# HW_RPI_DAQ.net
KiCad netlist of a schematic drawn in EAGLE
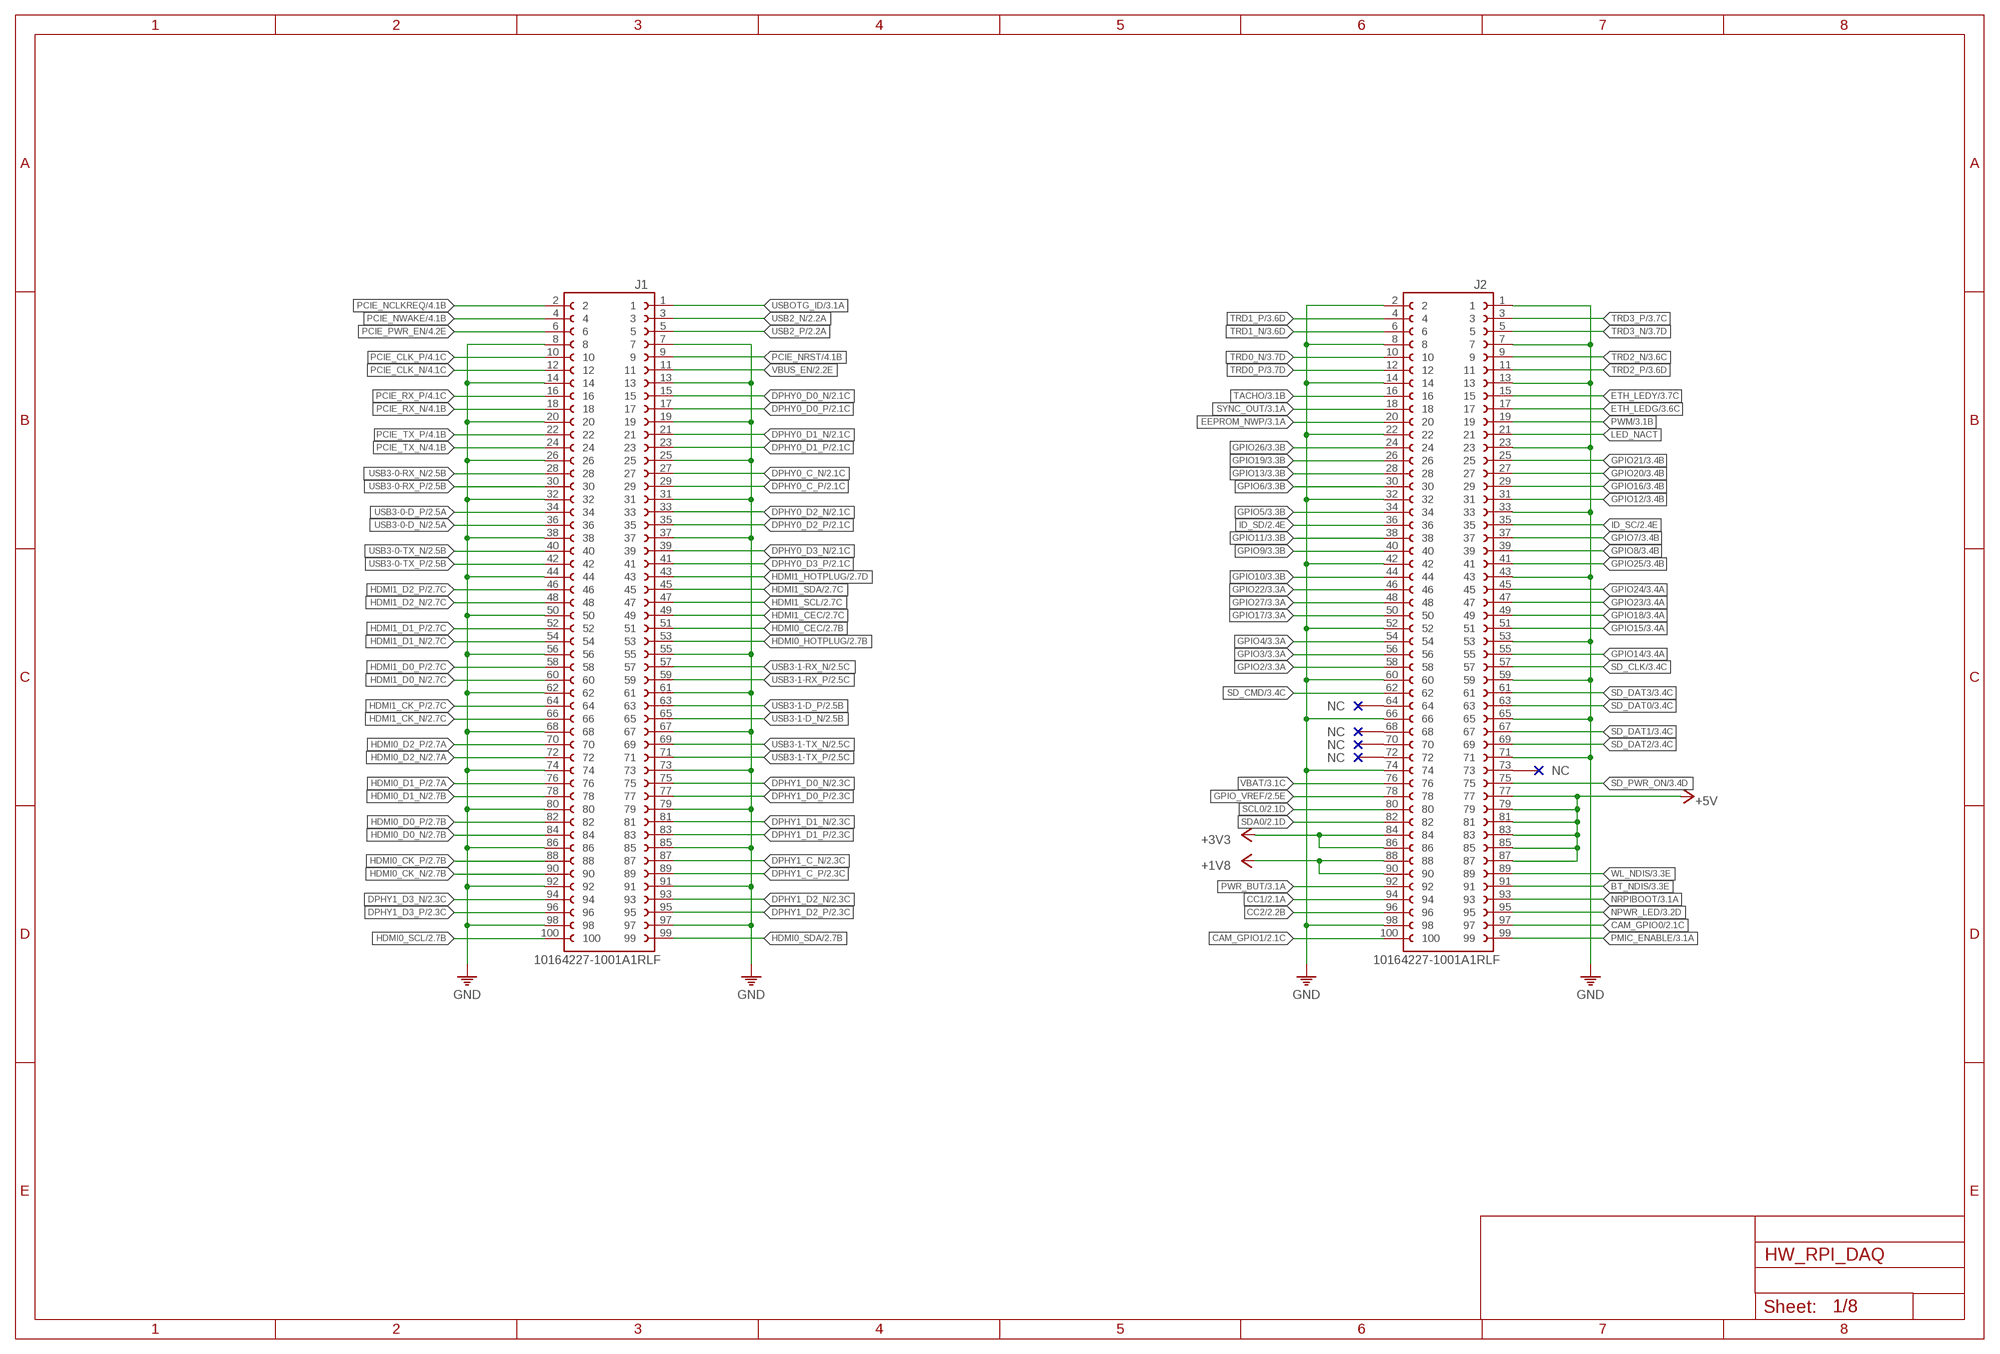
[diagram p0: schematic, sheet 1]
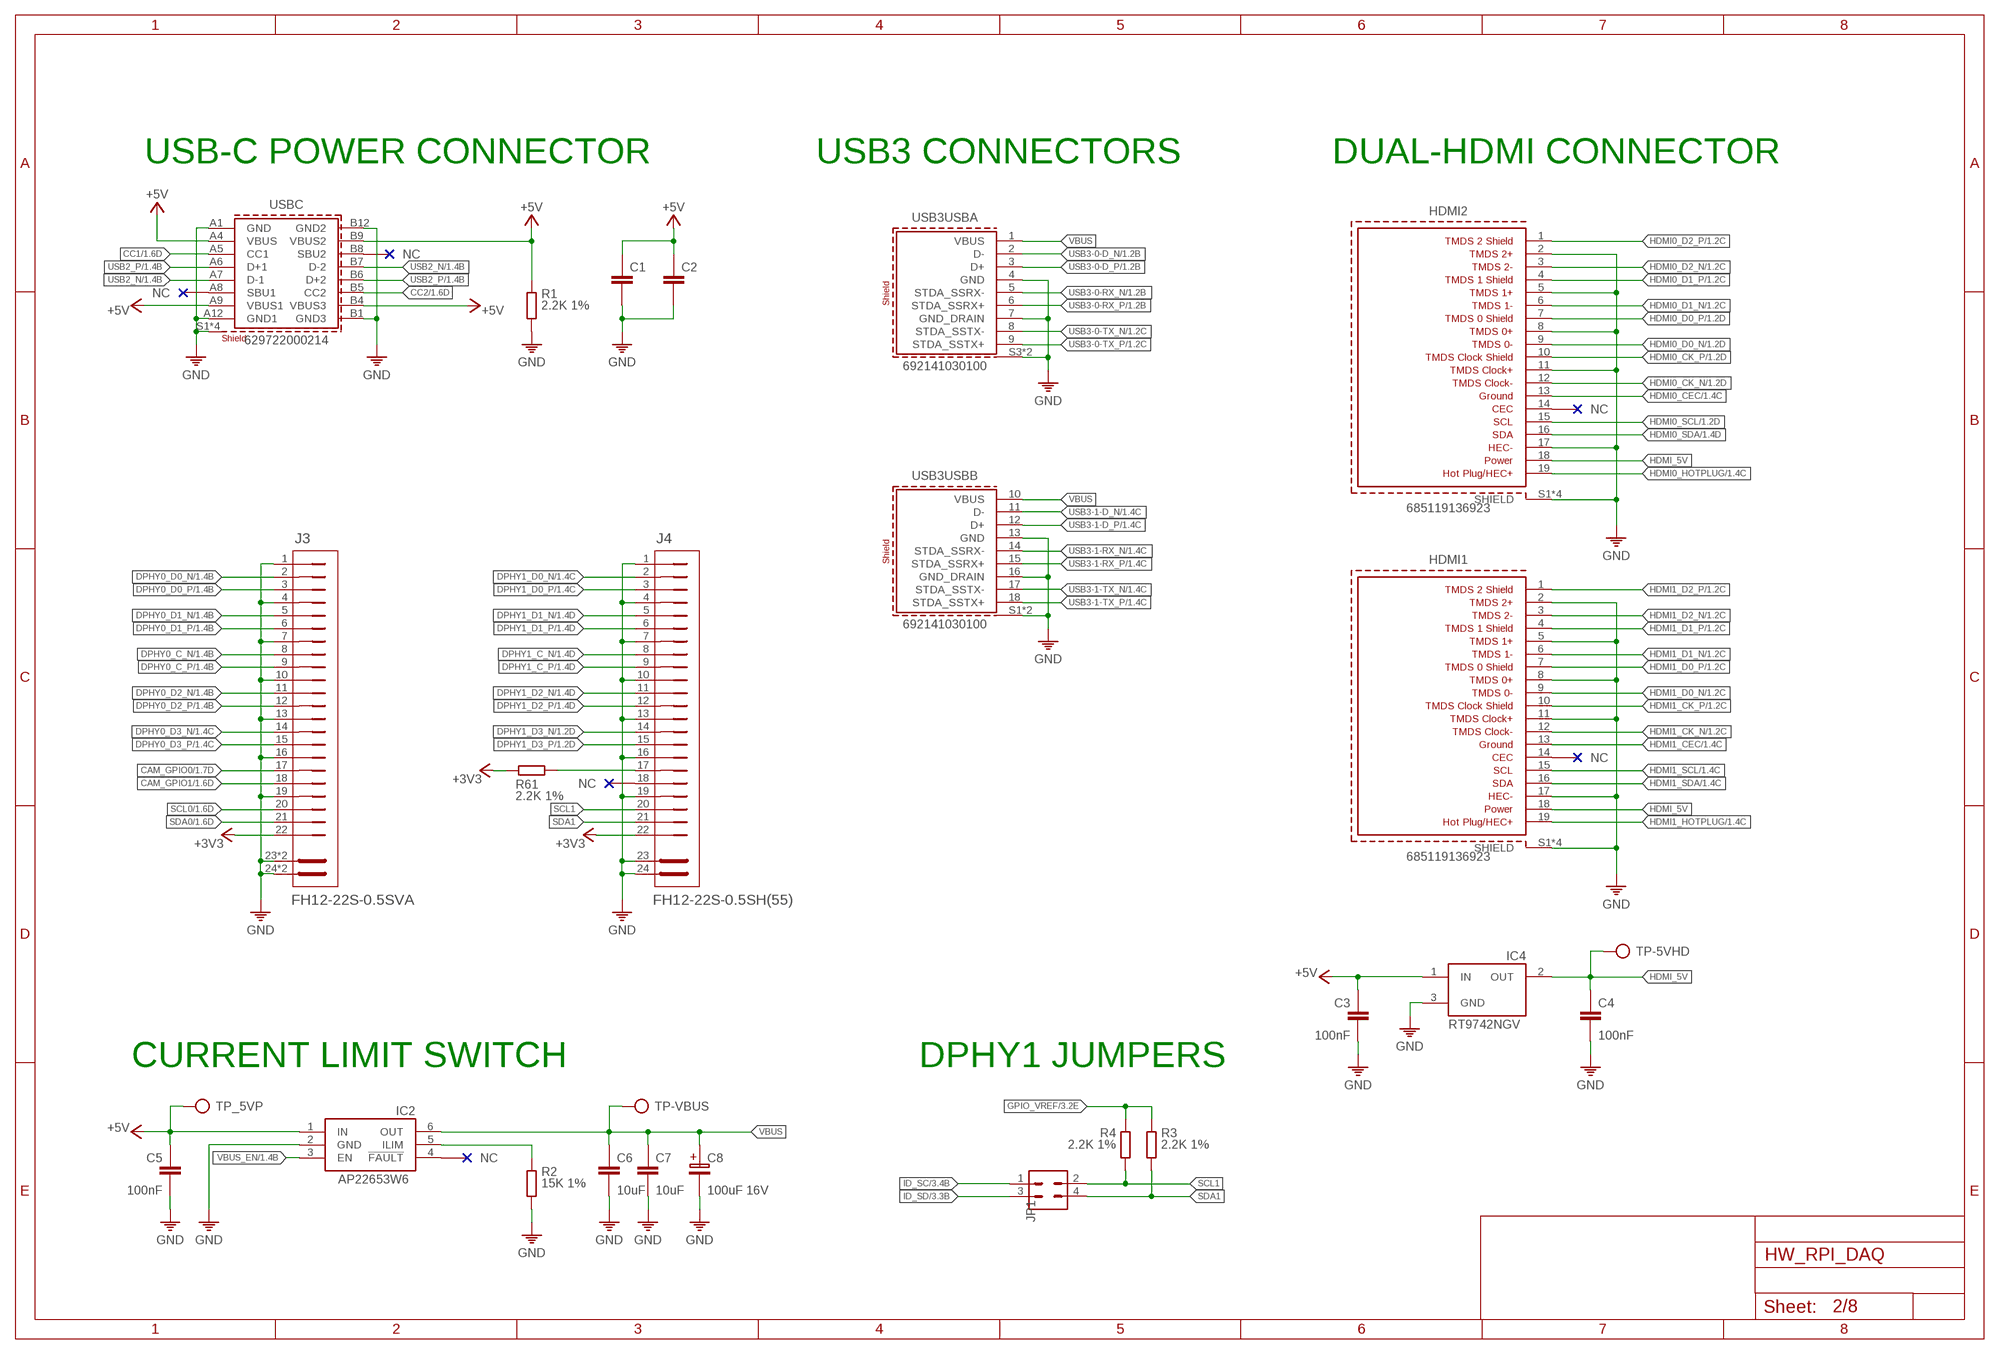
[diagram p1: schematic, sheet 2]
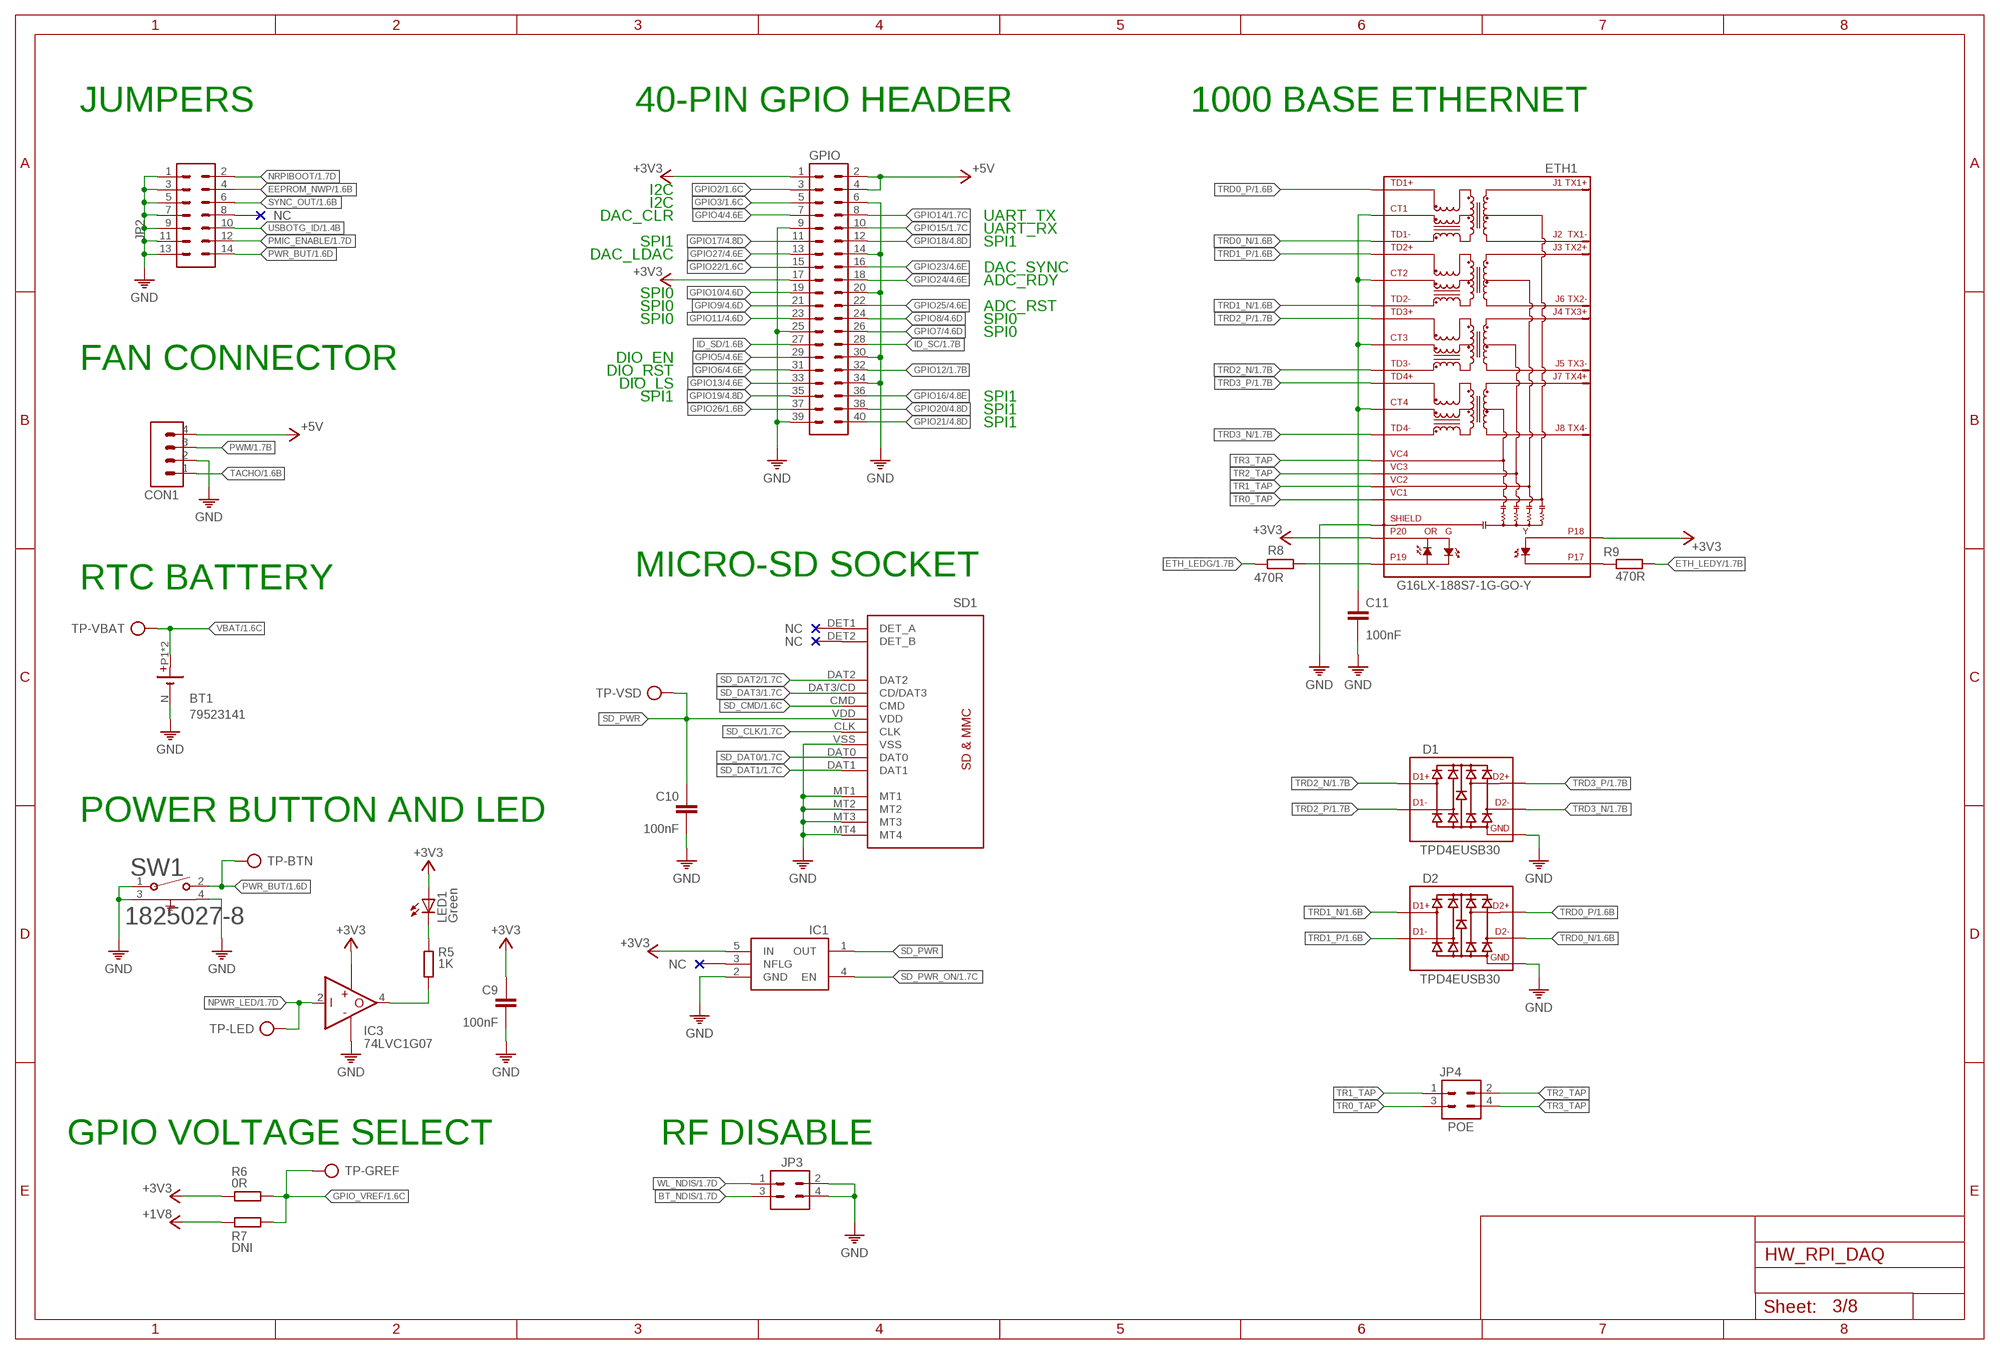
[diagram p2: schematic, sheet 3]
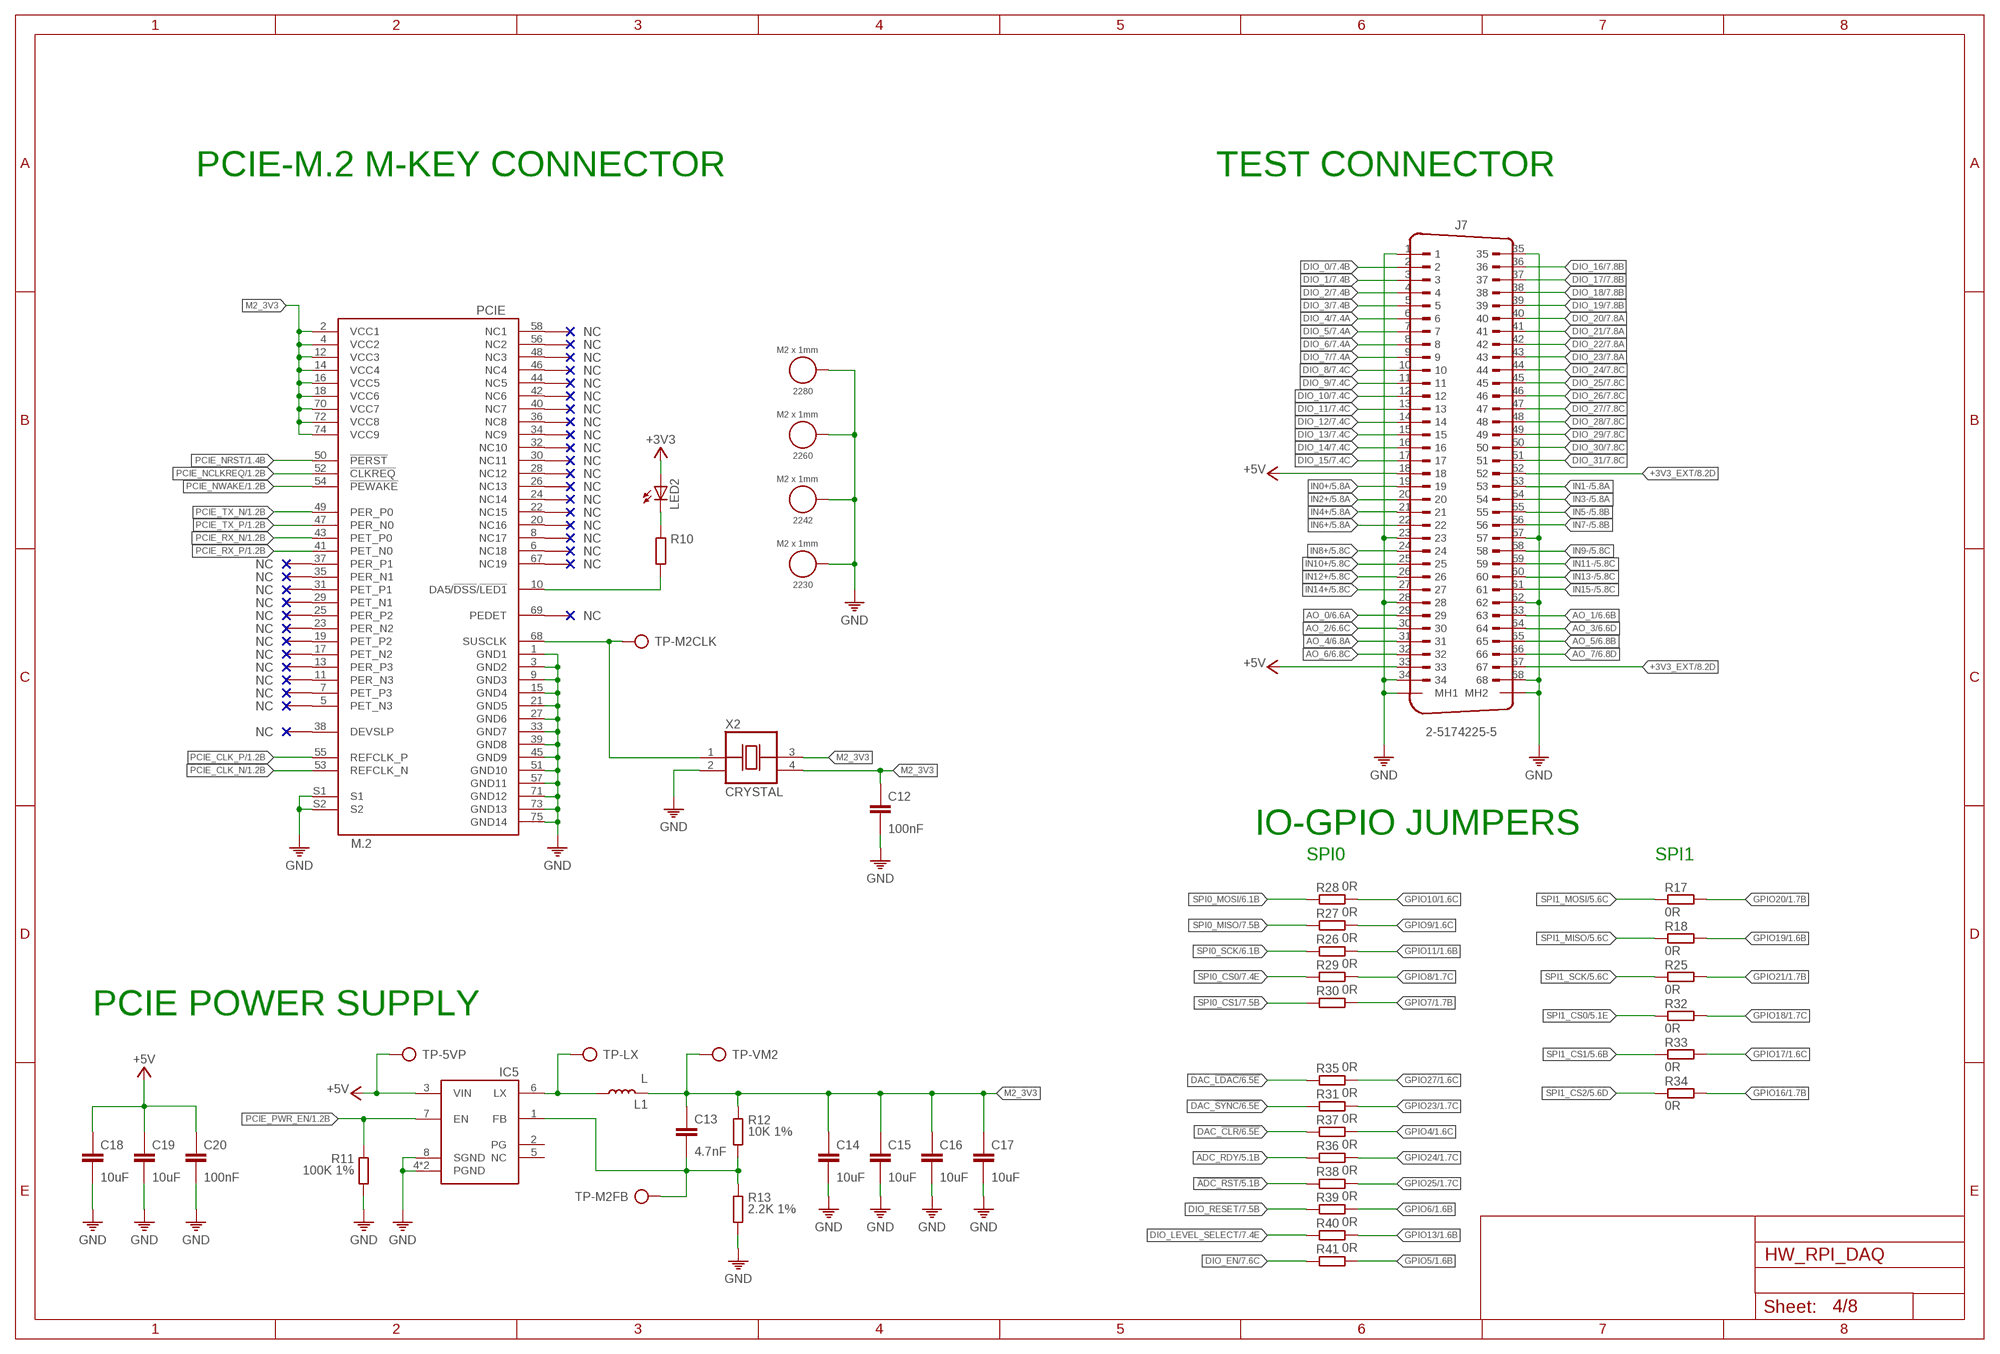
[diagram p3: schematic, sheet 4]
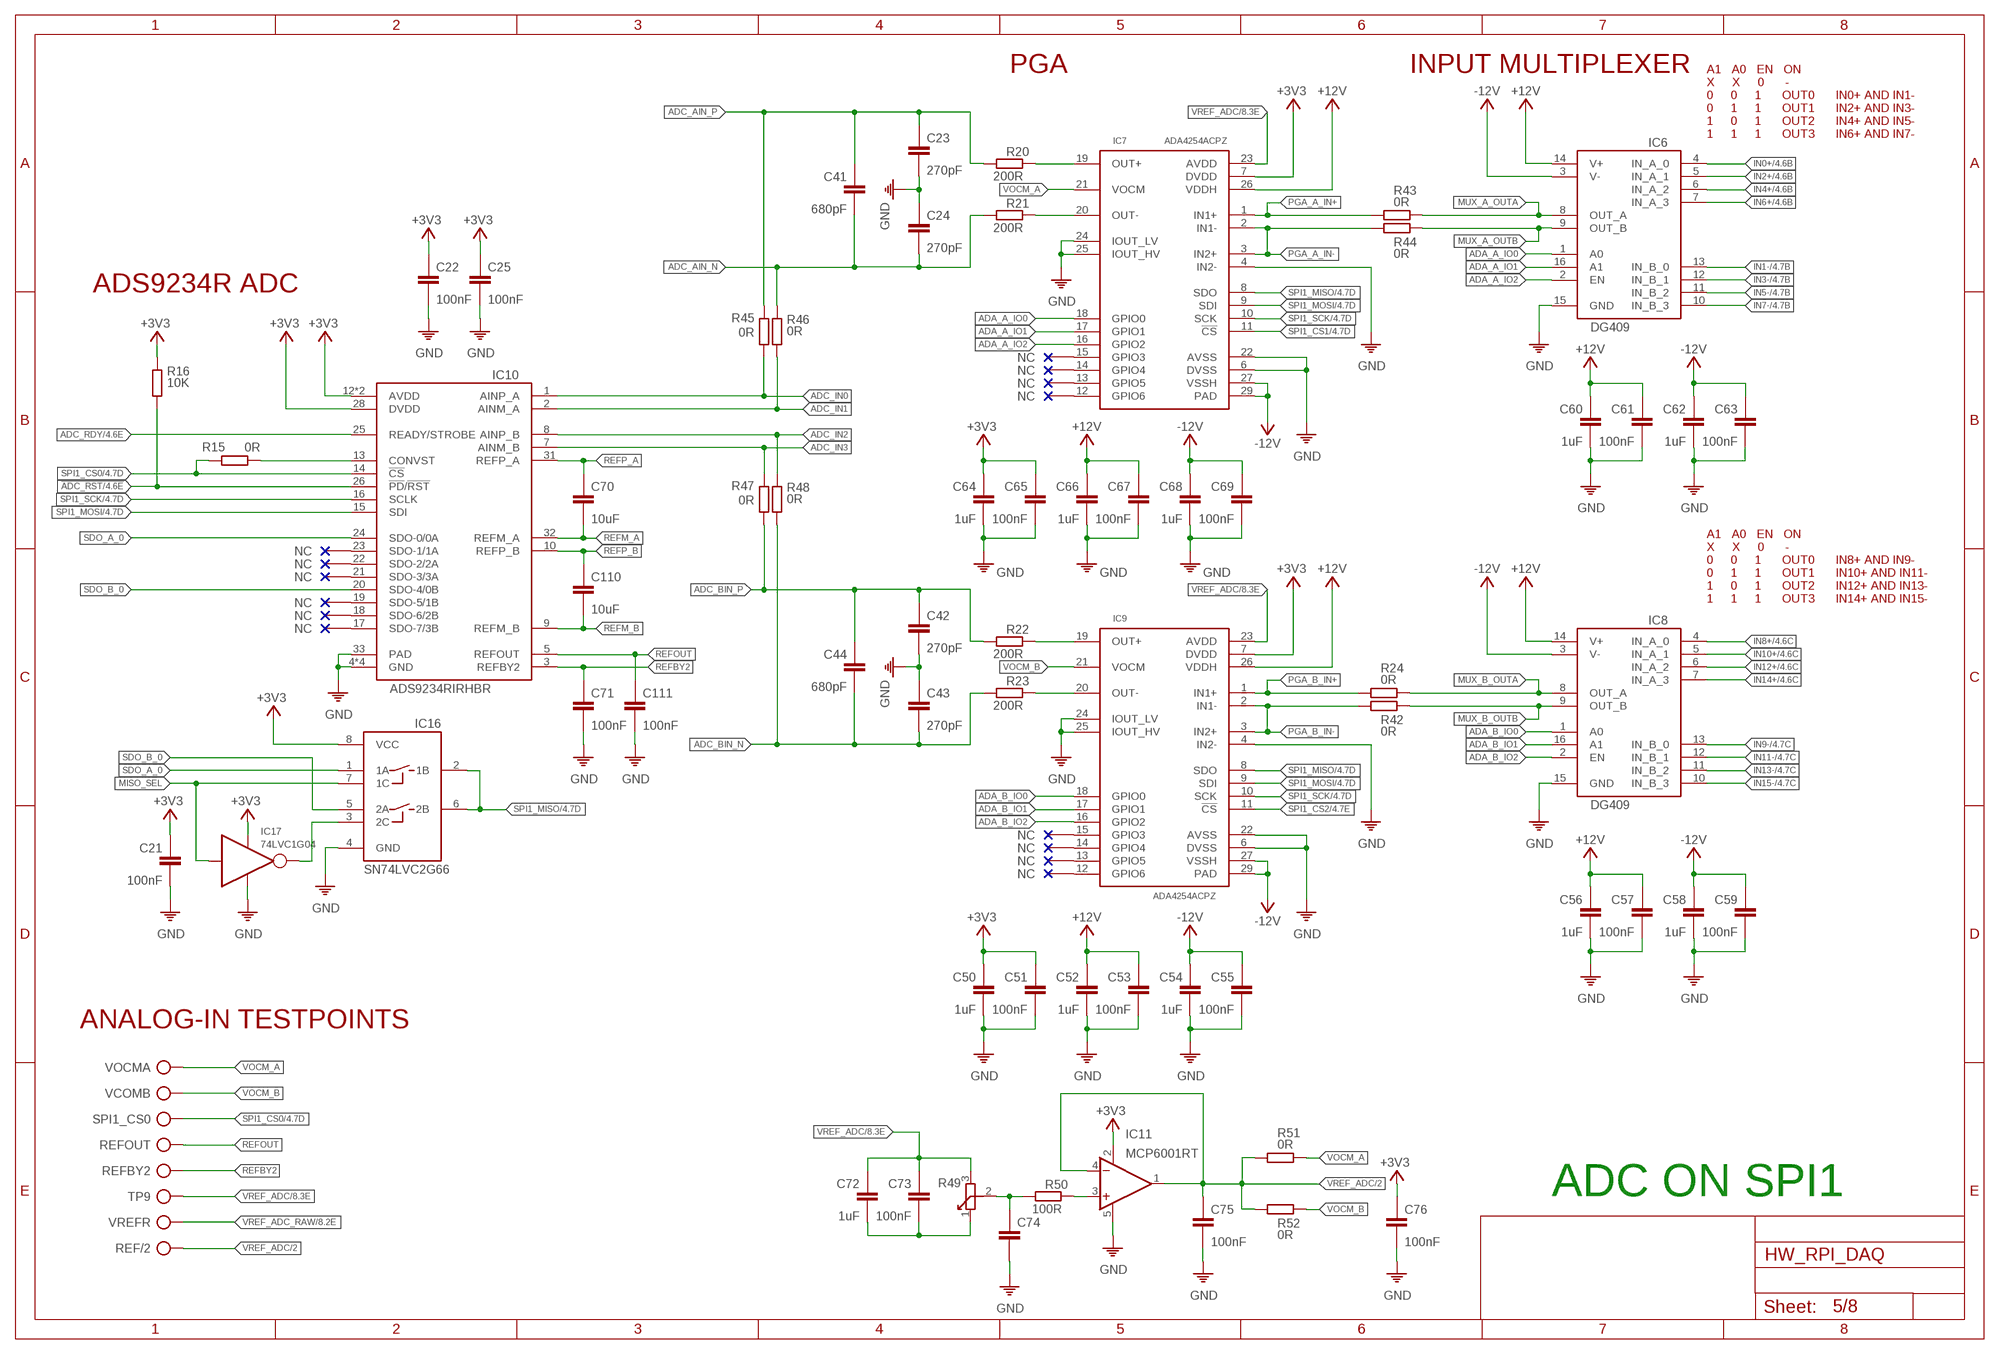
[diagram p4: schematic, sheet 5]
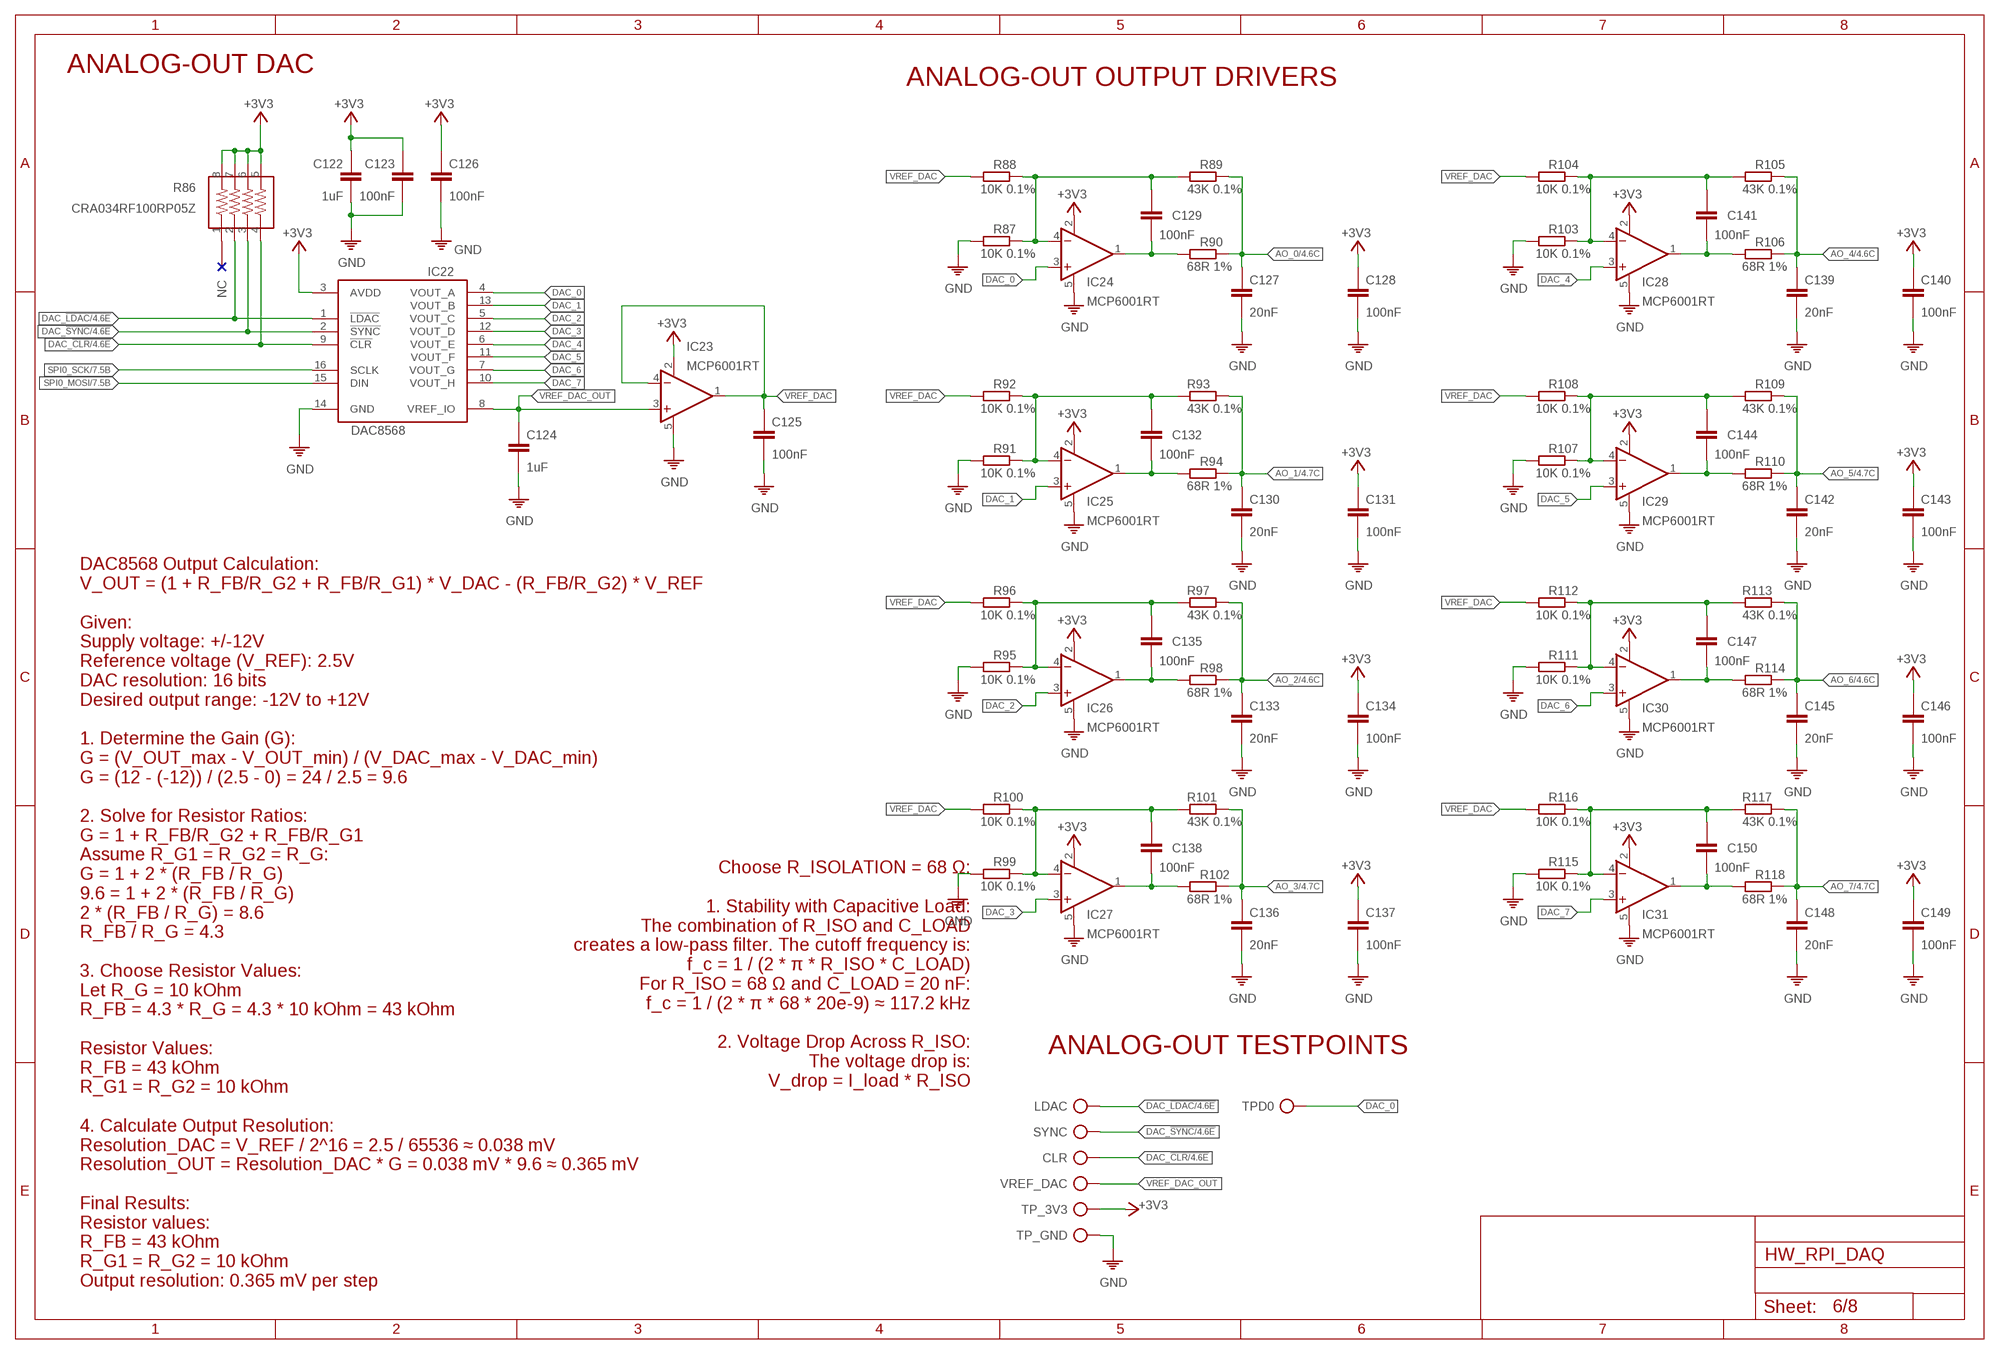
[diagram p5: schematic, sheet 6]
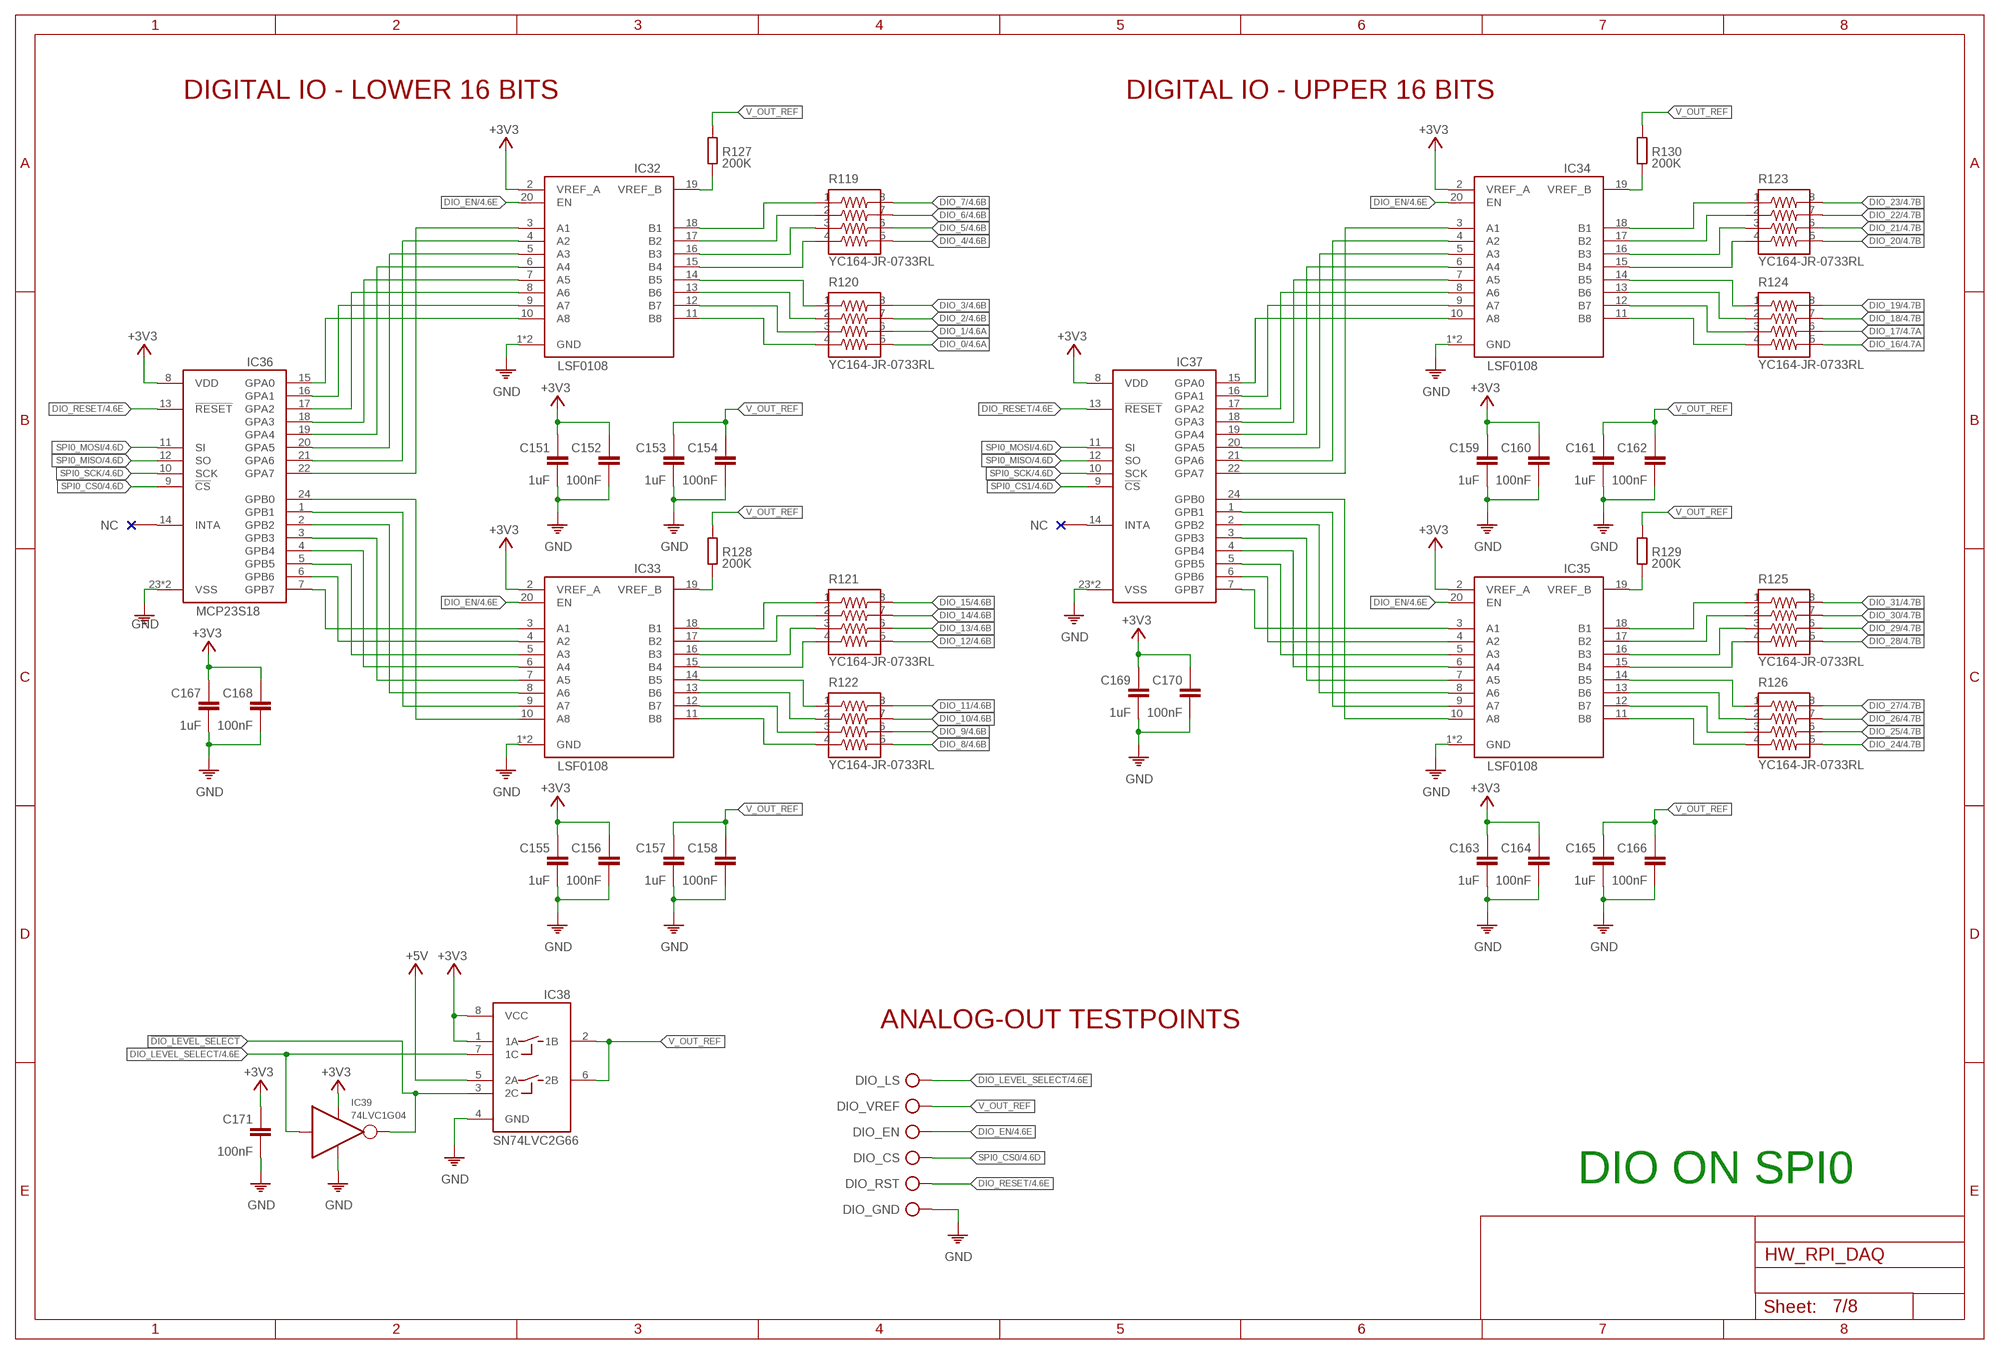
[diagram p6: schematic, sheet 7]
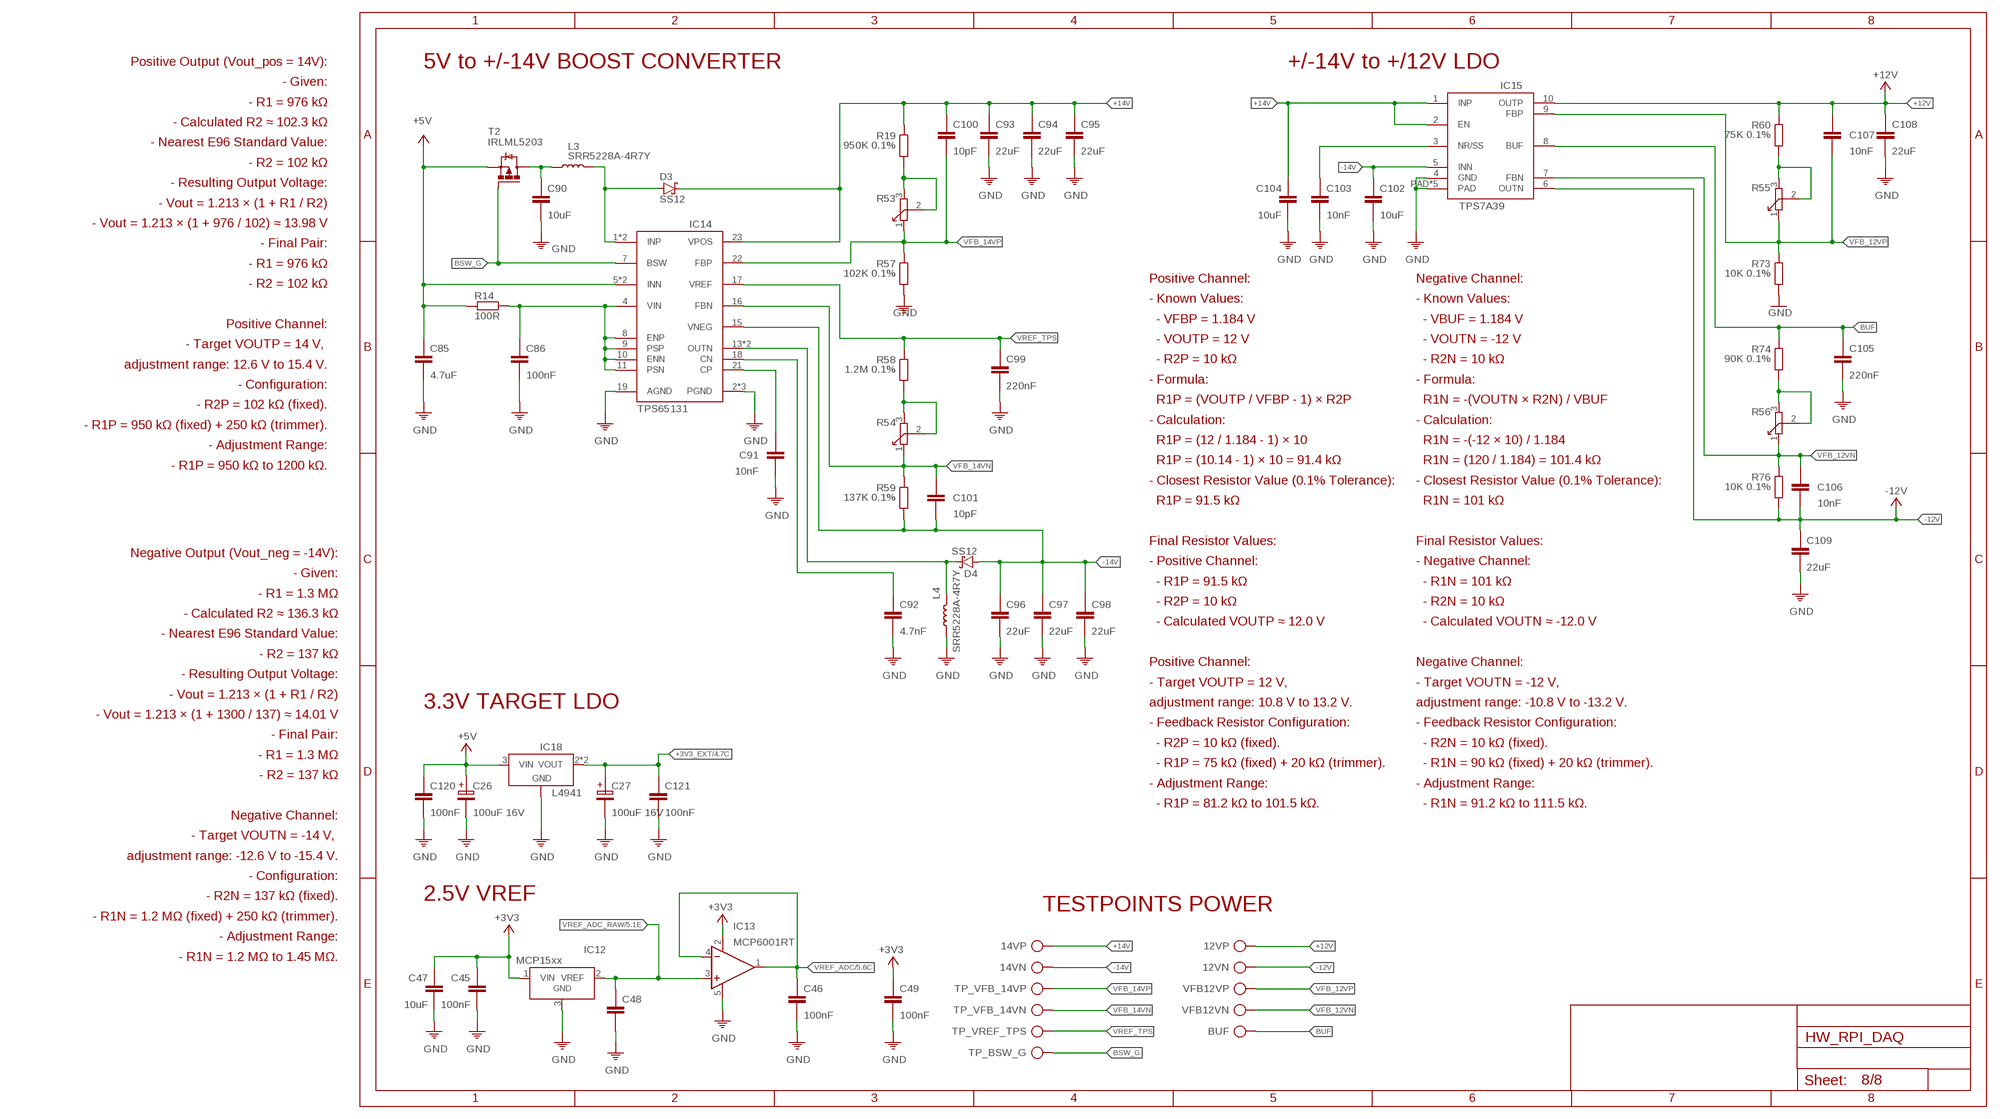
[diagram p7: schematic, sheet 8]

(export (version "E")
  (design (tool "Eeschema 10.0.6"))
  (components
    (comp (ref "C21")
      (value "100nF")
      (footprint "eagle-import:0603")
      (libsource (lib "eagle-import") (part "C0603"))
    )
    (comp (ref "C22")
      (value "100nF")
      (footprint "eagle-import:0402")
      (libsource (lib "eagle-import") (part "C0402"))
    )
    (comp (ref "C23")
      (value "270pF")
      (footprint "eagle-import:0402")
      (libsource (lib "eagle-import") (part "C0402"))
    )
    (comp (ref "C24")
      (value "270pF")
      (footprint "eagle-import:0402")
      (libsource (lib "eagle-import") (part "C0402"))
    )
    (comp (ref "C25")
      (value "100nF")
      (footprint "eagle-import:0402")
      (libsource (lib "eagle-import") (part "C0402"))
    )
    (comp (ref "C41")
      (value "680pF")
      (footprint "eagle-import:0402")
      (libsource (lib "eagle-import") (part "C0402"))
    )
    (comp (ref "C42")
      (value "270pF")
      (footprint "eagle-import:0402")
      (libsource (lib "eagle-import") (part "C0402"))
    )
    (comp (ref "C43")
      (value "270pF")
      (footprint "eagle-import:0402")
      (libsource (lib "eagle-import") (part "C0402"))
    )
    (comp (ref "C44")
      (value "680pF")
      (footprint "eagle-import:0402")
      (libsource (lib "eagle-import") (part "C0402"))
    )
    (comp (ref "C50")
      (value "1uF")
      (footprint "eagle-import:0603")
      (libsource (lib "eagle-import") (part "C0603"))
    )
    (comp (ref "C51")
      (value "100nF")
      (footprint "eagle-import:0402")
      (libsource (lib "eagle-import") (part "C0402"))
    )
    (comp (ref "C52")
      (value "1uF")
      (footprint "eagle-import:0603")
      (libsource (lib "eagle-import") (part "C0603"))
    )
    (comp (ref "C53")
      (value "100nF")
      (footprint "eagle-import:0402")
      (libsource (lib "eagle-import") (part "C0402"))
    )
    (comp (ref "C54")
      (value "1uF")
      (footprint "eagle-import:0603")
      (libsource (lib "eagle-import") (part "C0603"))
    )
    (comp (ref "C55")
      (value "100nF")
      (footprint "eagle-import:0402")
      (libsource (lib "eagle-import") (part "C0402"))
    )
    (comp (ref "C56")
      (value "1uF")
      (footprint "eagle-import:0603")
      (libsource (lib "eagle-import") (part "C0603"))
    )
    (comp (ref "C57")
      (value "100nF")
      (footprint "eagle-import:0402")
      (libsource (lib "eagle-import") (part "C0402"))
    )
    (comp (ref "C58")
      (value "1uF")
      (footprint "eagle-import:0603")
      (libsource (lib "eagle-import") (part "C0603"))
    )
    (comp (ref "C59")
      (value "100nF")
      (footprint "eagle-import:0402")
      (libsource (lib "eagle-import") (part "C0402"))
    )
    (comp (ref "C60")
      (value "1uF")
      (footprint "eagle-import:0603")
      (libsource (lib "eagle-import") (part "C0603"))
    )
    (comp (ref "C61")
      (value "100nF")
      (footprint "eagle-import:0402")
      (libsource (lib "eagle-import") (part "C0402"))
    )
    (comp (ref "C62")
      (value "1uF")
      (footprint "eagle-import:0603")
      (libsource (lib "eagle-import") (part "C0603"))
    )
    (comp (ref "C63")
      (value "100nF")
      (footprint "eagle-import:0402")
      (libsource (lib "eagle-import") (part "C0402"))
    )
    (comp (ref "C64")
      (value "1uF")
      (footprint "eagle-import:0603")
      (libsource (lib "eagle-import") (part "C0603"))
    )
    (comp (ref "C65")
      (value "100nF")
      (footprint "eagle-import:0402")
      (libsource (lib "eagle-import") (part "C0402"))
    )
    (comp (ref "C66")
      (value "1uF")
      (footprint "eagle-import:0603")
      (libsource (lib "eagle-import") (part "C0603"))
    )
    (comp (ref "C67")
      (value "100nF")
      (footprint "eagle-import:0402")
      (libsource (lib "eagle-import") (part "C0402"))
    )
    (comp (ref "C68")
      (value "1uF")
      (footprint "eagle-import:0603")
      (libsource (lib "eagle-import") (part "C0603"))
    )
    (comp (ref "C69")
      (value "100nF")
      (footprint "eagle-import:0402")
      (libsource (lib "eagle-import") (part "C0402"))
    )
    (comp (ref "C70")
      (value "10uF")
      (footprint "eagle-import:0603")
      (libsource (lib "eagle-import") (part "C0603"))
    )
    (comp (ref "C71")
      (value "100nF")
      (footprint "eagle-import:0402")
      (libsource (lib "eagle-import") (part "C0402"))
    )
    (comp (ref "C72")
      (value "1uF")
      (footprint "eagle-import:0603")
      (libsource (lib "eagle-import") (part "C0603"))
    )
    (comp (ref "C73")
      (value "100nF")
      (footprint "eagle-import:0603")
      (libsource (lib "eagle-import") (part "C0603"))
    )
    (comp (ref "C74")
      (value "C0805")
      (footprint "eagle-import:0805")
      (libsource (lib "eagle-import") (part "C0805"))
    )
    (comp (ref "C75")
      (value "100nF")
      (footprint "eagle-import:0402")
      (libsource (lib "eagle-import") (part "C0402"))
    )
    (comp (ref "C76")
      (value "100nF")
      (footprint "eagle-import:0402")
      (libsource (lib "eagle-import") (part "C0402"))
    )
    (comp (ref "C110")
      (value "10uF")
      (footprint "eagle-import:0603")
      (libsource (lib "eagle-import") (part "C0603"))
    )
    (comp (ref "C111")
      (value "100nF")
      (footprint "eagle-import:0402")
      (libsource (lib "eagle-import") (part "C0402"))
    )
    (comp (ref "IC6")
      (value "DG409")
      (footprint "eagle-import:TSSOP2")
      (libsource (lib "eagle-import") (part "DG409EUE+"))
    )
    (comp (ref "IC7")
      (value "ADA4254ACPZ")
      (footprint "eagle-import:QFN50P500X500X75-29T314N")
      (libsource (lib "eagle-import") (part "ADA4254ACPZ"))
    )
    (comp (ref "IC8")
      (value "DG409")
      (footprint "eagle-import:TSSOP2")
      (libsource (lib "eagle-import") (part "DG409EUE+"))
    )
    (comp (ref "IC9")
      (value "ADA4254ACPZ")
      (footprint "eagle-import:QFN50P500X500X75-29T314N")
      (libsource (lib "eagle-import") (part "ADA4254ACPZ"))
    )
    (comp (ref "IC10")
      (value "ADS9234RIRHBR")
      (footprint "eagle-import:VQFN32-5X5")
      (libsource (lib "eagle-import") (part "ADS9234RIRHBR"))
    )
    (comp (ref "IC11")
      (value "MCP6001RT")
      (footprint "eagle-import:SOT23-5")
      (libsource (lib "eagle-import") (part "MCP6001RT"))
    )
    (comp (ref "IC16")
      (value "SN74LVC2G66")
      (footprint "eagle-import:SOP50P310X90-8N")
      (libsource (lib "eagle-import") (part "SN74LVC2G66"))
    )
    (comp (ref "IC17")
      (value "74LVC1G04")
      (footprint "eagle-import:SOT95P280X145-5N")
      (libsource (lib "eagle-import") (part "74LVC1G04"))
    )
    (comp (ref "R15")
      (value "0R")
      (footprint "eagle-import:0402")
      (libsource (lib "eagle-import") (part "R0402"))
    )
    (comp (ref "R16")
      (value "10K")
      (footprint "eagle-import:0402")
      (libsource (lib "eagle-import") (part "R0402"))
    )
    (comp (ref "R20")
      (value "200R")
      (footprint "eagle-import:0402")
      (libsource (lib "eagle-import") (part "R0402"))
    )
    (comp (ref "R21")
      (value "200R")
      (footprint "eagle-import:0402")
      (libsource (lib "eagle-import") (part "R0402"))
    )
    (comp (ref "R22")
      (value "200R")
      (footprint "eagle-import:0402")
      (libsource (lib "eagle-import") (part "R0402"))
    )
    (comp (ref "R23")
      (value "200R")
      (footprint "eagle-import:0402")
      (libsource (lib "eagle-import") (part "R0402"))
    )
    (comp (ref "R24")
      (value "0R")
      (footprint "eagle-import:0402")
      (libsource (lib "eagle-import") (part "R0402"))
    )
    (comp (ref "R42")
      (value "0R")
      (footprint "eagle-import:0402")
      (libsource (lib "eagle-import") (part "R0402"))
    )
    (comp (ref "R43")
      (value "0R")
      (footprint "eagle-import:0402")
      (libsource (lib "eagle-import") (part "R0402"))
    )
    (comp (ref "R44")
      (value "0R")
      (footprint "eagle-import:0402")
      (libsource (lib "eagle-import") (part "R0402"))
    )
    (comp (ref "R45")
      (value "0R")
      (footprint "eagle-import:0402")
      (libsource (lib "eagle-import") (part "R0402"))
    )
    (comp (ref "R46")
      (value "0R")
      (footprint "eagle-import:0402")
      (libsource (lib "eagle-import") (part "R0402"))
    )
    (comp (ref "R47")
      (value "0R")
      (footprint "eagle-import:0402")
      (libsource (lib "eagle-import") (part "R0402"))
    )
    (comp (ref "R48")
      (value "0R")
      (footprint "eagle-import:0402")
      (libsource (lib "eagle-import") (part "R0402"))
    )
    (comp (ref "R49")
      (value "R-TRIM")
      (footprint "eagle-import:TC33X")
      (libsource (lib "eagle-import") (part "R-TRIM"))
    )
    (comp (ref "R50")
      (value "100R")
      (footprint "eagle-import:0402")
      (libsource (lib "eagle-import") (part "R0402"))
    )
    (comp (ref "R51")
      (value "0R")
      (footprint "eagle-import:0603")
      (libsource (lib "eagle-import") (part "R0603"))
    )
    (comp (ref "R52")
      (value "0R")
      (footprint "eagle-import:0603")
      (libsource (lib "eagle-import") (part "R0603"))
    )
    (comp (ref "REF/2")
      (value "TP")
      (footprint "eagle-import:TP")
      (libsource (lib "eagle-import") (part "TP"))
    )
    (comp (ref "REFBY2")
      (value "TP")
      (footprint "eagle-import:TP")
      (libsource (lib "eagle-import") (part "TP"))
    )
    (comp (ref "REFOUT")
      (value "TP")
      (footprint "eagle-import:TP")
      (libsource (lib "eagle-import") (part "TP"))
    )
    (comp (ref "SPI1_CS0")
      (value "TP")
      (footprint "eagle-import:TP")
      (libsource (lib "eagle-import") (part "TP"))
    )
    (comp (ref "TP9") (value "TP") (footprint "eagle-import:TP") (libsource (lib "eagle-import") (part "TP")))
    (comp (ref "VCOMB")
      (value "TP")
      (footprint "eagle-import:TP")
      (libsource (lib "eagle-import") (part "TP"))
    )
    (comp (ref "VOCMA")
      (value "TP")
      (footprint "eagle-import:TP")
      (libsource (lib "eagle-import") (part "TP"))
    )
    (comp (ref "VREFR")
      (value "TP")
      (footprint "eagle-import:TP")
      (libsource (lib "eagle-import") (part "TP"))
    )
    (comp (ref "2230")
      (value "M2 x 1mm")
      (footprint "eagle-import:WA-SMSI_9774010243")
      (libsource (lib "eagle-import") (part "WA-SMSI_9774XXX243_9774010243"))
    )
    (comp (ref "2242")
      (value "M2 x 1mm")
      (footprint "eagle-import:WA-SMSI_9774010243")
      (libsource (lib "eagle-import") (part "WA-SMSI_9774XXX243_9774010243"))
    )
    (comp (ref "2260")
      (value "M2 x 1mm")
      (footprint "eagle-import:WA-SMSI_9774010243")
      (libsource (lib "eagle-import") (part "WA-SMSI_9774XXX243_9774010243"))
    )
    (comp (ref "2280")
      (value "M2 x 1mm")
      (footprint "eagle-import:WA-SMSI_9774010243")
      (libsource (lib "eagle-import") (part "WA-SMSI_9774XXX243_9774010243"))
    )
    (comp (ref "C12")
      (value "100nF")
      (footprint "eagle-import:0402")
      (libsource (lib "eagle-import") (part "C0402"))
    )
    (comp (ref "C13")
      (value "4.7nF")
      (footprint "eagle-import:0402")
      (libsource (lib "eagle-import") (part "C0402"))
    )
    (comp (ref "C14")
      (value "10uF")
      (footprint "eagle-import:0805")
      (libsource (lib "eagle-import") (part "C0805"))
    )
    (comp (ref "C15")
      (value "10uF")
      (footprint "eagle-import:0805")
      (libsource (lib "eagle-import") (part "C0805"))
    )
    (comp (ref "C16")
      (value "10uF")
      (footprint "eagle-import:0805")
      (libsource (lib "eagle-import") (part "C0805"))
    )
    (comp (ref "C17")
      (value "10uF")
      (footprint "eagle-import:0805")
      (libsource (lib "eagle-import") (part "C0805"))
    )
    (comp (ref "C18")
      (value "10uF")
      (footprint "eagle-import:0805")
      (libsource (lib "eagle-import") (part "C0805"))
    )
    (comp (ref "C19")
      (value "10uF")
      (footprint "eagle-import:0805")
      (libsource (lib "eagle-import") (part "C0805"))
    )
    (comp (ref "C20")
      (value "100nF")
      (footprint "eagle-import:0402")
      (libsource (lib "eagle-import") (part "C0402"))
    )
    (comp (ref "IC5")
      (value "AP3441SHE-7B")
      (footprint "eagle-import:SON50P201X201X56-9T90X170N")
      (libsource (lib "eagle-import") (part "AP3441SHE-7B"))
    )
    (comp (ref "J7")
      (value "2-5174225-5")
      (footprint "eagle-import:2-5174225-5")
      (fields (field (name "MANUFACTURER") "TE Connectivity AMP Connectors"))
      (libsource (lib "eagle-import") (part "2-5174225-5"))
    )
    (comp (ref "L1")
      (value "L")
      (footprint "eagle-import:SRR5228A")
      (libsource (lib "eagle-import") (part "L"))
    )
    (comp (ref "LED2")
      (value "LEDCHIPLED_0805")
      (footprint "eagle-import:CHIPLED_0805")
      (libsource (lib "eagle-import") (part "LEDCHIPLED_0805"))
    )
    (comp (ref "PCIE")
      (value "M.2")
      (footprint "eagle-import:M.2")
      (libsource (lib "eagle-import") (part "M.2"))
    )
    (comp (ref "R10")
      (value "R0402")
      (footprint "eagle-import:0402")
      (libsource (lib "eagle-import") (part "R0402"))
    )
    (comp (ref "R11")
      (value "100K 1%")
      (footprint "eagle-import:0402")
      (libsource (lib "eagle-import") (part "R0402"))
    )
    (comp (ref "R12")
      (value "10K 1%")
      (footprint "eagle-import:0402")
      (libsource (lib "eagle-import") (part "R0402"))
    )
    (comp (ref "R13")
      (value "2.2K 1%")
      (footprint "eagle-import:0402")
      (libsource (lib "eagle-import") (part "R0402"))
    )
    (comp (ref "R17")
      (value "0R")
      (footprint "eagle-import:0603")
      (libsource (lib "eagle-import") (part "R0603"))
    )
    (comp (ref "R18")
      (value "0R")
      (footprint "eagle-import:0603")
      (libsource (lib "eagle-import") (part "R0603"))
    )
    (comp (ref "R25")
      (value "0R")
      (footprint "eagle-import:0603")
      (libsource (lib "eagle-import") (part "R0603"))
    )
    (comp (ref "R26")
      (value "0R")
      (footprint "eagle-import:0603")
      (libsource (lib "eagle-import") (part "R0603"))
    )
    (comp (ref "R27")
      (value "0R")
      (footprint "eagle-import:0603")
      (libsource (lib "eagle-import") (part "R0603"))
    )
    (comp (ref "R28")
      (value "0R")
      (footprint "eagle-import:0603")
      (libsource (lib "eagle-import") (part "R0603"))
    )
    (comp (ref "R29")
      (value "0R")
      (footprint "eagle-import:0603")
      (libsource (lib "eagle-import") (part "R0603"))
    )
    (comp (ref "R30")
      (value "0R")
      (footprint "eagle-import:0603")
      (libsource (lib "eagle-import") (part "R0603"))
    )
    (comp (ref "R31")
      (value "0R")
      (footprint "eagle-import:0603")
      (libsource (lib "eagle-import") (part "R0603"))
    )
    (comp (ref "R32")
      (value "0R")
      (footprint "eagle-import:0603")
      (libsource (lib "eagle-import") (part "R0603"))
    )
    (comp (ref "R33")
      (value "0R")
      (footprint "eagle-import:0603")
      (libsource (lib "eagle-import") (part "R0603"))
    )
    (comp (ref "R34")
      (value "0R")
      (footprint "eagle-import:0603")
      (libsource (lib "eagle-import") (part "R0603"))
    )
    (comp (ref "R35")
      (value "0R")
      (footprint "eagle-import:0603")
      (libsource (lib "eagle-import") (part "R0603"))
    )
    (comp (ref "R36")
      (value "0R")
      (footprint "eagle-import:0603")
      (libsource (lib "eagle-import") (part "R0603"))
    )
    (comp (ref "R37")
      (value "0R")
      (footprint "eagle-import:0603")
      (libsource (lib "eagle-import") (part "R0603"))
    )
    (comp (ref "R38")
      (value "0R")
      (footprint "eagle-import:0603")
      (libsource (lib "eagle-import") (part "R0603"))
    )
    (comp (ref "R39")
      (value "0R")
      (footprint "eagle-import:0603")
      (libsource (lib "eagle-import") (part "R0603"))
    )
    (comp (ref "R40")
      (value "0R")
      (footprint "eagle-import:0603")
      (libsource (lib "eagle-import") (part "R0603"))
    )
    (comp (ref "R41")
      (value "0R")
      (footprint "eagle-import:0603")
      (libsource (lib "eagle-import") (part "R0603"))
    )
    (comp (ref "TP-5VP")
      (value "TP")
      (footprint "eagle-import:TP")
      (libsource (lib "eagle-import") (part "TP"))
    )
    (comp (ref "TP-LX")
      (value "TP")
      (footprint "eagle-import:TP")
      (libsource (lib "eagle-import") (part "TP"))
    )
    (comp (ref "TP-M2CLK")
      (value "TP")
      (footprint "eagle-import:TP")
      (libsource (lib "eagle-import") (part "TP"))
    )
    (comp (ref "TP-M2FB")
      (value "TP")
      (footprint "eagle-import:TP")
      (libsource (lib "eagle-import") (part "TP"))
    )
    (comp (ref "TP-VM2")
      (value "TP")
      (footprint "eagle-import:TP")
      (libsource (lib "eagle-import") (part "TP"))
    )
    (comp (ref "X2")
      (value "CRYSTAL")
      (footprint "eagle-import:OSCCC500X320X130")
      (libsource (lib "eagle-import") (part "CRYSTAL"))
    )
    (comp (ref "C122")
      (value "1uF")
      (footprint "eagle-import:0603")
      (libsource (lib "eagle-import") (part "C0603"))
    )
    (comp (ref "C123")
      (value "100nF")
      (footprint "eagle-import:0603")
      (libsource (lib "eagle-import") (part "C0603"))
    )
    (comp (ref "C124")
      (value "1uF")
      (footprint "eagle-import:0603")
      (libsource (lib "eagle-import") (part "C0603"))
    )
    (comp (ref "C125")
      (value "100nF")
      (footprint "eagle-import:0402")
      (libsource (lib "eagle-import") (part "C0402"))
    )
    (comp (ref "C126")
      (value "100nF")
      (footprint "eagle-import:0402")
      (libsource (lib "eagle-import") (part "C0402"))
    )
    (comp (ref "C127")
      (value "20nF")
      (footprint "eagle-import:0402")
      (libsource (lib "eagle-import") (part "C0402"))
    )
    (comp (ref "C128")
      (value "100nF")
      (footprint "eagle-import:0402")
      (libsource (lib "eagle-import") (part "C0402"))
    )
    (comp (ref "C129")
      (value "100nF")
      (footprint "eagle-import:0402")
      (libsource (lib "eagle-import") (part "C0402"))
    )
    (comp (ref "C130")
      (value "20nF")
      (footprint "eagle-import:0402")
      (libsource (lib "eagle-import") (part "C0402"))
    )
    (comp (ref "C131")
      (value "100nF")
      (footprint "eagle-import:0402")
      (libsource (lib "eagle-import") (part "C0402"))
    )
    (comp (ref "C132")
      (value "100nF")
      (footprint "eagle-import:0402")
      (libsource (lib "eagle-import") (part "C0402"))
    )
    (comp (ref "C133")
      (value "20nF")
      (footprint "eagle-import:0402")
      (libsource (lib "eagle-import") (part "C0402"))
    )
    (comp (ref "C134")
      (value "100nF")
      (footprint "eagle-import:0402")
      (libsource (lib "eagle-import") (part "C0402"))
    )
    (comp (ref "C135")
      (value "100nF")
      (footprint "eagle-import:0402")
      (libsource (lib "eagle-import") (part "C0402"))
    )
    (comp (ref "C136")
      (value "20nF")
      (footprint "eagle-import:0402")
      (libsource (lib "eagle-import") (part "C0402"))
    )
    (comp (ref "C137")
      (value "100nF")
      (footprint "eagle-import:0402")
      (libsource (lib "eagle-import") (part "C0402"))
    )
    (comp (ref "C138")
      (value "100nF")
      (footprint "eagle-import:0402")
      (libsource (lib "eagle-import") (part "C0402"))
    )
    (comp (ref "C139")
      (value "20nF")
      (footprint "eagle-import:0402")
      (libsource (lib "eagle-import") (part "C0402"))
    )
    (comp (ref "C140")
      (value "100nF")
      (footprint "eagle-import:0402")
      (libsource (lib "eagle-import") (part "C0402"))
    )
    (comp (ref "C141")
      (value "100nF")
      (footprint "eagle-import:0402")
      (libsource (lib "eagle-import") (part "C0402"))
    )
    (comp (ref "C142")
      (value "20nF")
      (footprint "eagle-import:0402")
      (libsource (lib "eagle-import") (part "C0402"))
    )
    (comp (ref "C143")
      (value "100nF")
      (footprint "eagle-import:0402")
      (libsource (lib "eagle-import") (part "C0402"))
    )
    (comp (ref "C144")
      (value "100nF")
      (footprint "eagle-import:0402")
      (libsource (lib "eagle-import") (part "C0402"))
    )
    (comp (ref "C145")
      (value "20nF")
      (footprint "eagle-import:0402")
      (libsource (lib "eagle-import") (part "C0402"))
    )
    (comp (ref "C146")
      (value "100nF")
      (footprint "eagle-import:0402")
      (libsource (lib "eagle-import") (part "C0402"))
    )
    (comp (ref "C147")
      (value "100nF")
      (footprint "eagle-import:0402")
      (libsource (lib "eagle-import") (part "C0402"))
    )
    (comp (ref "C148")
      (value "20nF")
      (footprint "eagle-import:0402")
      (libsource (lib "eagle-import") (part "C0402"))
    )
    (comp (ref "C149")
      (value "100nF")
      (footprint "eagle-import:0402")
      (libsource (lib "eagle-import") (part "C0402"))
    )
    (comp (ref "C150")
      (value "100nF")
      (footprint "eagle-import:0402")
      (libsource (lib "eagle-import") (part "C0402"))
    )
    (comp (ref "CLR") (value "TP") (footprint "eagle-import:TP") (libsource (lib "eagle-import") (part "TP")))
    (comp (ref "IC22")
      (value "DAC8568")
      (footprint "eagle-import:TSSOP16")
      (libsource (lib "eagle-import") (part "DAC8568"))
    )
    (comp (ref "IC23")
      (value "MCP6001RT")
      (footprint "eagle-import:SOT23-5")
      (libsource (lib "eagle-import") (part "MCP6001RT"))
    )
    (comp (ref "IC24")
      (value "MCP6001RT")
      (footprint "eagle-import:SOT23-5")
      (libsource (lib "eagle-import") (part "MCP6001RT"))
    )
    (comp (ref "IC25")
      (value "MCP6001RT")
      (footprint "eagle-import:SOT23-5")
      (libsource (lib "eagle-import") (part "MCP6001RT"))
    )
    (comp (ref "IC26")
      (value "MCP6001RT")
      (footprint "eagle-import:SOT23-5")
      (libsource (lib "eagle-import") (part "MCP6001RT"))
    )
    (comp (ref "IC27")
      (value "MCP6001RT")
      (footprint "eagle-import:SOT23-5")
      (libsource (lib "eagle-import") (part "MCP6001RT"))
    )
    (comp (ref "IC28")
      (value "MCP6001RT")
      (footprint "eagle-import:SOT23-5")
      (libsource (lib "eagle-import") (part "MCP6001RT"))
    )
    (comp (ref "IC29")
      (value "MCP6001RT")
      (footprint "eagle-import:SOT23-5")
      (libsource (lib "eagle-import") (part "MCP6001RT"))
    )
    (comp (ref "IC30")
      (value "MCP6001RT")
      (footprint "eagle-import:SOT23-5")
      (libsource (lib "eagle-import") (part "MCP6001RT"))
    )
    (comp (ref "IC31")
      (value "MCP6001RT")
      (footprint "eagle-import:SOT23-5")
      (libsource (lib "eagle-import") (part "MCP6001RT"))
    )
    (comp (ref "LDAC")
      (value "TP")
      (footprint "eagle-import:TP")
      (libsource (lib "eagle-import") (part "TP"))
    )
    (comp (ref "R86")
      (value "CRA034RF100RP05Z")
      (footprint "eagle-import:YC164-JR-0733RL")
      (fields
        (field (name "MANUFACTURER") "Yageo")
        (field (name "MPN") "YC164-JR-0733RL")
        (field (name "CREATED_BY") "PCBLayout.com")
      )
      (libsource (lib "eagle-import") (part "YC164-JR-0733RL"))
    )
    (comp (ref "R87")
      (value "10K 0.1%")
      (footprint "eagle-import:0402")
      (libsource (lib "eagle-import") (part "R0402"))
    )
    (comp (ref "R88")
      (value "10K 0.1%")
      (footprint "eagle-import:0402")
      (libsource (lib "eagle-import") (part "R0402"))
    )
    (comp (ref "R89")
      (value "43K 0.1%")
      (footprint "eagle-import:0402")
      (libsource (lib "eagle-import") (part "R0402"))
    )
    (comp (ref "R90")
      (value "68R 1%")
      (footprint "eagle-import:0402")
      (libsource (lib "eagle-import") (part "R0402"))
    )
    (comp (ref "R91")
      (value "10K 0.1%")
      (footprint "eagle-import:0402")
      (libsource (lib "eagle-import") (part "R0402"))
    )
    (comp (ref "R92")
      (value "10K 0.1%")
      (footprint "eagle-import:0402")
      (libsource (lib "eagle-import") (part "R0402"))
    )
    (comp (ref "R93")
      (value "43K 0.1%")
      (footprint "eagle-import:0402")
      (libsource (lib "eagle-import") (part "R0402"))
    )
    (comp (ref "R94")
      (value "68R 1%")
      (footprint "eagle-import:0402")
      (libsource (lib "eagle-import") (part "R0402"))
    )
    (comp (ref "R95")
      (value "10K 0.1%")
      (footprint "eagle-import:0402")
      (libsource (lib "eagle-import") (part "R0402"))
    )
    (comp (ref "R96")
      (value "10K 0.1%")
      (footprint "eagle-import:0402")
      (libsource (lib "eagle-import") (part "R0402"))
    )
    (comp (ref "R97")
      (value "43K 0.1%")
      (footprint "eagle-import:0402")
      (libsource (lib "eagle-import") (part "R0402"))
    )
    (comp (ref "R98")
      (value "68R 1%")
      (footprint "eagle-import:0402")
      (libsource (lib "eagle-import") (part "R0402"))
    )
    (comp (ref "R99")
      (value "10K 0.1%")
      (footprint "eagle-import:0402")
      (libsource (lib "eagle-import") (part "R0402"))
    )
    (comp (ref "R100")
      (value "10K 0.1%")
      (footprint "eagle-import:0402")
      (libsource (lib "eagle-import") (part "R0402"))
    )
    (comp (ref "R101")
      (value "43K 0.1%")
      (footprint "eagle-import:0402")
      (libsource (lib "eagle-import") (part "R0402"))
    )
    (comp (ref "R102")
      (value "68R 1%")
      (footprint "eagle-import:0402")
      (libsource (lib "eagle-import") (part "R0402"))
    )
    (comp (ref "R103")
      (value "10K 0.1%")
      (footprint "eagle-import:0402")
      (libsource (lib "eagle-import") (part "R0402"))
    )
    (comp (ref "R104")
      (value "10K 0.1%")
      (footprint "eagle-import:0402")
      (libsource (lib "eagle-import") (part "R0402"))
    )
    (comp (ref "R105")
      (value "43K 0.1%")
      (footprint "eagle-import:0402")
      (libsource (lib "eagle-import") (part "R0402"))
    )
    (comp (ref "R106")
      (value "68R 1%")
      (footprint "eagle-import:0402")
      (libsource (lib "eagle-import") (part "R0402"))
    )
    (comp (ref "R107")
      (value "10K 0.1%")
      (footprint "eagle-import:0402")
      (libsource (lib "eagle-import") (part "R0402"))
    )
    (comp (ref "R108")
      (value "10K 0.1%")
      (footprint "eagle-import:0402")
      (libsource (lib "eagle-import") (part "R0402"))
    )
    (comp (ref "R109")
      (value "43K 0.1%")
      (footprint "eagle-import:0402")
      (libsource (lib "eagle-import") (part "R0402"))
    )
    (comp (ref "R110")
      (value "68R 1%")
      (footprint "eagle-import:0402")
      (libsource (lib "eagle-import") (part "R0402"))
    )
    (comp (ref "R111")
      (value "10K 0.1%")
      (footprint "eagle-import:0402")
      (libsource (lib "eagle-import") (part "R0402"))
    )
    (comp (ref "R112")
      (value "10K 0.1%")
      (footprint "eagle-import:0402")
      (libsource (lib "eagle-import") (part "R0402"))
    )
    (comp (ref "R113")
      (value "43K 0.1%")
      (footprint "eagle-import:0402")
      (libsource (lib "eagle-import") (part "R0402"))
    )
    (comp (ref "R114")
      (value "68R 1%")
      (footprint "eagle-import:0402")
      (libsource (lib "eagle-import") (part "R0402"))
    )
    (comp (ref "R115")
      (value "10K 0.1%")
      (footprint "eagle-import:0402")
      (libsource (lib "eagle-import") (part "R0402"))
    )
    (comp (ref "R116")
      (value "10K 0.1%")
      (footprint "eagle-import:0402")
      (libsource (lib "eagle-import") (part "R0402"))
    )
    (comp (ref "R117")
      (value "43K 0.1%")
      (footprint "eagle-import:0402")
      (libsource (lib "eagle-import") (part "R0402"))
    )
    (comp (ref "R118")
      (value "68R 1%")
      (footprint "eagle-import:0402")
      (libsource (lib "eagle-import") (part "R0402"))
    )
    (comp (ref "SYNC")
      (value "TP")
      (footprint "eagle-import:TP")
      (libsource (lib "eagle-import") (part "TP"))
    )
    (comp (ref "TPD0")
      (value "TP")
      (footprint "eagle-import:TP")
      (libsource (lib "eagle-import") (part "TP"))
    )
    (comp (ref "TP_3V3")
      (value "TP")
      (footprint "eagle-import:TP")
      (libsource (lib "eagle-import") (part "TP"))
    )
    (comp (ref "TP_GND")
      (value "TP")
      (footprint "eagle-import:TP")
      (libsource (lib "eagle-import") (part "TP"))
    )
    (comp (ref "VREF_DAC")
      (value "TP")
      (footprint "eagle-import:TP")
      (libsource (lib "eagle-import") (part "TP"))
    )
    (comp (ref "C151")
      (value "1uF")
      (footprint "eagle-import:0402")
      (libsource (lib "eagle-import") (part "C0402"))
    )
    (comp (ref "C152")
      (value "100nF")
      (footprint "eagle-import:0402")
      (libsource (lib "eagle-import") (part "C0402"))
    )
    (comp (ref "C153")
      (value "1uF")
      (footprint "eagle-import:0402")
      (libsource (lib "eagle-import") (part "C0402"))
    )
    (comp (ref "C154")
      (value "100nF")
      (footprint "eagle-import:0402")
      (libsource (lib "eagle-import") (part "C0402"))
    )
    (comp (ref "C155")
      (value "1uF")
      (footprint "eagle-import:0402")
      (libsource (lib "eagle-import") (part "C0402"))
    )
    (comp (ref "C156")
      (value "100nF")
      (footprint "eagle-import:0402")
      (libsource (lib "eagle-import") (part "C0402"))
    )
    (comp (ref "C157")
      (value "1uF")
      (footprint "eagle-import:0402")
      (libsource (lib "eagle-import") (part "C0402"))
    )
    (comp (ref "C158")
      (value "100nF")
      (footprint "eagle-import:0402")
      (libsource (lib "eagle-import") (part "C0402"))
    )
    (comp (ref "C159")
      (value "1uF")
      (footprint "eagle-import:0402")
      (libsource (lib "eagle-import") (part "C0402"))
    )
    (comp (ref "C160")
      (value "100nF")
      (footprint "eagle-import:0402")
      (libsource (lib "eagle-import") (part "C0402"))
    )
    (comp (ref "C161")
      (value "1uF")
      (footprint "eagle-import:0402")
      (libsource (lib "eagle-import") (part "C0402"))
    )
    (comp (ref "C162")
      (value "100nF")
      (footprint "eagle-import:0402")
      (libsource (lib "eagle-import") (part "C0402"))
    )
    (comp (ref "C163")
      (value "1uF")
      (footprint "eagle-import:0402")
      (libsource (lib "eagle-import") (part "C0402"))
    )
    (comp (ref "C164")
      (value "100nF")
      (footprint "eagle-import:0402")
      (libsource (lib "eagle-import") (part "C0402"))
    )
    (comp (ref "C165")
      (value "1uF")
      (footprint "eagle-import:0402")
      (libsource (lib "eagle-import") (part "C0402"))
    )
    (comp (ref "C166")
      (value "100nF")
      (footprint "eagle-import:0402")
      (libsource (lib "eagle-import") (part "C0402"))
    )
    (comp (ref "C167")
      (value "1uF")
      (footprint "eagle-import:0402")
      (libsource (lib "eagle-import") (part "C0402"))
    )
    (comp (ref "C168")
      (value "100nF")
      (footprint "eagle-import:0402")
      (libsource (lib "eagle-import") (part "C0402"))
    )
    (comp (ref "C169")
      (value "1uF")
      (footprint "eagle-import:0402")
      (libsource (lib "eagle-import") (part "C0402"))
    )
    (comp (ref "C170")
      (value "100nF")
      (footprint "eagle-import:0402")
      (libsource (lib "eagle-import") (part "C0402"))
    )
    (comp (ref "C171")
      (value "100nF")
      (footprint "eagle-import:0603")
      (libsource (lib "eagle-import") (part "C0603"))
    )
    (comp (ref "DIO_CS")
      (value "TP")
      (footprint "eagle-import:TP")
      (libsource (lib "eagle-import") (part "TP"))
    )
    (comp (ref "DIO_EN")
      (value "TP")
      (footprint "eagle-import:TP")
      (libsource (lib "eagle-import") (part "TP"))
    )
    (comp (ref "DIO_GND")
      (value "TP")
      (footprint "eagle-import:TP")
      (libsource (lib "eagle-import") (part "TP"))
    )
    (comp (ref "DIO_LS")
      (value "TP")
      (footprint "eagle-import:TP")
      (libsource (lib "eagle-import") (part "TP"))
    )
    (comp (ref "DIO_RST")
      (value "TP")
      (footprint "eagle-import:TP")
      (libsource (lib "eagle-import") (part "TP"))
    )
    (comp (ref "DIO_VREF")
      (value "TP")
      (footprint "eagle-import:TP")
      (libsource (lib "eagle-import") (part "TP"))
    )
    (comp (ref "IC32")
      (value "LSF0108")
      (footprint "eagle-import:VQFN20")
      (libsource (lib "eagle-import") (part "LSF0108-Q1"))
    )
    (comp (ref "IC33")
      (value "LSF0108")
      (footprint "eagle-import:VQFN20")
      (libsource (lib "eagle-import") (part "LSF0108-Q1"))
    )
    (comp (ref "IC34")
      (value "LSF0108")
      (footprint "eagle-import:VQFN20")
      (libsource (lib "eagle-import") (part "LSF0108-Q1"))
    )
    (comp (ref "IC35")
      (value "LSF0108")
      (footprint "eagle-import:VQFN20")
      (libsource (lib "eagle-import") (part "LSF0108-Q1"))
    )
    (comp (ref "IC36")
      (value "MCP23S18")
      (footprint "eagle-import:QFN50P400X400X100-25T265")
      (libsource (lib "eagle-import") (part "MCP23S18"))
    )
    (comp (ref "IC37")
      (value "MCP23S18")
      (footprint "eagle-import:QFN50P400X400X100-25T265")
      (libsource (lib "eagle-import") (part "MCP23S18"))
    )
    (comp (ref "IC38")
      (value "SN74LVC2G66")
      (footprint "eagle-import:SOP50P310X90-8N")
      (libsource (lib "eagle-import") (part "SN74LVC2G66"))
    )
    (comp (ref "IC39")
      (value "74LVC1G04")
      (footprint "eagle-import:SOT95P280X145-5N")
      (libsource (lib "eagle-import") (part "74LVC1G04"))
    )
    (comp (ref "R119")
      (value "YC164-JR-0733RL")
      (footprint "eagle-import:YC164-JR-0733RL")
      (fields (field (name "MANUFACTURER") "Yageo") (field (name "CREATED_BY") "PCBLayout.com"))
      (libsource (lib "eagle-import") (part "YC164-JR-0733RL"))
    )
    (comp (ref "R120")
      (value "YC164-JR-0733RL")
      (footprint "eagle-import:YC164-JR-0733RL")
      (fields (field (name "MANUFACTURER") "Yageo") (field (name "CREATED_BY") "PCBLayout.com"))
      (libsource (lib "eagle-import") (part "YC164-JR-0733RL"))
    )
    (comp (ref "R121")
      (value "YC164-JR-0733RL")
      (footprint "eagle-import:YC164-JR-0733RL")
      (fields (field (name "MANUFACTURER") "Yageo") (field (name "CREATED_BY") "PCBLayout.com"))
      (libsource (lib "eagle-import") (part "YC164-JR-0733RL"))
    )
    (comp (ref "R122")
      (value "YC164-JR-0733RL")
      (footprint "eagle-import:YC164-JR-0733RL")
      (fields (field (name "MANUFACTURER") "Yageo") (field (name "CREATED_BY") "PCBLayout.com"))
      (libsource (lib "eagle-import") (part "YC164-JR-0733RL"))
    )
    (comp (ref "R123")
      (value "YC164-JR-0733RL")
      (footprint "eagle-import:YC164-JR-0733RL")
      (fields (field (name "MANUFACTURER") "Yageo") (field (name "CREATED_BY") "PCBLayout.com"))
      (libsource (lib "eagle-import") (part "YC164-JR-0733RL"))
    )
    (comp (ref "R124")
      (value "YC164-JR-0733RL")
      (footprint "eagle-import:YC164-JR-0733RL")
      (fields (field (name "MANUFACTURER") "Yageo") (field (name "CREATED_BY") "PCBLayout.com"))
      (libsource (lib "eagle-import") (part "YC164-JR-0733RL"))
    )
    (comp (ref "R125")
      (value "YC164-JR-0733RL")
      (footprint "eagle-import:YC164-JR-0733RL")
      (fields (field (name "MANUFACTURER") "Yageo") (field (name "CREATED_BY") "PCBLayout.com"))
      (libsource (lib "eagle-import") (part "YC164-JR-0733RL"))
    )
    (comp (ref "R126")
      (value "YC164-JR-0733RL")
      (footprint "eagle-import:YC164-JR-0733RL")
      (fields (field (name "MANUFACTURER") "Yageo") (field (name "CREATED_BY") "PCBLayout.com"))
      (libsource (lib "eagle-import") (part "YC164-JR-0733RL"))
    )
    (comp (ref "R127")
      (value "200K")
      (footprint "eagle-import:0402")
      (libsource (lib "eagle-import") (part "R0402"))
    )
    (comp (ref "R128")
      (value "200K")
      (footprint "eagle-import:0402")
      (libsource (lib "eagle-import") (part "R0402"))
    )
    (comp (ref "R129")
      (value "200K")
      (footprint "eagle-import:0402")
      (libsource (lib "eagle-import") (part "R0402"))
    )
    (comp (ref "R130")
      (value "200K")
      (footprint "eagle-import:0402")
      (libsource (lib "eagle-import") (part "R0402"))
    )
    (comp (ref "J1")
      (value "10164227-1001A1RLF")
      (footprint "eagle-import:AMPHENOL_10164227-1001A1RLF")
      (fields (field (name "MANUFACTURER") "Amphenol"))
      (libsource (lib "eagle-import") (part "10164227-1001A1RLF"))
    )
    (comp (ref "J2")
      (value "10164227-1001A1RLF")
      (footprint "eagle-import:AMPHENOL_10164227-1001A1RLF")
      (fields (field (name "MANUFACTURER") "Amphenol"))
      (libsource (lib "eagle-import") (part "10164227-1001A1RLF"))
    )
    (comp (ref "BT1")
      (value "79523141")
      (footprint "eagle-import:79523141")
      (fields
        (field (name "DIGIKEY_PART_NO") "732-12323-2-ND")
        (field (name "MANUFACTURER") "Wurth Electronics Inc.")
        (field (name "CREATED_BY") "PCBLayout.com")
      )
      (libsource (lib "eagle-import") (part "79523141"))
    )
    (comp (ref "C9")
      (value "100nF")
      (footprint "eagle-import:0402")
      (libsource (lib "eagle-import") (part "C0402"))
    )
    (comp (ref "C10")
      (value "100nF")
      (footprint "eagle-import:0402")
      (libsource (lib "eagle-import") (part "C0402"))
    )
    (comp (ref "C11")
      (value "100nF")
      (footprint "eagle-import:0402")
      (libsource (lib "eagle-import") (part "C0402"))
    )
    (comp (ref "CON1")
      (value "CON-1X4")
      (footprint "eagle-import:1X4")
      (libsource (lib "eagle-import") (part "CON-1X4"))
    )
    (comp (ref "D1")
      (value "TPD4EUSB30")
      (footprint "eagle-import:USON")
      (libsource (lib "eagle-import") (part "TPD4EUSB30"))
    )
    (comp (ref "D2")
      (value "TPD4EUSB30")
      (footprint "eagle-import:USON")
      (libsource (lib "eagle-import") (part "TPD4EUSB30"))
    )
    (comp (ref "ETH1")
      (value "G16LX-188S7-1G-GO-Y")
      (footprint "eagle-import:MAGJACK_POE")
      (libsource (lib "eagle-import") (part "MAGJACK-POE"))
    )
    (comp (ref "GPIO")
      (value "CON-2X20")
      (footprint "eagle-import:2X20")
      (libsource (lib "eagle-import") (part "CON-2X20"))
    )
    (comp (ref "IC1")
      (value "RT9742GGJ5")
      (footprint "eagle-import:SOT23-5")
      (libsource (lib "eagle-import") (part "RT9742GGJ5"))
    )
    (comp (ref "IC3")
      (value "74LVC1G07")
      (footprint "eagle-import:SOT23-5")
      (libsource (lib "eagle-import") (part "74LVC1G07"))
    )
    (comp (ref "JP2")
      (value "CON-2X7")
      (footprint "eagle-import:2X7")
      (libsource (lib "eagle-import") (part "CON-2X7"))
    )
    (comp (ref "JP3")
      (value "CON-2X2")
      (footprint "eagle-import:2X2")
      (libsource (lib "eagle-import") (part "CON-2X2"))
    )
    (comp (ref "JP4")
      (value "POE")
      (footprint "eagle-import:2X2")
      (libsource (lib "eagle-import") (part "CON-2X2"))
    )
    (comp (ref "LED1")
      (value "Green")
      (footprint "eagle-import:CHIPLED_0805")
      (libsource (lib "eagle-import") (part "LEDCHIPLED_0805"))
    )
    (comp (ref "R5")
      (value "1K")
      (footprint "eagle-import:0402")
      (libsource (lib "eagle-import") (part "R0402"))
    )
    (comp (ref "R6")
      (value "0R")
      (footprint "eagle-import:0402")
      (libsource (lib "eagle-import") (part "R0402"))
    )
    (comp (ref "R7")
      (value "DNI")
      (footprint "eagle-import:0402")
      (libsource (lib "eagle-import") (part "R0402"))
    )
    (comp (ref "R8")
      (value "470R")
      (footprint "eagle-import:0402")
      (libsource (lib "eagle-import") (part "R0402"))
    )
    (comp (ref "R9")
      (value "470R")
      (footprint "eagle-import:0402")
      (libsource (lib "eagle-import") (part "R0402"))
    )
    (comp (ref "SD1")
      (value "MICRO-SD")
      (footprint "eagle-import:MICROSD")
      (libsource (lib "eagle-import") (part "MICRO-SD"))
    )
    (comp (ref "SW1")
      (value "1825027-8")
      (footprint "eagle-import:SW2_1825027-C_TEC")
      (fields (field (name "COPYRIGHT") "Copyright (C) 2025 Ultra Librarian. All rights reserved."))
      (libsource (lib "eagle-import") (part "1825027-8"))
    )
    (comp (ref "TP-BTN")
      (value "TP")
      (footprint "eagle-import:TP")
      (libsource (lib "eagle-import") (part "TP"))
    )
    (comp (ref "TP-GREF")
      (value "TP")
      (footprint "eagle-import:TP")
      (libsource (lib "eagle-import") (part "TP"))
    )
    (comp (ref "TP-LED")
      (value "TP")
      (footprint "eagle-import:TP")
      (libsource (lib "eagle-import") (part "TP"))
    )
    (comp (ref "TP-VBAT")
      (value "TP")
      (footprint "eagle-import:TP")
      (libsource (lib "eagle-import") (part "TP"))
    )
    (comp (ref "TP-VSD")
      (value "TP")
      (footprint "eagle-import:TP")
      (libsource (lib "eagle-import") (part "TP"))
    )
    (comp (ref "C1")
      (value "C0402")
      (footprint "eagle-import:0402")
      (libsource (lib "eagle-import") (part "C0402"))
    )
    (comp (ref "C2")
      (value "C0402")
      (footprint "eagle-import:0402")
      (libsource (lib "eagle-import") (part "C0402"))
    )
    (comp (ref "C3")
      (value "100nF")
      (footprint "eagle-import:0402")
      (libsource (lib "eagle-import") (part "C0402"))
    )
    (comp (ref "C4")
      (value "100nF")
      (footprint "eagle-import:0402")
      (libsource (lib "eagle-import") (part "C0402"))
    )
    (comp (ref "C5")
      (value "100nF")
      (footprint "eagle-import:0402")
      (libsource (lib "eagle-import") (part "C0402"))
    )
    (comp (ref "C6")
      (value "10uF")
      (footprint "eagle-import:0805")
      (libsource (lib "eagle-import") (part "C0805"))
    )
    (comp (ref "C7")
      (value "10uF")
      (footprint "eagle-import:0805")
      (libsource (lib "eagle-import") (part "C0805"))
    )
    (comp (ref "C8")
      (value "100uF 16V")
      (footprint "eagle-import:100UF-16V")
      (libsource (lib "eagle-import") (part "CPOL"))
    )
    (comp (ref "HDMI1")
      (value "685119136923")
      (footprint "eagle-import:685119136923")
      (libsource (lib "eagle-import") (part "685119136923"))
    )
    (comp (ref "HDMI2")
      (value "685119136923")
      (footprint "eagle-import:685119136923")
      (libsource (lib "eagle-import") (part "685119136923"))
    )
    (comp (ref "IC2")
      (value "AP22653W6")
      (footprint "eagle-import:SOT23-6")
      (libsource (lib "eagle-import") (part "AP22653W6"))
    )
    (comp (ref "IC4")
      (value "RT9742NGV")
      (footprint "eagle-import:SOT23")
      (libsource (lib "eagle-import") (part "RT9742NGV"))
    )
    (comp (ref "J3")
      (value "FH12-22S-0.5SVA")
      (footprint "eagle-import:FH12-22S-0.5SH")
      (libsource (lib "eagle-import") (part "FH12-22S-0.5SVA"))
    )
    (comp (ref "J4")
      (value "FH12-22S-0.5SH(55)")
      (footprint "eagle-import:CONN_FH12-22S-0.5SH(55)_HIR")
      (fields (field (name "COPYRIGHT") "Copyright (C) 2025 Ultra Librarian. All rights reserved."))
      (libsource (lib "eagle-import") (part "FH12-22S-0.5SH(55)"))
    )
    (comp (ref "JP1")
      (value "CON-2X2")
      (footprint "eagle-import:2X2")
      (libsource (lib "eagle-import") (part "CON-2X2"))
    )
    (comp (ref "R1")
      (value "2.2K 1%")
      (footprint "eagle-import:0402")
      (libsource (lib "eagle-import") (part "R0402"))
    )
    (comp (ref "R2")
      (value "15K 1%")
      (footprint "eagle-import:0402")
      (libsource (lib "eagle-import") (part "R0402"))
    )
    (comp (ref "R3")
      (value "2.2K 1%")
      (footprint "eagle-import:0402")
      (libsource (lib "eagle-import") (part "R0402"))
    )
    (comp (ref "R4")
      (value "2.2K 1%")
      (footprint "eagle-import:0402")
      (libsource (lib "eagle-import") (part "R0402"))
    )
    (comp (ref "R61")
      (value "2.2K 1%")
      (footprint "eagle-import:0402")
      (libsource (lib "eagle-import") (part "R0402"))
    )
    (comp (ref "TP-5VHD")
      (value "TP")
      (footprint "eagle-import:TP")
      (libsource (lib "eagle-import") (part "TP"))
    )
    (comp (ref "TP-VBUS")
      (value "TP")
      (footprint "eagle-import:TP")
      (libsource (lib "eagle-import") (part "TP"))
    )
    (comp (ref "TP_5VP")
      (value "TP")
      (footprint "eagle-import:TP")
      (libsource (lib "eagle-import") (part "TP"))
    )
    (comp (ref "USB3")
      (value "692141030100")
      (footprint "eagle-import:692141030100")
      (libsource (lib "eagle-import") (part "692141030100"))
    )
    (comp (ref "USBC")
      (value "629722000214")
      (footprint "eagle-import:629722000214")
      (libsource (lib "eagle-import") (part "629722000214"))
    )
    (comp (ref "12VN")
      (value "TP")
      (footprint "eagle-import:TP")
      (libsource (lib "eagle-import") (part "TP"))
    )
    (comp (ref "12VP")
      (value "TP")
      (footprint "eagle-import:TP")
      (libsource (lib "eagle-import") (part "TP"))
    )
    (comp (ref "14VN")
      (value "TP")
      (footprint "eagle-import:TP")
      (libsource (lib "eagle-import") (part "TP"))
    )
    (comp (ref "14VP")
      (value "TP")
      (footprint "eagle-import:TP")
      (libsource (lib "eagle-import") (part "TP"))
    )
    (comp (ref "BUF") (value "TP") (footprint "eagle-import:TP") (libsource (lib "eagle-import") (part "TP")))
    (comp (ref "C26")
      (value "100uF 16V")
      (footprint "eagle-import:100UF-16V")
      (libsource (lib "eagle-import") (part "CPOL"))
    )
    (comp (ref "C27")
      (value "100uF 16V")
      (footprint "eagle-import:100UF-16V")
      (libsource (lib "eagle-import") (part "CPOL"))
    )
    (comp (ref "C45")
      (value "100nF")
      (footprint "eagle-import:0402")
      (libsource (lib "eagle-import") (part "C0402"))
    )
    (comp (ref "C46")
      (value "100nF")
      (footprint "eagle-import:0402")
      (libsource (lib "eagle-import") (part "C0402"))
    )
    (comp (ref "C47")
      (value "10uF")
      (footprint "eagle-import:0805")
      (libsource (lib "eagle-import") (part "C0805"))
    )
    (comp (ref "C48")
      (value "C0805")
      (footprint "eagle-import:0805")
      (libsource (lib "eagle-import") (part "C0805"))
    )
    (comp (ref "C49")
      (value "100nF")
      (footprint "eagle-import:0402")
      (libsource (lib "eagle-import") (part "C0402"))
    )
    (comp (ref "C85")
      (value "4.7uF")
      (footprint "eagle-import:0805")
      (libsource (lib "eagle-import") (part "C0805"))
    )
    (comp (ref "C86")
      (value "100nF")
      (footprint "eagle-import:0805")
      (libsource (lib "eagle-import") (part "C0805"))
    )
    (comp (ref "C90")
      (value "10uF")
      (footprint "eagle-import:0805")
      (libsource (lib "eagle-import") (part "C0805"))
    )
    (comp (ref "C91")
      (value "10nF")
      (footprint "eagle-import:0805")
      (libsource (lib "eagle-import") (part "C0805"))
    )
    (comp (ref "C92")
      (value "4.7nF")
      (footprint "eagle-import:0805")
      (libsource (lib "eagle-import") (part "C0805"))
    )
    (comp (ref "C93")
      (value "22uF")
      (footprint "eagle-import:1206")
      (libsource (lib "eagle-import") (part "C1206"))
    )
    (comp (ref "C94")
      (value "22uF")
      (footprint "eagle-import:1206")
      (libsource (lib "eagle-import") (part "C1206"))
    )
    (comp (ref "C95")
      (value "22uF")
      (footprint "eagle-import:1206")
      (libsource (lib "eagle-import") (part "C1206"))
    )
    (comp (ref "C96")
      (value "22uF")
      (footprint "eagle-import:1206")
      (libsource (lib "eagle-import") (part "C1206"))
    )
    (comp (ref "C97")
      (value "22uF")
      (footprint "eagle-import:1206")
      (libsource (lib "eagle-import") (part "C1206"))
    )
    (comp (ref "C98")
      (value "22uF")
      (footprint "eagle-import:1206")
      (libsource (lib "eagle-import") (part "C1206"))
    )
    (comp (ref "C99")
      (value "220nF")
      (footprint "eagle-import:0402")
      (libsource (lib "eagle-import") (part "C0402"))
    )
    (comp (ref "C100")
      (value "10pF")
      (footprint "eagle-import:0402")
      (libsource (lib "eagle-import") (part "C0402"))
    )
    (comp (ref "C101")
      (value "10pF")
      (footprint "eagle-import:0402")
      (libsource (lib "eagle-import") (part "C0402"))
    )
    (comp (ref "C102")
      (value "10uF")
      (footprint "eagle-import:1206")
      (libsource (lib "eagle-import") (part "C1206"))
    )
    (comp (ref "C103")
      (value "10nF")
      (footprint "eagle-import:0402")
      (libsource (lib "eagle-import") (part "C0402"))
    )
    (comp (ref "C104")
      (value "10uF")
      (footprint "eagle-import:1206")
      (libsource (lib "eagle-import") (part "C1206"))
    )
    (comp (ref "C105")
      (value "220nF")
      (footprint "eagle-import:0402")
      (libsource (lib "eagle-import") (part "C0402"))
    )
    (comp (ref "C106")
      (value "10nF")
      (footprint "eagle-import:0402")
      (libsource (lib "eagle-import") (part "C0402"))
    )
    (comp (ref "C107")
      (value "10nF")
      (footprint "eagle-import:0402")
      (libsource (lib "eagle-import") (part "C0402"))
    )
    (comp (ref "C108")
      (value "22uF")
      (footprint "eagle-import:1206")
      (libsource (lib "eagle-import") (part "C1206"))
    )
    (comp (ref "C109")
      (value "22uF")
      (footprint "eagle-import:1206")
      (libsource (lib "eagle-import") (part "C1206"))
    )
    (comp (ref "C120")
      (value "100nF")
      (footprint "eagle-import:0402")
      (libsource (lib "eagle-import") (part "C0402"))
    )
    (comp (ref "C121")
      (value "100nF")
      (footprint "eagle-import:0402")
      (libsource (lib "eagle-import") (part "C0402"))
    )
    (comp (ref "D3")
      (value "SS12")
      (footprint "eagle-import:SMA")
      (fields
        (field (name "DIGIKEY_PART_NUMBER") "SS12FSCT-ND")
        (field (name "MANUFACTURER") "ON Semiconductor")
        (field (name "CREATED_BY") "PCBLayout.com")
      )
      (libsource (lib "eagle-import") (part "SS12"))
    )
    (comp (ref "D4")
      (value "SS12")
      (footprint "eagle-import:SMA")
      (fields
        (field (name "DIGIKEY_PART_NUMBER") "SS12FSCT-ND")
        (field (name "MANUFACTURER") "ON Semiconductor")
        (field (name "CREATED_BY") "PCBLayout.com")
      )
      (libsource (lib "eagle-import") (part "SS12"))
    )
    (comp (ref "IC12")
      (value "MCP1525T-I/TT")
      (footprint "eagle-import:SOT23")
      (libsource (lib "eagle-import") (part "MCP1525T-I/TT"))
    )
    (comp (ref "IC13")
      (value "MCP6001RT")
      (footprint "eagle-import:SOT23-5")
      (libsource (lib "eagle-import") (part "MCP6001RT"))
    )
    (comp (ref "IC14")
      (value "TPS65131")
      (footprint "eagle-import:VQFN24-4X4-THERMAL2.5X2.5")
      (libsource (lib "eagle-import") (part "TPS65131TRGERQ1"))
    )
    (comp (ref "IC15")
      (value "TPS7A39")
      (footprint "eagle-import:WSON10-3X3")
      (libsource (lib "eagle-import") (part "TPS7A3901DSCR"))
    )
    (comp (ref "IC18")
      (value "LDL1117S33R")
      (footprint "eagle-import:SOT230")
      (libsource (lib "eagle-import") (part "LDL1117S33R"))
    )
    (comp (ref "L3")
      (value "SRR5228A-4R7Y")
      (footprint "eagle-import:SRR5228A")
      (libsource (lib "eagle-import") (part "L"))
    )
    (comp (ref "L4")
      (value "SRR5228A-4R7Y")
      (footprint "eagle-import:SRR5228A")
      (libsource (lib "eagle-import") (part "L"))
    )
    (comp (ref "R14")
      (value "100R")
      (footprint "eagle-import:1206")
      (libsource (lib "eagle-import") (part "R1206"))
    )
    (comp (ref "R19")
      (value "950K 0.1%")
      (footprint "eagle-import:0402")
      (libsource (lib "eagle-import") (part "R0402"))
    )
    (comp (ref "R53")
      (value "R-TRIM")
      (footprint "eagle-import:TC33X")
      (libsource (lib "eagle-import") (part "R-TRIM"))
    )
    (comp (ref "R54")
      (value "R-TRIM")
      (footprint "eagle-import:TC33X")
      (libsource (lib "eagle-import") (part "R-TRIM"))
    )
    (comp (ref "R55")
      (value "R-TRIM")
      (footprint "eagle-import:TC33X")
      (libsource (lib "eagle-import") (part "R-TRIM"))
    )
    (comp (ref "R56")
      (value "R-TRIM")
      (footprint "eagle-import:TC33X")
      (libsource (lib "eagle-import") (part "R-TRIM"))
    )
    (comp (ref "R57")
      (value "102K 0.1%")
      (footprint "eagle-import:0402")
      (libsource (lib "eagle-import") (part "R0402"))
    )
    (comp (ref "R58")
      (value "1.2M 0.1%")
      (footprint "eagle-import:0402")
      (libsource (lib "eagle-import") (part "R0402"))
    )
    (comp (ref "R59")
      (value "137K 0.1%")
      (footprint "eagle-import:0402")
      (libsource (lib "eagle-import") (part "R0402"))
    )
    (comp (ref "R60")
      (value "75K 0.1%")
      (footprint "eagle-import:0402")
      (libsource (lib "eagle-import") (part "R0402"))
    )
    (comp (ref "R73")
      (value "10K 0.1%")
      (footprint "eagle-import:0402")
      (libsource (lib "eagle-import") (part "R0402"))
    )
    (comp (ref "R74")
      (value "90K 0.1%")
      (footprint "eagle-import:0402")
      (libsource (lib "eagle-import") (part "R0402"))
    )
    (comp (ref "R76")
      (value "10K 0.1%")
      (footprint "eagle-import:0402")
      (libsource (lib "eagle-import") (part "R0402"))
    )
    (comp (ref "T2")
      (value "IRLML5203")
      (footprint "eagle-import:MICRO3")
      (libsource (lib "eagle-import") (part "IRLML5203"))
    )
    (comp (ref "TP_BSW_G")
      (value "TP")
      (footprint "eagle-import:TP")
      (libsource (lib "eagle-import") (part "TP"))
    )
    (comp (ref "TP_VFB_14VN")
      (value "TP")
      (footprint "eagle-import:TP")
      (libsource (lib "eagle-import") (part "TP"))
    )
    (comp (ref "TP_VFB_14VP")
      (value "TP")
      (footprint "eagle-import:TP")
      (libsource (lib "eagle-import") (part "TP"))
    )
    (comp (ref "TP_VREF_TPS")
      (value "TP")
      (footprint "eagle-import:TP")
      (libsource (lib "eagle-import") (part "TP"))
    )
    (comp (ref "VFB12VN")
      (value "TP")
      (footprint "eagle-import:TP")
      (libsource (lib "eagle-import") (part "TP"))
    )
    (comp (ref "VFB12VP")
      (value "TP")
      (footprint "eagle-import:TP")
      (libsource (lib "eagle-import") (part "TP"))
    )
  )
  (nets
    (net (code "1") (name "+1V8") (class "Default")
      (node (ref "J2") (pin "88") (pinfunction "88_88") (pintype "passive"))
      (node (ref "J2") (pin "90") (pinfunction "90_90") (pintype "passive"))
      (node (ref "R7") (pin "1") (pinfunction "1_1") (pintype "passive"))
    )
    (net (code "2") (name "+3V3") (class "Default")
      (node (ref "C122") (pin "1") (pinfunction "1_1") (pintype "passive"))
      (node (ref "C123") (pin "1") (pinfunction "1_1") (pintype "passive"))
      (node (ref "C126") (pin "1") (pinfunction "1_1") (pintype "passive"))
      (node (ref "C128") (pin "1") (pinfunction "1_1") (pintype "passive"))
      (node (ref "C131") (pin "1") (pinfunction "1_1") (pintype "passive"))
      (node (ref "C134") (pin "1") (pinfunction "1_1") (pintype "passive"))
      (node (ref "C137") (pin "1") (pinfunction "1_1") (pintype "passive"))
      (node (ref "C140") (pin "1") (pinfunction "1_1") (pintype "passive"))
      (node (ref "C143") (pin "1") (pinfunction "1_1") (pintype "passive"))
      (node (ref "C146") (pin "1") (pinfunction "1_1") (pintype "passive"))
      (node (ref "C149") (pin "1") (pinfunction "1_1") (pintype "passive"))
      (node (ref "C151") (pin "1") (pinfunction "1_1") (pintype "passive"))
      (node (ref "C152") (pin "1") (pinfunction "1_1") (pintype "passive"))
      (node (ref "C155") (pin "1") (pinfunction "1_1") (pintype "passive"))
      (node (ref "C156") (pin "1") (pinfunction "1_1") (pintype "passive"))
      (node (ref "C159") (pin "1") (pinfunction "1_1") (pintype "passive"))
      (node (ref "C160") (pin "1") (pinfunction "1_1") (pintype "passive"))
      (node (ref "C163") (pin "1") (pinfunction "1_1") (pintype "passive"))
      (node (ref "C164") (pin "1") (pinfunction "1_1") (pintype "passive"))
      (node (ref "C167") (pin "1") (pinfunction "1_1") (pintype "passive"))
      (node (ref "C168") (pin "1") (pinfunction "1_1") (pintype "passive"))
      (node (ref "C169") (pin "1") (pinfunction "1_1") (pintype "passive"))
      (node (ref "C170") (pin "1") (pinfunction "1_1") (pintype "passive"))
      (node (ref "C171") (pin "1") (pinfunction "1_1") (pintype "passive"))
      (node (ref "C21") (pin "1") (pinfunction "1_1") (pintype "passive"))
      (node (ref "C22") (pin "1") (pinfunction "1_1") (pintype "passive"))
      (node (ref "C25") (pin "1") (pinfunction "1_1") (pintype "passive"))
      (node (ref "C45") (pin "1") (pinfunction "1_1") (pintype "passive"))
      (node (ref "C47") (pin "1") (pinfunction "1_1") (pintype "passive"))
      (node (ref "C49") (pin "1") (pinfunction "1_1") (pintype "passive"))
      (node (ref "C50") (pin "1") (pinfunction "1_1") (pintype "passive"))
      (node (ref "C51") (pin "1") (pinfunction "1_1") (pintype "passive"))
      (node (ref "C64") (pin "1") (pinfunction "1_1") (pintype "passive"))
      (node (ref "C65") (pin "1") (pinfunction "1_1") (pintype "passive"))
      (node (ref "C76") (pin "1") (pinfunction "1_1") (pintype "passive"))
      (node (ref "C9") (pin "1") (pinfunction "1_1") (pintype "passive"))
      (node (ref "ETH1") (pin "18") (pinfunction "P18_18") (pintype "bidirectional"))
      (node (ref "ETH1") (pin "20") (pinfunction "P20_20") (pintype "bidirectional"))
      (node (ref "GPIO") (pin "1") (pinfunction "1_1") (pintype "bidirectional"))
      (node (ref "GPIO") (pin "17") (pinfunction "17_17") (pintype "bidirectional"))
      (node (ref "IC1") (pin "5") (pinfunction "IN_5") (pintype "power_in"))
      (node (ref "IC10") (pin "12") (pinfunction "AVDD_12") (pintype "power_in"))
      (node (ref "IC10") (pin "28") (pinfunction "DVDD_28") (pintype "power_in"))
      (node (ref "IC10") (pin "29") (pinfunction "AVDD_29") (pintype "power_in"))
      (node (ref "IC11") (pin "2") (pinfunction "V+_2") (pintype "power_in"))
      (node (ref "IC12") (pin "1") (pinfunction "VIN_1") (pintype "bidirectional"))
      (node (ref "IC13") (pin "2") (pinfunction "V+_2") (pintype "power_in"))
      (node (ref "IC16") (pin "8") (pinfunction "VCC_8") (pintype "power_in"))
      (node (ref "IC17") (pin "5") (pinfunction "V+_5") (pintype "bidirectional"))
      (node (ref "IC22") (pin "3") (pinfunction "AVDD_3") (pintype "power_in"))
      (node (ref "IC23") (pin "2") (pinfunction "V+_2") (pintype "power_in"))
      (node (ref "IC24") (pin "2") (pinfunction "V+_2") (pintype "power_in"))
      (node (ref "IC25") (pin "2") (pinfunction "V+_2") (pintype "power_in"))
      (node (ref "IC26") (pin "2") (pinfunction "V+_2") (pintype "power_in"))
      (node (ref "IC27") (pin "2") (pinfunction "V+_2") (pintype "power_in"))
      (node (ref "IC28") (pin "2") (pinfunction "V+_2") (pintype "power_in"))
      (node (ref "IC29") (pin "2") (pinfunction "V+_2") (pintype "power_in"))
      (node (ref "IC3") (pin "5") (pinfunction "VCC_5") (pintype "bidirectional"))
      (node (ref "IC30") (pin "2") (pinfunction "V+_2") (pintype "power_in"))
      (node (ref "IC31") (pin "2") (pinfunction "V+_2") (pintype "power_in"))
      (node (ref "IC32") (pin "2") (pinfunction "VREF_A_2") (pintype "power_in"))
      (node (ref "IC33") (pin "2") (pinfunction "VREF_A_2") (pintype "power_in"))
      (node (ref "IC34") (pin "2") (pinfunction "VREF_A_2") (pintype "power_in"))
      (node (ref "IC35") (pin "2") (pinfunction "VREF_A_2") (pintype "power_in"))
      (node (ref "IC36") (pin "8") (pinfunction "VDD_8") (pintype "power_in"))
      (node (ref "IC37") (pin "8") (pinfunction "VDD_8") (pintype "power_in"))
      (node (ref "IC38") (pin "1") (pinfunction "1A_1") (pintype "bidirectional"))
      (node (ref "IC38") (pin "8") (pinfunction "VCC_8") (pintype "power_in"))
      (node (ref "IC39") (pin "5") (pinfunction "V+_5") (pintype "bidirectional"))
      (node (ref "IC7") (pin "7") (pinfunction "DVDD_7") (pintype "power_in"))
      (node (ref "IC9") (pin "7") (pinfunction "DVDD_7") (pintype "power_in"))
      (node (ref "J2") (pin "84") (pinfunction "84_84") (pintype "passive"))
      (node (ref "J2") (pin "86") (pinfunction "86_86") (pintype "passive"))
      (node (ref "J3") (pin "22") (pinfunction "22_22") (pintype "passive"))
      (node (ref "J4") (pin "22") (pinfunction "22_22") (pintype "passive"))
      (node (ref "LED1") (pin "A") (pinfunction "A_A") (pintype "passive"))
      (node (ref "LED2") (pin "A") (pinfunction "A_A") (pintype "passive"))
      (node (ref "R16") (pin "1") (pinfunction "1_1") (pintype "passive"))
      (node (ref "R6") (pin "1") (pinfunction "1_1") (pintype "passive"))
      (node (ref "R61") (pin "2") (pinfunction "2_2") (pintype "passive"))
      (node (ref "R86") (pin "5") (pinfunction "5_5") (pintype "passive"))
      (node (ref "R86") (pin "6") (pinfunction "6_6") (pintype "passive"))
      (node (ref "R86") (pin "7") (pinfunction "7_7") (pintype "passive"))
      (node (ref "R86") (pin "8") (pinfunction "8_8") (pintype "passive"))
      (node (ref "TP_3V3") (pin "TP") (pinfunction "P$1_TP") (pintype "bidirectional"))
    )
    (net (code "3") (name "+3V3_EXT") (class "Default")
      (node (ref "C121") (pin "1") (pinfunction "1_1") (pintype "passive"))
      (node (ref "C27") (pin "1") (pinfunction "1_1") (pintype "passive"))
      (node (ref "IC18") (pin "2") (pinfunction "VOUT_2") (pintype "power_in"))
      (node (ref "IC18") (pin "4") (pinfunction "VOUT_4") (pintype "power_in"))
      (node (ref "J7") (pin "52") (pinfunction "52_52") (pintype "passive"))
      (node (ref "J7") (pin "67") (pinfunction "67_67") (pintype "passive"))
    )
    (net (code "4") (name "+5V") (class "Default")
      (node (ref "C1") (pin "1") (pinfunction "1_1") (pintype "passive"))
      (node (ref "C120") (pin "1") (pinfunction "1_1") (pintype "passive"))
      (node (ref "C18") (pin "1") (pinfunction "1_1") (pintype "passive"))
      (node (ref "C19") (pin "1") (pinfunction "1_1") (pintype "passive"))
      (node (ref "C2") (pin "1") (pinfunction "1_1") (pintype "passive"))
      (node (ref "C20") (pin "1") (pinfunction "1_1") (pintype "passive"))
      (node (ref "C26") (pin "1") (pinfunction "1_1") (pintype "passive"))
      (node (ref "C3") (pin "1") (pinfunction "1_1") (pintype "passive"))
      (node (ref "C5") (pin "1") (pinfunction "1_1") (pintype "passive"))
      (node (ref "C85") (pin "1") (pinfunction "1_1") (pintype "passive"))
      (node (ref "CON1") (pin "4") (pinfunction "P$4_4") (pintype "bidirectional"))
      (node (ref "GPIO") (pin "2") (pinfunction "2_2") (pintype "bidirectional"))
      (node (ref "GPIO") (pin "4") (pinfunction "4_4") (pintype "bidirectional"))
      (node (ref "IC14") (pin "5") (pinfunction "INN_5") (pintype "power_in"))
      (node (ref "IC14") (pin "6") (pinfunction "INN_6") (pintype "power_in"))
      (node (ref "IC18") (pin "3") (pinfunction "VIN_3") (pintype "power_in"))
      (node (ref "IC2") (pin "1") (pinfunction "IN_1") (pintype "bidirectional"))
      (node (ref "IC38") (pin "5") (pinfunction "2A_5") (pintype "bidirectional"))
      (node (ref "IC4") (pin "1") (pinfunction "IN_1") (pintype "power_in"))
      (node (ref "IC5") (pin "3") (pinfunction "VIN_3") (pintype "power_in"))
      (node (ref "J2") (pin "77") (pinfunction "77_77") (pintype "passive"))
      (node (ref "J2") (pin "79") (pinfunction "79_79") (pintype "passive"))
      (node (ref "J2") (pin "81") (pinfunction "81_81") (pintype "passive"))
      (node (ref "J2") (pin "83") (pinfunction "83_83") (pintype "passive"))
      (node (ref "J2") (pin "85") (pinfunction "85_85") (pintype "passive"))
      (node (ref "J2") (pin "87") (pinfunction "87_87") (pintype "passive"))
      (node (ref "J7") (pin "18") (pinfunction "18_18") (pintype "passive"))
      (node (ref "J7") (pin "33") (pinfunction "33_33") (pintype "passive"))
      (node (ref "R1") (pin "1") (pinfunction "1_1") (pintype "passive"))
      (node (ref "R14") (pin "2") (pinfunction "2_2") (pintype "passive"))
      (node (ref "T2") (pin "2") (pinfunction "S_2") (pintype "passive"))
      (node (ref "TP-5VP") (pin "TP") (pinfunction "P$1_TP") (pintype "bidirectional"))
      (node (ref "TP_5VP") (pin "TP") (pinfunction "P$1_TP") (pintype "bidirectional"))
      (node (ref "USBC") (pin "A4") (pinfunction "VBUS_A4") (pintype "passive"))
      (node (ref "USBC") (pin "A9") (pinfunction "VBUS1_A9") (pintype "passive"))
      (node (ref "USBC") (pin "B4") (pinfunction "VBUS3_B4") (pintype "passive"))
      (node (ref "USBC") (pin "B9") (pinfunction "VBUS2_B9") (pintype "passive"))
    )
    (net (code "5") (name "+12V") (class "Default")
      (node (ref "12VP") (pin "TP") (pinfunction "P$1_TP") (pintype "bidirectional"))
      (node (ref "C107") (pin "2") (pinfunction "2_2") (pintype "passive"))
      (node (ref "C108") (pin "1") (pinfunction "1_1") (pintype "passive"))
      (node (ref "C52") (pin "1") (pinfunction "1_1") (pintype "passive"))
      (node (ref "C53") (pin "1") (pinfunction "1_1") (pintype "passive"))
      (node (ref "C56") (pin "1") (pinfunction "1_1") (pintype "passive"))
      (node (ref "C57") (pin "1") (pinfunction "1_1") (pintype "passive"))
      (node (ref "C60") (pin "1") (pinfunction "1_1") (pintype "passive"))
      (node (ref "C61") (pin "1") (pinfunction "1_1") (pintype "passive"))
      (node (ref "C66") (pin "1") (pinfunction "1_1") (pintype "passive"))
      (node (ref "C67") (pin "1") (pinfunction "1_1") (pintype "passive"))
      (node (ref "IC15") (pin "10") (pinfunction "OUTP_10") (pintype "power_in"))
      (node (ref "IC6") (pin "14") (pinfunction "V+_14") (pintype "power_in"))
      (node (ref "IC7") (pin "26") (pinfunction "VDDH_26") (pintype "power_in"))
      (node (ref "IC8") (pin "14") (pinfunction "V+_14") (pintype "power_in"))
      (node (ref "IC9") (pin "26") (pinfunction "VDDH_26") (pintype "power_in"))
      (node (ref "R60") (pin "1") (pinfunction "1_1") (pintype "passive"))
    )
    (net (code "6") (name "+14V") (class "Default")
      (node (ref "14VP") (pin "TP") (pinfunction "P$1_TP") (pintype "bidirectional"))
      (node (ref "C100") (pin "1") (pinfunction "1_1") (pintype "passive"))
      (node (ref "C104") (pin "1") (pinfunction "1_1") (pintype "passive"))
      (node (ref "C93") (pin "1") (pinfunction "1_1") (pintype "passive"))
      (node (ref "C94") (pin "1") (pinfunction "1_1") (pintype "passive"))
      (node (ref "C95") (pin "1") (pinfunction "1_1") (pintype "passive"))
      (node (ref "D3") (pin "C") (pinfunction "C_C") (pintype "passive"))
      (node (ref "IC14") (pin "23") (pinfunction "VPOS_23") (pintype "power_in"))
      (node (ref "IC15") (pin "1") (pinfunction "INP_1") (pintype "power_in"))
      (node (ref "IC15") (pin "2") (pinfunction "EN_2") (pintype "input"))
      (node (ref "R19") (pin "1") (pinfunction "1_1") (pintype "passive"))
    )
    (net (code "7") (name "-12V") (class "Default")
      (node (ref "12VN") (pin "TP") (pinfunction "P$1_TP") (pintype "bidirectional"))
      (node (ref "C106") (pin "1") (pinfunction "1_1") (pintype "passive"))
      (node (ref "C109") (pin "1") (pinfunction "1_1") (pintype "passive"))
      (node (ref "C54") (pin "1") (pinfunction "1_1") (pintype "passive"))
      (node (ref "C55") (pin "1") (pinfunction "1_1") (pintype "passive"))
      (node (ref "C58") (pin "1") (pinfunction "1_1") (pintype "passive"))
      (node (ref "C59") (pin "1") (pinfunction "1_1") (pintype "passive"))
      (node (ref "C62") (pin "1") (pinfunction "1_1") (pintype "passive"))
      (node (ref "C63") (pin "1") (pinfunction "1_1") (pintype "passive"))
      (node (ref "C68") (pin "1") (pinfunction "1_1") (pintype "passive"))
      (node (ref "C69") (pin "1") (pinfunction "1_1") (pintype "passive"))
      (node (ref "IC15") (pin "6") (pinfunction "OUTN_6") (pintype "power_in"))
      (node (ref "IC6") (pin "3") (pinfunction "V-_3") (pintype "power_in"))
      (node (ref "IC7") (pin "27") (pinfunction "VSSH_27") (pintype "power_in"))
      (node (ref "IC7") (pin "29") (pinfunction "PAD_29") (pintype "power_in"))
      (node (ref "IC8") (pin "3") (pinfunction "V-_3") (pintype "power_in"))
      (node (ref "IC9") (pin "27") (pinfunction "VSSH_27") (pintype "power_in"))
      (node (ref "IC9") (pin "29") (pinfunction "PAD_29") (pintype "power_in"))
      (node (ref "R76") (pin "2") (pinfunction "2_2") (pintype "passive"))
    )
    (net (code "8") (name "-14V") (class "Default")
      (node (ref "14VN") (pin "TP") (pinfunction "P$1_TP") (pintype "bidirectional"))
      (node (ref "C101") (pin "1") (pinfunction "1_1") (pintype "passive"))
      (node (ref "C102") (pin "1") (pinfunction "1_1") (pintype "passive"))
      (node (ref "C96") (pin "1") (pinfunction "1_1") (pintype "passive"))
      (node (ref "C97") (pin "1") (pinfunction "1_1") (pintype "passive"))
      (node (ref "C98") (pin "1") (pinfunction "1_1") (pintype "passive"))
      (node (ref "D4") (pin "A") (pinfunction "A_A") (pintype "passive"))
      (node (ref "IC14") (pin "15") (pinfunction "VNEG_15") (pintype "power_in"))
      (node (ref "IC15") (pin "5") (pinfunction "INN_5") (pintype "power_in"))
      (node (ref "R59") (pin "2") (pinfunction "2_2") (pintype "passive"))
    )
    (net (code "9") (name "ADA_A_IO0") (class "Default")
      (node (ref "IC6") (pin "1") (pinfunction "A0_1") (pintype "input"))
      (node (ref "IC7") (pin "18") (pinfunction "GPIO0_18") (pintype "bidirectional"))
    )
    (net (code "10") (name "ADA_A_IO1") (class "Default")
      (node (ref "IC6") (pin "16") (pinfunction "A1_16") (pintype "input"))
      (node (ref "IC7") (pin "17") (pinfunction "GPIO1_17") (pintype "bidirectional"))
    )
    (net (code "11") (name "ADA_A_IO2") (class "Default")
      (node (ref "IC6") (pin "2") (pinfunction "EN_2") (pintype "input"))
      (node (ref "IC7") (pin "16") (pinfunction "GPIO2_16") (pintype "bidirectional"))
    )
    (net (code "12") (name "ADA_B_IO0") (class "Default")
      (node (ref "IC8") (pin "1") (pinfunction "A0_1") (pintype "input"))
      (node (ref "IC9") (pin "18") (pinfunction "GPIO0_18") (pintype "bidirectional"))
    )
    (net (code "13") (name "ADA_B_IO1") (class "Default")
      (node (ref "IC8") (pin "16") (pinfunction "A1_16") (pintype "input"))
      (node (ref "IC9") (pin "17") (pinfunction "GPIO1_17") (pintype "bidirectional"))
    )
    (net (code "14") (name "ADA_B_IO2") (class "Default")
      (node (ref "IC8") (pin "2") (pinfunction "EN_2") (pintype "input"))
      (node (ref "IC9") (pin "16") (pinfunction "GPIO2_16") (pintype "bidirectional"))
    )
    (net (code "15") (name "ADC_AIN_N") (class "Default")
      (node (ref "C24") (pin "2") (pinfunction "2_2") (pintype "passive"))
      (node (ref "C41") (pin "2") (pinfunction "2_2") (pintype "passive"))
      (node (ref "R21") (pin "1") (pinfunction "1_1") (pintype "passive"))
      (node (ref "R46") (pin "1") (pinfunction "1_1") (pintype "passive"))
    )
    (net (code "16") (name "ADC_AIN_P") (class "Default")
      (node (ref "C23") (pin "1") (pinfunction "1_1") (pintype "passive"))
      (node (ref "C41") (pin "1") (pinfunction "1_1") (pintype "passive"))
      (node (ref "R20") (pin "1") (pinfunction "1_1") (pintype "passive"))
      (node (ref "R45") (pin "2") (pinfunction "2_2") (pintype "passive"))
    )
    (net (code "17") (name "ADC_BIN_N") (class "Default")
      (node (ref "C43") (pin "2") (pinfunction "2_2") (pintype "passive"))
      (node (ref "C44") (pin "2") (pinfunction "2_2") (pintype "passive"))
      (node (ref "R23") (pin "1") (pinfunction "1_1") (pintype "passive"))
      (node (ref "R48") (pin "2") (pinfunction "2_2") (pintype "passive"))
    )
    (net (code "18") (name "ADC_BIN_P") (class "Default")
      (node (ref "C42") (pin "1") (pinfunction "1_1") (pintype "passive"))
      (node (ref "C44") (pin "1") (pinfunction "1_1") (pintype "passive"))
      (node (ref "R22") (pin "1") (pinfunction "1_1") (pintype "passive"))
      (node (ref "R47") (pin "1") (pinfunction "1_1") (pintype "passive"))
    )
    (net (code "19") (name "ADC_IN0") (class "Default")
      (node (ref "IC10") (pin "1") (pinfunction "AINP_A_1") (pintype "input"))
      (node (ref "R45") (pin "1") (pinfunction "1_1") (pintype "passive"))
    )
    (net (code "20") (name "ADC_IN1") (class "Default")
      (node (ref "IC10") (pin "2") (pinfunction "AINM_A_2") (pintype "input"))
      (node (ref "R46") (pin "2") (pinfunction "2_2") (pintype "passive"))
    )
    (net (code "21") (name "ADC_IN2") (class "Default")
      (node (ref "IC10") (pin "8") (pinfunction "AINP_B_8") (pintype "input"))
      (node (ref "R48") (pin "1") (pinfunction "1_1") (pintype "passive"))
    )
    (net (code "22") (name "ADC_IN3") (class "Default")
      (node (ref "IC10") (pin "7") (pinfunction "AINM_B_7") (pintype "input"))
      (node (ref "R47") (pin "2") (pinfunction "2_2") (pintype "passive"))
    )
    (net (code "23") (name "ADC_RDY") (class "Default")
      (node (ref "IC10") (pin "25") (pinfunction "READY/STROBE_25") (pintype "output"))
      (node (ref "R36") (pin "1") (pinfunction "1_1") (pintype "passive"))
    )
    (net (code "24") (name "AO_0") (class "Default")
      (node (ref "C127") (pin "1") (pinfunction "1_1") (pintype "passive"))
      (node (ref "J7") (pin "29") (pinfunction "29_29") (pintype "passive"))
      (node (ref "R89") (pin "2") (pinfunction "2_2") (pintype "passive"))
      (node (ref "R90") (pin "2") (pinfunction "2_2") (pintype "passive"))
    )
    (net (code "25") (name "AO_1") (class "Default")
      (node (ref "C130") (pin "1") (pinfunction "1_1") (pintype "passive"))
      (node (ref "J7") (pin "63") (pinfunction "63_63") (pintype "passive"))
      (node (ref "R93") (pin "2") (pinfunction "2_2") (pintype "passive"))
      (node (ref "R94") (pin "2") (pinfunction "2_2") (pintype "passive"))
    )
    (net (code "26") (name "AO_2") (class "Default")
      (node (ref "C133") (pin "1") (pinfunction "1_1") (pintype "passive"))
      (node (ref "J7") (pin "30") (pinfunction "30_30") (pintype "passive"))
      (node (ref "R97") (pin "2") (pinfunction "2_2") (pintype "passive"))
      (node (ref "R98") (pin "2") (pinfunction "2_2") (pintype "passive"))
    )
    (net (code "27") (name "AO_3") (class "Default")
      (node (ref "C136") (pin "1") (pinfunction "1_1") (pintype "passive"))
      (node (ref "J7") (pin "64") (pinfunction "64_64") (pintype "passive"))
      (node (ref "R101") (pin "2") (pinfunction "2_2") (pintype "passive"))
      (node (ref "R102") (pin "2") (pinfunction "2_2") (pintype "passive"))
    )
    (net (code "28") (name "AO_4") (class "Default")
      (node (ref "C139") (pin "1") (pinfunction "1_1") (pintype "passive"))
      (node (ref "J7") (pin "31") (pinfunction "31_31") (pintype "passive"))
      (node (ref "R105") (pin "2") (pinfunction "2_2") (pintype "passive"))
      (node (ref "R106") (pin "2") (pinfunction "2_2") (pintype "passive"))
    )
    (net (code "29") (name "AO_5") (class "Default")
      (node (ref "C142") (pin "1") (pinfunction "1_1") (pintype "passive"))
      (node (ref "J7") (pin "65") (pinfunction "65_65") (pintype "passive"))
      (node (ref "R109") (pin "2") (pinfunction "2_2") (pintype "passive"))
      (node (ref "R110") (pin "2") (pinfunction "2_2") (pintype "passive"))
    )
    (net (code "30") (name "AO_6") (class "Default")
      (node (ref "C145") (pin "1") (pinfunction "1_1") (pintype "passive"))
      (node (ref "J7") (pin "32") (pinfunction "32_32") (pintype "passive"))
      (node (ref "R113") (pin "2") (pinfunction "2_2") (pintype "passive"))
      (node (ref "R114") (pin "2") (pinfunction "2_2") (pintype "passive"))
    )
    (net (code "31") (name "AO_7") (class "Default")
      (node (ref "C148") (pin "1") (pinfunction "1_1") (pintype "passive"))
      (node (ref "J7") (pin "66") (pinfunction "66_66") (pintype "passive"))
      (node (ref "R117") (pin "2") (pinfunction "2_2") (pintype "passive"))
      (node (ref "R118") (pin "2") (pinfunction "2_2") (pintype "passive"))
    )
    (net (code "32") (name "BSW_G") (class "Default")
      (node (ref "IC14") (pin "7") (pinfunction "BSW_7") (pintype "output"))
      (node (ref "T2") (pin "1") (pinfunction "G_1") (pintype "passive"))
      (node (ref "TP_BSW_G") (pin "TP") (pinfunction "P$1_TP") (pintype "bidirectional"))
    )
    (net (code "33") (name "BT_NDIS") (class "Default")
      (node (ref "J2") (pin "91") (pinfunction "91_91") (pintype "passive"))
      (node (ref "JP3") (pin "3") (pinfunction "3_3") (pintype "bidirectional"))
    )
    (net (code "34") (name "BUF") (class "Default")
      (node (ref "BUF") (pin "TP") (pinfunction "P$1_TP") (pintype "bidirectional"))
      (node (ref "C105") (pin "2") (pinfunction "2_2") (pintype "passive"))
      (node (ref "IC15") (pin "8") (pinfunction "BUF_8") (pintype "input"))
      (node (ref "R74") (pin "1") (pinfunction "1_1") (pintype "passive"))
    )
    (net (code "35") (name "CAM_GPIO0") (class "Default")
      (node (ref "J2") (pin "97") (pinfunction "97_97") (pintype "passive"))
      (node (ref "J3") (pin "17") (pinfunction "17_17") (pintype "passive"))
    )
    (net (code "36") (name "CAM_GPIO1") (class "Default")
      (node (ref "J2") (pin "100") (pinfunction "100_100") (pintype "passive"))
      (node (ref "J3") (pin "18") (pinfunction "18_18") (pintype "passive"))
    )
    (net (code "37") (name "CC1") (class "Default")
      (node (ref "J2") (pin "94") (pinfunction "94_94") (pintype "passive"))
      (node (ref "USBC") (pin "A5") (pinfunction "CC1_A5") (pintype "passive"))
    )
    (net (code "38") (name "CC2") (class "Default")
      (node (ref "J2") (pin "96") (pinfunction "96_96") (pintype "passive"))
      (node (ref "USBC") (pin "B5") (pinfunction "CC2_B5") (pintype "passive"))
    )
    (net (code "39") (name "DAC_0") (class "Default")
      (node (ref "IC22") (pin "4") (pinfunction "VOUT_A_4") (pintype "output"))
      (node (ref "IC24") (pin "3") (pinfunction "+IN_3") (pintype "input"))
      (node (ref "TPD0") (pin "TP") (pinfunction "P$1_TP") (pintype "bidirectional"))
    )
    (net (code "40") (name "DAC_1") (class "Default")
      (node (ref "IC22") (pin "13") (pinfunction "VOUT_B_13") (pintype "output"))
      (node (ref "IC25") (pin "3") (pinfunction "+IN_3") (pintype "input"))
    )
    (net (code "41") (name "DAC_2") (class "Default")
      (node (ref "IC22") (pin "5") (pinfunction "VOUT_C_5") (pintype "output"))
      (node (ref "IC26") (pin "3") (pinfunction "+IN_3") (pintype "input"))
    )
    (net (code "42") (name "DAC_3") (class "Default")
      (node (ref "IC22") (pin "12") (pinfunction "VOUT_D_12") (pintype "output"))
      (node (ref "IC27") (pin "3") (pinfunction "+IN_3") (pintype "input"))
    )
    (net (code "43") (name "DAC_4") (class "Default")
      (node (ref "IC22") (pin "6") (pinfunction "VOUT_E_6") (pintype "output"))
      (node (ref "IC28") (pin "3") (pinfunction "+IN_3") (pintype "input"))
    )
    (net (code "44") (name "DAC_5") (class "Default")
      (node (ref "IC22") (pin "11") (pinfunction "VOUT_F_11") (pintype "output"))
      (node (ref "IC29") (pin "3") (pinfunction "+IN_3") (pintype "input"))
    )
    (net (code "45") (name "DAC_6") (class "Default")
      (node (ref "IC22") (pin "7") (pinfunction "VOUT_G_7") (pintype "output"))
      (node (ref "IC30") (pin "3") (pinfunction "+IN_3") (pintype "input"))
    )
    (net (code "46") (name "DAC_7") (class "Default")
      (node (ref "IC22") (pin "10") (pinfunction "VOUT_H_10") (pintype "output"))
      (node (ref "IC31") (pin "3") (pinfunction "+IN_3") (pintype "input"))
    )
    (net (code "47") (name "DAC_~{CLR}") (class "Default")
      (node (ref "CLR") (pin "TP") (pinfunction "P$1_TP") (pintype "bidirectional"))
      (node (ref "IC22") (pin "9") (pinfunction "~{CLR}_9") (pintype "bidirectional"))
      (node (ref "R37") (pin "1") (pinfunction "1_1") (pintype "passive"))
      (node (ref "R86") (pin "4") (pinfunction "4_4") (pintype "passive"))
    )
    (net (code "48") (name "DAC_~{LDAC}") (class "Default")
      (node (ref "IC22") (pin "1") (pinfunction "~{LDAC}_1") (pintype "bidirectional"))
      (node (ref "LDAC") (pin "TP") (pinfunction "P$1_TP") (pintype "bidirectional"))
      (node (ref "R35") (pin "1") (pinfunction "1_1") (pintype "passive"))
      (node (ref "R86") (pin "2") (pinfunction "2_2") (pintype "passive"))
    )
    (net (code "49") (name "DAC_~{SYNC}") (class "Default")
      (node (ref "IC22") (pin "2") (pinfunction "~{SYNC}_2") (pintype "bidirectional"))
      (node (ref "R31") (pin "1") (pinfunction "1_1") (pintype "passive"))
      (node (ref "R86") (pin "3") (pinfunction "3_3") (pintype "passive"))
      (node (ref "SYNC") (pin "TP") (pinfunction "P$1_TP") (pintype "bidirectional"))
    )
    (net (code "50") (name "DIO_0") (class "Default")
      (node (ref "J7") (pin "2") (pinfunction "2_2") (pintype "passive"))
      (node (ref "R120") (pin "5") (pinfunction "5_5") (pintype "passive"))
    )
    (net (code "51") (name "DIO_1") (class "Default")
      (node (ref "J7") (pin "3") (pinfunction "3_3") (pintype "passive"))
      (node (ref "R120") (pin "6") (pinfunction "6_6") (pintype "passive"))
    )
    (net (code "52") (name "DIO_2") (class "Default")
      (node (ref "J7") (pin "4") (pinfunction "4_4") (pintype "passive"))
      (node (ref "R120") (pin "7") (pinfunction "7_7") (pintype "passive"))
    )
    (net (code "53") (name "DIO_3") (class "Default")
      (node (ref "J7") (pin "5") (pinfunction "5_5") (pintype "passive"))
      (node (ref "R120") (pin "8") (pinfunction "8_8") (pintype "passive"))
    )
    (net (code "54") (name "DIO_4") (class "Default")
      (node (ref "J7") (pin "6") (pinfunction "6_6") (pintype "passive"))
      (node (ref "R119") (pin "5") (pinfunction "5_5") (pintype "passive"))
    )
    (net (code "55") (name "DIO_5") (class "Default")
      (node (ref "J7") (pin "7") (pinfunction "7_7") (pintype "passive"))
      (node (ref "R119") (pin "6") (pinfunction "6_6") (pintype "passive"))
    )
    (net (code "56") (name "DIO_6") (class "Default")
      (node (ref "J7") (pin "8") (pinfunction "8_8") (pintype "passive"))
      (node (ref "R119") (pin "7") (pinfunction "7_7") (pintype "passive"))
    )
    (net (code "57") (name "DIO_7") (class "Default")
      (node (ref "J7") (pin "9") (pinfunction "9_9") (pintype "passive"))
      (node (ref "R119") (pin "8") (pinfunction "8_8") (pintype "passive"))
    )
    (net (code "58") (name "DIO_8") (class "Default")
      (node (ref "J7") (pin "10") (pinfunction "10_10") (pintype "passive"))
      (node (ref "R122") (pin "5") (pinfunction "5_5") (pintype "passive"))
    )
    (net (code "59") (name "DIO_9") (class "Default")
      (node (ref "J7") (pin "11") (pinfunction "11_11") (pintype "passive"))
      (node (ref "R122") (pin "6") (pinfunction "6_6") (pintype "passive"))
    )
    (net (code "60") (name "DIO_10") (class "Default")
      (node (ref "J7") (pin "12") (pinfunction "12_12") (pintype "passive"))
      (node (ref "R122") (pin "7") (pinfunction "7_7") (pintype "passive"))
    )
    (net (code "61") (name "DIO_11") (class "Default")
      (node (ref "J7") (pin "13") (pinfunction "13_13") (pintype "passive"))
      (node (ref "R122") (pin "8") (pinfunction "8_8") (pintype "passive"))
    )
    (net (code "62") (name "DIO_12") (class "Default")
      (node (ref "J7") (pin "14") (pinfunction "14_14") (pintype "passive"))
      (node (ref "R121") (pin "5") (pinfunction "5_5") (pintype "passive"))
    )
    (net (code "63") (name "DIO_13") (class "Default")
      (node (ref "J7") (pin "15") (pinfunction "15_15") (pintype "passive"))
      (node (ref "R121") (pin "6") (pinfunction "6_6") (pintype "passive"))
    )
    (net (code "64") (name "DIO_14") (class "Default")
      (node (ref "J7") (pin "16") (pinfunction "16_16") (pintype "passive"))
      (node (ref "R121") (pin "7") (pinfunction "7_7") (pintype "passive"))
    )
    (net (code "65") (name "DIO_15") (class "Default")
      (node (ref "J7") (pin "17") (pinfunction "17_17") (pintype "passive"))
      (node (ref "R121") (pin "8") (pinfunction "8_8") (pintype "passive"))
    )
    (net (code "66") (name "DIO_16") (class "Default")
      (node (ref "J7") (pin "36") (pinfunction "36_36") (pintype "passive"))
      (node (ref "R124") (pin "5") (pinfunction "5_5") (pintype "passive"))
    )
    (net (code "67") (name "DIO_17") (class "Default")
      (node (ref "J7") (pin "37") (pinfunction "37_37") (pintype "passive"))
      (node (ref "R124") (pin "6") (pinfunction "6_6") (pintype "passive"))
    )
    (net (code "68") (name "DIO_18") (class "Default")
      (node (ref "J7") (pin "38") (pinfunction "38_38") (pintype "passive"))
      (node (ref "R124") (pin "7") (pinfunction "7_7") (pintype "passive"))
    )
    (net (code "69") (name "DIO_19") (class "Default")
      (node (ref "J7") (pin "39") (pinfunction "39_39") (pintype "passive"))
      (node (ref "R124") (pin "8") (pinfunction "8_8") (pintype "passive"))
    )
    (net (code "70") (name "DIO_20") (class "Default")
      (node (ref "J7") (pin "40") (pinfunction "40_40") (pintype "passive"))
      (node (ref "R123") (pin "5") (pinfunction "5_5") (pintype "passive"))
    )
    (net (code "71") (name "DIO_21") (class "Default")
      (node (ref "J7") (pin "41") (pinfunction "41_41") (pintype "passive"))
      (node (ref "R123") (pin "6") (pinfunction "6_6") (pintype "passive"))
    )
    (net (code "72") (name "DIO_22") (class "Default")
      (node (ref "J7") (pin "42") (pinfunction "42_42") (pintype "passive"))
      (node (ref "R123") (pin "7") (pinfunction "7_7") (pintype "passive"))
    )
    (net (code "73") (name "DIO_23") (class "Default")
      (node (ref "J7") (pin "43") (pinfunction "43_43") (pintype "passive"))
      (node (ref "R123") (pin "8") (pinfunction "8_8") (pintype "passive"))
    )
    (net (code "74") (name "DIO_24") (class "Default")
      (node (ref "J7") (pin "44") (pinfunction "44_44") (pintype "passive"))
      (node (ref "R126") (pin "5") (pinfunction "5_5") (pintype "passive"))
    )
    (net (code "75") (name "DIO_25") (class "Default")
      (node (ref "J7") (pin "45") (pinfunction "45_45") (pintype "passive"))
      (node (ref "R126") (pin "6") (pinfunction "6_6") (pintype "passive"))
    )
    (net (code "76") (name "DIO_26") (class "Default")
      (node (ref "J7") (pin "46") (pinfunction "46_46") (pintype "passive"))
      (node (ref "R126") (pin "7") (pinfunction "7_7") (pintype "passive"))
    )
    (net (code "77") (name "DIO_27") (class "Default")
      (node (ref "J7") (pin "47") (pinfunction "47_47") (pintype "passive"))
      (node (ref "R126") (pin "8") (pinfunction "8_8") (pintype "passive"))
    )
    (net (code "78") (name "DIO_28") (class "Default")
      (node (ref "J7") (pin "48") (pinfunction "48_48") (pintype "passive"))
      (node (ref "R125") (pin "5") (pinfunction "5_5") (pintype "passive"))
    )
    (net (code "79") (name "DIO_29") (class "Default")
      (node (ref "J7") (pin "49") (pinfunction "49_49") (pintype "passive"))
      (node (ref "R125") (pin "6") (pinfunction "6_6") (pintype "passive"))
    )
    (net (code "80") (name "DIO_30") (class "Default")
      (node (ref "J7") (pin "50") (pinfunction "50_50") (pintype "passive"))
      (node (ref "R125") (pin "7") (pinfunction "7_7") (pintype "passive"))
    )
    (net (code "81") (name "DIO_31") (class "Default")
      (node (ref "J7") (pin "51") (pinfunction "51_51") (pintype "passive"))
      (node (ref "R125") (pin "8") (pinfunction "8_8") (pintype "passive"))
    )
    (net (code "82") (name "DIO_EN") (class "Default")
      (node (ref "DIO_EN") (pin "TP") (pinfunction "P$1_TP") (pintype "bidirectional"))
      (node (ref "IC32") (pin "20") (pinfunction "EN_20") (pintype "bidirectional"))
      (node (ref "IC33") (pin "20") (pinfunction "EN_20") (pintype "bidirectional"))
      (node (ref "IC34") (pin "20") (pinfunction "EN_20") (pintype "bidirectional"))
      (node (ref "IC35") (pin "20") (pinfunction "EN_20") (pintype "bidirectional"))
      (node (ref "R41") (pin "1") (pinfunction "1_1") (pintype "passive"))
    )
    (net (code "83") (name "DIO_LEVEL_SELECT") (class "Default")
      (node (ref "DIO_LS") (pin "TP") (pinfunction "P$1_TP") (pintype "bidirectional"))
      (node (ref "IC38") (pin "7") (pinfunction "1C_7") (pintype "input"))
      (node (ref "IC39") (pin "2") (pinfunction "IN_2") (pintype "bidirectional"))
      (node (ref "R40") (pin "1") (pinfunction "1_1") (pintype "passive"))
    )
    (net (code "84") (name "DIO_RESET") (class "Default")
      (node (ref "DIO_RST") (pin "TP") (pinfunction "P$1_TP") (pintype "bidirectional"))
      (node (ref "IC36") (pin "13") (pinfunction "~{RESET}_13") (pintype "input"))
      (node (ref "IC37") (pin "13") (pinfunction "~{RESET}_13") (pintype "input"))
      (node (ref "R39") (pin "1") (pinfunction "1_1") (pintype "passive"))
    )
    (net (code "85") (name "DPHY0_C_N") (class "Default")
      (node (ref "J1") (pin "27") (pinfunction "27_27") (pintype "passive"))
      (node (ref "J3") (pin "8") (pinfunction "8_8") (pintype "passive"))
    )
    (net (code "86") (name "DPHY0_C_P") (class "Default")
      (node (ref "J1") (pin "29") (pinfunction "29_29") (pintype "passive"))
      (node (ref "J3") (pin "9") (pinfunction "9_9") (pintype "passive"))
    )
    (net (code "87") (name "DPHY0_D0_N") (class "Default")
      (node (ref "J1") (pin "15") (pinfunction "15_15") (pintype "passive"))
      (node (ref "J3") (pin "2") (pinfunction "2_2") (pintype "passive"))
    )
    (net (code "88") (name "DPHY0_D0_P") (class "Default")
      (node (ref "J1") (pin "17") (pinfunction "17_17") (pintype "passive"))
      (node (ref "J3") (pin "3") (pinfunction "3_3") (pintype "passive"))
    )
    (net (code "89") (name "DPHY0_D1_N") (class "Default")
      (node (ref "J1") (pin "21") (pinfunction "21_21") (pintype "passive"))
      (node (ref "J3") (pin "5") (pinfunction "5_5") (pintype "passive"))
    )
    (net (code "90") (name "DPHY0_D1_P") (class "Default")
      (node (ref "J1") (pin "23") (pinfunction "23_23") (pintype "passive"))
      (node (ref "J3") (pin "6") (pinfunction "6_6") (pintype "passive"))
    )
    (net (code "91") (name "DPHY0_D2_N") (class "Default")
      (node (ref "J1") (pin "33") (pinfunction "33_33") (pintype "passive"))
      (node (ref "J3") (pin "11") (pinfunction "11_11") (pintype "passive"))
    )
    (net (code "92") (name "DPHY0_D2_P") (class "Default")
      (node (ref "J1") (pin "35") (pinfunction "35_35") (pintype "passive"))
      (node (ref "J3") (pin "12") (pinfunction "12_12") (pintype "passive"))
    )
    (net (code "93") (name "DPHY0_D3_N") (class "Default")
      (node (ref "J1") (pin "39") (pinfunction "39_39") (pintype "passive"))
      (node (ref "J3") (pin "14") (pinfunction "14_14") (pintype "passive"))
    )
    (net (code "94") (name "DPHY0_D3_P") (class "Default")
      (node (ref "J1") (pin "41") (pinfunction "41_41") (pintype "passive"))
      (node (ref "J3") (pin "15") (pinfunction "15_15") (pintype "passive"))
    )
    (net (code "95") (name "DPHY1_C_N") (class "Default")
      (node (ref "J1") (pin "87") (pinfunction "87_87") (pintype "passive"))
      (node (ref "J4") (pin "8") (pinfunction "8_8") (pintype "passive"))
    )
    (net (code "96") (name "DPHY1_C_P") (class "Default")
      (node (ref "J1") (pin "89") (pinfunction "89_89") (pintype "passive"))
      (node (ref "J4") (pin "9") (pinfunction "9_9") (pintype "passive"))
    )
    (net (code "97") (name "DPHY1_D0_N") (class "Default")
      (node (ref "J1") (pin "75") (pinfunction "75_75") (pintype "passive"))
      (node (ref "J4") (pin "2") (pinfunction "2_2") (pintype "passive"))
    )
    (net (code "98") (name "DPHY1_D0_P") (class "Default")
      (node (ref "J1") (pin "77") (pinfunction "77_77") (pintype "passive"))
      (node (ref "J4") (pin "3") (pinfunction "3_3") (pintype "passive"))
    )
    (net (code "99") (name "DPHY1_D1_N") (class "Default")
      (node (ref "J1") (pin "81") (pinfunction "81_81") (pintype "passive"))
      (node (ref "J4") (pin "5") (pinfunction "5_5") (pintype "passive"))
    )
    (net (code "100") (name "DPHY1_D1_P") (class "Default")
      (node (ref "J1") (pin "83") (pinfunction "83_83") (pintype "passive"))
      (node (ref "J4") (pin "6") (pinfunction "6_6") (pintype "passive"))
    )
    (net (code "101") (name "DPHY1_D2_N") (class "Default")
      (node (ref "J1") (pin "93") (pinfunction "93_93") (pintype "passive"))
      (node (ref "J4") (pin "11") (pinfunction "11_11") (pintype "passive"))
    )
    (net (code "102") (name "DPHY1_D2_P") (class "Default")
      (node (ref "J1") (pin "95") (pinfunction "95_95") (pintype "passive"))
      (node (ref "J4") (pin "12") (pinfunction "12_12") (pintype "passive"))
    )
    (net (code "103") (name "DPHY1_D3_N") (class "Default")
      (node (ref "J1") (pin "94") (pinfunction "94_94") (pintype "passive"))
      (node (ref "J4") (pin "14") (pinfunction "14_14") (pintype "passive"))
    )
    (net (code "104") (name "DPHY1_D3_P") (class "Default")
      (node (ref "J1") (pin "96") (pinfunction "96_96") (pintype "passive"))
      (node (ref "J4") (pin "15") (pinfunction "15_15") (pintype "passive"))
    )
    (net (code "105") (name "EEPROM_NWP") (class "Default")
      (node (ref "J2") (pin "20") (pinfunction "20_20") (pintype "passive"))
      (node (ref "JP2") (pin "4") (pinfunction "4_4") (pintype "bidirectional"))
    )
    (net (code "106") (name "ETH_LEDG") (class "Default")
      (node (ref "J2") (pin "17") (pinfunction "17_17") (pintype "passive"))
      (node (ref "R8") (pin "1") (pinfunction "1_1") (pintype "passive"))
    )
    (net (code "107") (name "ETH_LEDY") (class "Default")
      (node (ref "J2") (pin "15") (pinfunction "15_15") (pintype "passive"))
      (node (ref "R9") (pin "2") (pinfunction "2_2") (pintype "passive"))
    )
    (net (code "108") (name "GND") (class "Default")
      (node (ref "2230") (pin "1") (pinfunction "1_1") (pintype "passive"))
      (node (ref "2242") (pin "1") (pinfunction "1_1") (pintype "passive"))
      (node (ref "2260") (pin "1") (pinfunction "1_1") (pintype "passive"))
      (node (ref "2280") (pin "1") (pinfunction "1_1") (pintype "passive"))
      (node (ref "BT1") (pin "N") (pinfunction "-_N") (pintype "passive"))
      (node (ref "C1") (pin "2") (pinfunction "2_2") (pintype "passive"))
      (node (ref "C10") (pin "2") (pinfunction "2_2") (pintype "passive"))
      (node (ref "C102") (pin "2") (pinfunction "2_2") (pintype "passive"))
      (node (ref "C103") (pin "2") (pinfunction "2_2") (pintype "passive"))
      (node (ref "C104") (pin "2") (pinfunction "2_2") (pintype "passive"))
      (node (ref "C105") (pin "1") (pinfunction "1_1") (pintype "passive"))
      (node (ref "C108") (pin "2") (pinfunction "2_2") (pintype "passive"))
      (node (ref "C109") (pin "2") (pinfunction "2_2") (pintype "passive"))
      (node (ref "C11") (pin "2") (pinfunction "2_2") (pintype "passive"))
      (node (ref "C111") (pin "2") (pinfunction "2_2") (pintype "passive"))
      (node (ref "C12") (pin "2") (pinfunction "2_2") (pintype "passive"))
      (node (ref "C120") (pin "2") (pinfunction "2_2") (pintype "passive"))
      (node (ref "C121") (pin "2") (pinfunction "2_2") (pintype "passive"))
      (node (ref "C122") (pin "2") (pinfunction "2_2") (pintype "passive"))
      (node (ref "C123") (pin "2") (pinfunction "2_2") (pintype "passive"))
      (node (ref "C124") (pin "2") (pinfunction "2_2") (pintype "passive"))
      (node (ref "C125") (pin "2") (pinfunction "2_2") (pintype "passive"))
      (node (ref "C126") (pin "2") (pinfunction "2_2") (pintype "passive"))
      (node (ref "C127") (pin "2") (pinfunction "2_2") (pintype "passive"))
      (node (ref "C128") (pin "2") (pinfunction "2_2") (pintype "passive"))
      (node (ref "C130") (pin "2") (pinfunction "2_2") (pintype "passive"))
      (node (ref "C131") (pin "2") (pinfunction "2_2") (pintype "passive"))
      (node (ref "C133") (pin "2") (pinfunction "2_2") (pintype "passive"))
      (node (ref "C134") (pin "2") (pinfunction "2_2") (pintype "passive"))
      (node (ref "C136") (pin "2") (pinfunction "2_2") (pintype "passive"))
      (node (ref "C137") (pin "2") (pinfunction "2_2") (pintype "passive"))
      (node (ref "C139") (pin "2") (pinfunction "2_2") (pintype "passive"))
      (node (ref "C14") (pin "2") (pinfunction "2_2") (pintype "passive"))
      (node (ref "C140") (pin "2") (pinfunction "2_2") (pintype "passive"))
      (node (ref "C142") (pin "2") (pinfunction "2_2") (pintype "passive"))
      (node (ref "C143") (pin "2") (pinfunction "2_2") (pintype "passive"))
      (node (ref "C145") (pin "2") (pinfunction "2_2") (pintype "passive"))
      (node (ref "C146") (pin "2") (pinfunction "2_2") (pintype "passive"))
      (node (ref "C148") (pin "2") (pinfunction "2_2") (pintype "passive"))
      (node (ref "C149") (pin "2") (pinfunction "2_2") (pintype "passive"))
      (node (ref "C15") (pin "2") (pinfunction "2_2") (pintype "passive"))
      (node (ref "C151") (pin "2") (pinfunction "2_2") (pintype "passive"))
      (node (ref "C152") (pin "2") (pinfunction "2_2") (pintype "passive"))
      (node (ref "C153") (pin "2") (pinfunction "2_2") (pintype "passive"))
      (node (ref "C154") (pin "2") (pinfunction "2_2") (pintype "passive"))
      (node (ref "C155") (pin "2") (pinfunction "2_2") (pintype "passive"))
      (node (ref "C156") (pin "2") (pinfunction "2_2") (pintype "passive"))
      (node (ref "C157") (pin "2") (pinfunction "2_2") (pintype "passive"))
      (node (ref "C158") (pin "2") (pinfunction "2_2") (pintype "passive"))
      (node (ref "C159") (pin "2") (pinfunction "2_2") (pintype "passive"))
      (node (ref "C16") (pin "2") (pinfunction "2_2") (pintype "passive"))
      (node (ref "C160") (pin "2") (pinfunction "2_2") (pintype "passive"))
      (node (ref "C161") (pin "2") (pinfunction "2_2") (pintype "passive"))
      (node (ref "C162") (pin "2") (pinfunction "2_2") (pintype "passive"))
      (node (ref "C163") (pin "2") (pinfunction "2_2") (pintype "passive"))
      (node (ref "C164") (pin "2") (pinfunction "2_2") (pintype "passive"))
      (node (ref "C165") (pin "2") (pinfunction "2_2") (pintype "passive"))
      (node (ref "C166") (pin "2") (pinfunction "2_2") (pintype "passive"))
      (node (ref "C167") (pin "2") (pinfunction "2_2") (pintype "passive"))
      (node (ref "C168") (pin "2") (pinfunction "2_2") (pintype "passive"))
      (node (ref "C169") (pin "2") (pinfunction "2_2") (pintype "passive"))
      (node (ref "C17") (pin "2") (pinfunction "2_2") (pintype "passive"))
      (node (ref "C170") (pin "2") (pinfunction "2_2") (pintype "passive"))
      (node (ref "C171") (pin "2") (pinfunction "2_2") (pintype "passive"))
      (node (ref "C18") (pin "2") (pinfunction "2_2") (pintype "passive"))
      (node (ref "C19") (pin "2") (pinfunction "2_2") (pintype "passive"))
      (node (ref "C2") (pin "2") (pinfunction "2_2") (pintype "passive"))
      (node (ref "C20") (pin "2") (pinfunction "2_2") (pintype "passive"))
      (node (ref "C21") (pin "2") (pinfunction "2_2") (pintype "passive"))
      (node (ref "C22") (pin "2") (pinfunction "2_2") (pintype "passive"))
      (node (ref "C23") (pin "2") (pinfunction "2_2") (pintype "passive"))
      (node (ref "C24") (pin "1") (pinfunction "1_1") (pintype "passive"))
      (node (ref "C25") (pin "2") (pinfunction "2_2") (pintype "passive"))
      (node (ref "C26") (pin "2") (pinfunction "2_2") (pintype "passive"))
      (node (ref "C27") (pin "2") (pinfunction "2_2") (pintype "passive"))
      (node (ref "C3") (pin "2") (pinfunction "2_2") (pintype "passive"))
      (node (ref "C4") (pin "2") (pinfunction "2_2") (pintype "passive"))
      (node (ref "C42") (pin "2") (pinfunction "2_2") (pintype "passive"))
      (node (ref "C43") (pin "1") (pinfunction "1_1") (pintype "passive"))
      (node (ref "C45") (pin "2") (pinfunction "2_2") (pintype "passive"))
      (node (ref "C46") (pin "2") (pinfunction "2_2") (pintype "passive"))
      (node (ref "C47") (pin "2") (pinfunction "2_2") (pintype "passive"))
      (node (ref "C48") (pin "2") (pinfunction "2_2") (pintype "passive"))
      (node (ref "C49") (pin "2") (pinfunction "2_2") (pintype "passive"))
      (node (ref "C5") (pin "2") (pinfunction "2_2") (pintype "passive"))
      (node (ref "C50") (pin "2") (pinfunction "2_2") (pintype "passive"))
      (node (ref "C51") (pin "2") (pinfunction "2_2") (pintype "passive"))
      (node (ref "C52") (pin "2") (pinfunction "2_2") (pintype "passive"))
      (node (ref "C53") (pin "2") (pinfunction "2_2") (pintype "passive"))
      (node (ref "C54") (pin "2") (pinfunction "2_2") (pintype "passive"))
      (node (ref "C55") (pin "2") (pinfunction "2_2") (pintype "passive"))
      (node (ref "C56") (pin "2") (pinfunction "2_2") (pintype "passive"))
      (node (ref "C57") (pin "2") (pinfunction "2_2") (pintype "passive"))
      (node (ref "C58") (pin "2") (pinfunction "2_2") (pintype "passive"))
      (node (ref "C59") (pin "2") (pinfunction "2_2") (pintype "passive"))
      (node (ref "C6") (pin "2") (pinfunction "2_2") (pintype "passive"))
      (node (ref "C60") (pin "2") (pinfunction "2_2") (pintype "passive"))
      (node (ref "C61") (pin "2") (pinfunction "2_2") (pintype "passive"))
      (node (ref "C62") (pin "2") (pinfunction "2_2") (pintype "passive"))
      (node (ref "C63") (pin "2") (pinfunction "2_2") (pintype "passive"))
      (node (ref "C64") (pin "2") (pinfunction "2_2") (pintype "passive"))
      (node (ref "C65") (pin "2") (pinfunction "2_2") (pintype "passive"))
      (node (ref "C66") (pin "2") (pinfunction "2_2") (pintype "passive"))
      (node (ref "C67") (pin "2") (pinfunction "2_2") (pintype "passive"))
      (node (ref "C68") (pin "2") (pinfunction "2_2") (pintype "passive"))
      (node (ref "C69") (pin "2") (pinfunction "2_2") (pintype "passive"))
      (node (ref "C7") (pin "2") (pinfunction "2_2") (pintype "passive"))
      (node (ref "C71") (pin "2") (pinfunction "2_2") (pintype "passive"))
      (node (ref "C74") (pin "2") (pinfunction "2_2") (pintype "passive"))
      (node (ref "C75") (pin "2") (pinfunction "2_2") (pintype "passive"))
      (node (ref "C76") (pin "2") (pinfunction "2_2") (pintype "passive"))
      (node (ref "C8") (pin "2") (pinfunction "2_2") (pintype "passive"))
      (node (ref "C85") (pin "2") (pinfunction "2_2") (pintype "passive"))
      (node (ref "C86") (pin "2") (pinfunction "2_2") (pintype "passive"))
      (node (ref "C9") (pin "2") (pinfunction "2_2") (pintype "passive"))
      (node (ref "C90") (pin "2") (pinfunction "2_2") (pintype "passive"))
      (node (ref "C91") (pin "2") (pinfunction "2_2") (pintype "passive"))
      (node (ref "C92") (pin "2") (pinfunction "2_2") (pintype "passive"))
      (node (ref "C93") (pin "2") (pinfunction "2_2") (pintype "passive"))
      (node (ref "C94") (pin "2") (pinfunction "2_2") (pintype "passive"))
      (node (ref "C95") (pin "2") (pinfunction "2_2") (pintype "passive"))
      (node (ref "C96") (pin "2") (pinfunction "2_2") (pintype "passive"))
      (node (ref "C97") (pin "2") (pinfunction "2_2") (pintype "passive"))
      (node (ref "C98") (pin "2") (pinfunction "2_2") (pintype "passive"))
      (node (ref "C99") (pin "1") (pinfunction "1_1") (pintype "passive"))
      (node (ref "CON1") (pin "2") (pinfunction "P$2_2") (pintype "bidirectional"))
      (node (ref "D1") (pin "3") (pinfunction "GND_3") (pintype "bidirectional"))
      (node (ref "D1") (pin "8") (pinfunction "GND_8") (pintype "bidirectional"))
      (node (ref "D2") (pin "3") (pinfunction "GND_3") (pintype "bidirectional"))
      (node (ref "D2") (pin "8") (pinfunction "GND_8") (pintype "bidirectional"))
      (node (ref "DIO_GND") (pin "TP") (pinfunction "P$1_TP") (pintype "bidirectional"))
      (node (ref "ETH1") (pin "MH3") (pinfunction "SHIELD_MH3") (pintype "bidirectional"))
      (node (ref "ETH1") (pin "MH4") (pinfunction "SHIELD_MH4") (pintype "bidirectional"))
      (node (ref "GPIO") (pin "14") (pinfunction "14_14") (pintype "bidirectional"))
      (node (ref "GPIO") (pin "20") (pinfunction "20_20") (pintype "bidirectional"))
      (node (ref "GPIO") (pin "25") (pinfunction "25_25") (pintype "bidirectional"))
      (node (ref "GPIO") (pin "30") (pinfunction "30_30") (pintype "bidirectional"))
      (node (ref "GPIO") (pin "34") (pinfunction "34_34") (pintype "bidirectional"))
      (node (ref "GPIO") (pin "39") (pinfunction "39_39") (pintype "bidirectional"))
      (node (ref "GPIO") (pin "6") (pinfunction "6_6") (pintype "bidirectional"))
      (node (ref "GPIO") (pin "9") (pinfunction "9_9") (pintype "bidirectional"))
      (node (ref "HDMI1") (pin "11") (pinfunction "TMDSCLOCK+_11") (pintype "passive"))
      (node (ref "HDMI1") (pin "17") (pinfunction "UTILITY/HEAC+_17") (pintype "passive"))
      (node (ref "HDMI1") (pin "2") (pinfunction "TMDS2+_2") (pintype "passive"))
      (node (ref "HDMI1") (pin "5") (pinfunction "TMDSDATA1+_5") (pintype "passive"))
      (node (ref "HDMI1") (pin "8") (pinfunction "TMDS0+_8") (pintype "passive"))
      (node (ref "HDMI1") (pin "S1") (pinfunction "SHIELD_S1") (pintype "passive"))
      (node (ref "HDMI1") (pin "S2") (pinfunction "SHIELD_S2") (pintype "passive"))
      (node (ref "HDMI1") (pin "S3") (pinfunction "SHIELD_S3") (pintype "passive"))
      (node (ref "HDMI1") (pin "S4") (pinfunction "SHIELD_S4") (pintype "passive"))
      (node (ref "HDMI2") (pin "11") (pinfunction "TMDSCLOCK+_11") (pintype "passive"))
      (node (ref "HDMI2") (pin "17") (pinfunction "UTILITY/HEAC+_17") (pintype "passive"))
      (node (ref "HDMI2") (pin "2") (pinfunction "TMDS2+_2") (pintype "passive"))
      (node (ref "HDMI2") (pin "5") (pinfunction "TMDSDATA1+_5") (pintype "passive"))
      (node (ref "HDMI2") (pin "8") (pinfunction "TMDS0+_8") (pintype "passive"))
      (node (ref "HDMI2") (pin "S1") (pinfunction "SHIELD_S1") (pintype "passive"))
      (node (ref "HDMI2") (pin "S2") (pinfunction "SHIELD_S2") (pintype "passive"))
      (node (ref "HDMI2") (pin "S3") (pinfunction "SHIELD_S3") (pintype "passive"))
      (node (ref "HDMI2") (pin "S4") (pinfunction "SHIELD_S4") (pintype "passive"))
      (node (ref "IC1") (pin "2") (pinfunction "GND_2") (pintype "power_in"))
      (node (ref "IC10") (pin "11") (pinfunction "GND_11") (pintype "power_in"))
      (node (ref "IC10") (pin "27") (pinfunction "GND_27") (pintype "power_in"))
      (node (ref "IC10") (pin "30") (pinfunction "GND_30") (pintype "power_in"))
      (node (ref "IC10") (pin "33") (pinfunction "PAD_33") (pintype "power_in"))
      (node (ref "IC10") (pin "4") (pinfunction "GND_4") (pintype "power_in"))
      (node (ref "IC11") (pin "5") (pinfunction "V-_5") (pintype "power_in"))
      (node (ref "IC12") (pin "3") (pinfunction "GND_3") (pintype "bidirectional"))
      (node (ref "IC13") (pin "5") (pinfunction "V-_5") (pintype "power_in"))
      (node (ref "IC14") (pin "19") (pinfunction "AGND_19") (pintype "power_in"))
      (node (ref "IC14") (pin "2") (pinfunction "PGND_2") (pintype "power_in"))
      (node (ref "IC14") (pin "25") (pinfunction "PGND_25") (pintype "power_in"))
      (node (ref "IC14") (pin "3") (pinfunction "PGND_3") (pintype "power_in"))
      (node (ref "IC15") (pin "4") (pinfunction "GND_4") (pintype "power_in"))
      (node (ref "IC15") (pin "PAD") (pinfunction "PAD_PAD") (pintype "power_in"))
      (node (ref "IC15") (pin "PAD1") (pinfunction "PAD_PAD1") (pintype "power_in"))
      (node (ref "IC15") (pin "PAD2") (pinfunction "PAD_PAD2") (pintype "power_in"))
      (node (ref "IC15") (pin "PAD3") (pinfunction "PAD_PAD3") (pintype "power_in"))
      (node (ref "IC15") (pin "PAD4") (pinfunction "PAD_PAD4") (pintype "power_in"))
      (node (ref "IC16") (pin "4") (pinfunction "GND_4") (pintype "power_in"))
      (node (ref "IC17") (pin "3") (pinfunction "V-_3") (pintype "bidirectional"))
      (node (ref "IC18") (pin "1") (pinfunction "GND_1") (pintype "power_in"))
      (node (ref "IC2") (pin "2") (pinfunction "GND_2") (pintype "bidirectional"))
      (node (ref "IC22") (pin "14") (pinfunction "GND_14") (pintype "power_in"))
      (node (ref "IC23") (pin "5") (pinfunction "V-_5") (pintype "power_in"))
      (node (ref "IC24") (pin "5") (pinfunction "V-_5") (pintype "power_in"))
      (node (ref "IC25") (pin "5") (pinfunction "V-_5") (pintype "power_in"))
      (node (ref "IC26") (pin "5") (pinfunction "V-_5") (pintype "power_in"))
      (node (ref "IC27") (pin "5") (pinfunction "V-_5") (pintype "power_in"))
      (node (ref "IC28") (pin "5") (pinfunction "V-_5") (pintype "power_in"))
      (node (ref "IC29") (pin "5") (pinfunction "V-_5") (pintype "power_in"))
      (node (ref "IC3") (pin "3") (pinfunction "GND_3") (pintype "bidirectional"))
      (node (ref "IC30") (pin "5") (pinfunction "V-_5") (pintype "power_in"))
      (node (ref "IC31") (pin "5") (pinfunction "V-_5") (pintype "power_in"))
      (node (ref "IC32") (pin "1") (pinfunction "GND_1") (pintype "power_in"))
      (node (ref "IC32") (pin "PAD") (pinfunction "GND_PAD") (pintype "power_in"))
      (node (ref "IC33") (pin "1") (pinfunction "GND_1") (pintype "power_in"))
      (node (ref "IC33") (pin "PAD") (pinfunction "GND_PAD") (pintype "power_in"))
      (node (ref "IC34") (pin "1") (pinfunction "GND_1") (pintype "power_in"))
      (node (ref "IC34") (pin "PAD") (pinfunction "GND_PAD") (pintype "power_in"))
      (node (ref "IC35") (pin "1") (pinfunction "GND_1") (pintype "power_in"))
      (node (ref "IC35") (pin "PAD") (pinfunction "GND_PAD") (pintype "power_in"))
      (node (ref "IC36") (pin "23") (pinfunction "VSS_23") (pintype "power_in"))
      (node (ref "IC36") (pin "25") (pinfunction "VSS_25") (pintype "power_in"))
      (node (ref "IC37") (pin "23") (pinfunction "VSS_23") (pintype "power_in"))
      (node (ref "IC37") (pin "25") (pinfunction "VSS_25") (pintype "power_in"))
      (node (ref "IC38") (pin "4") (pinfunction "GND_4") (pintype "power_in"))
      (node (ref "IC39") (pin "3") (pinfunction "V-_3") (pintype "bidirectional"))
      (node (ref "IC4") (pin "3") (pinfunction "GND_3") (pintype "power_in"))
      (node (ref "IC5") (pin "4") (pinfunction "PGND_4") (pintype "power_in"))
      (node (ref "IC5") (pin "8") (pinfunction "SGND_8") (pintype "power_in"))
      (node (ref "IC5") (pin "9") (pinfunction "PGND_9") (pintype "power_in"))
      (node (ref "IC6") (pin "15") (pinfunction "GND_15") (pintype "power_in"))
      (node (ref "IC7") (pin "22") (pinfunction "AVSS_22") (pintype "power_in"))
      (node (ref "IC7") (pin "24") (pinfunction "IOUT_LV_24") (pintype "output"))
      (node (ref "IC7") (pin "25") (pinfunction "IOUT_HV_25") (pintype "output"))
      (node (ref "IC7") (pin "4") (pinfunction "IN2-_4") (pintype "input"))
      (node (ref "IC7") (pin "6") (pinfunction "DVSS_6") (pintype "power_in"))
      (node (ref "IC8") (pin "15") (pinfunction "GND_15") (pintype "power_in"))
      (node (ref "IC9") (pin "22") (pinfunction "AVSS_22") (pintype "power_in"))
      (node (ref "IC9") (pin "24") (pinfunction "IOUT_LV_24") (pintype "output"))
      (node (ref "IC9") (pin "25") (pinfunction "IOUT_HV_25") (pintype "output"))
      (node (ref "IC9") (pin "4") (pinfunction "IN2-_4") (pintype "input"))
      (node (ref "IC9") (pin "6") (pinfunction "DVSS_6") (pintype "power_in"))
      (node (ref "J1") (pin "13") (pinfunction "13_13") (pintype "passive"))
      (node (ref "J1") (pin "14") (pinfunction "14_14") (pintype "passive"))
      (node (ref "J1") (pin "19") (pinfunction "19_19") (pintype "passive"))
      (node (ref "J1") (pin "20") (pinfunction "20_20") (pintype "passive"))
      (node (ref "J1") (pin "25") (pinfunction "25_25") (pintype "passive"))
      (node (ref "J1") (pin "26") (pinfunction "26_26") (pintype "passive"))
      (node (ref "J1") (pin "31") (pinfunction "31_31") (pintype "passive"))
      (node (ref "J1") (pin "32") (pinfunction "32_32") (pintype "passive"))
      (node (ref "J1") (pin "37") (pinfunction "37_37") (pintype "passive"))
      (node (ref "J1") (pin "38") (pinfunction "38_38") (pintype "passive"))
      (node (ref "J1") (pin "44") (pinfunction "44_44") (pintype "passive"))
      (node (ref "J1") (pin "50") (pinfunction "50_50") (pintype "passive"))
      (node (ref "J1") (pin "55") (pinfunction "55_55") (pintype "passive"))
      (node (ref "J1") (pin "56") (pinfunction "56_56") (pintype "passive"))
      (node (ref "J1") (pin "61") (pinfunction "61_61") (pintype "passive"))
      (node (ref "J1") (pin "62") (pinfunction "62_62") (pintype "passive"))
      (node (ref "J1") (pin "67") (pinfunction "67_67") (pintype "passive"))
      (node (ref "J1") (pin "68") (pinfunction "68_68") (pintype "passive"))
      (node (ref "J1") (pin "7") (pinfunction "7_7") (pintype "passive"))
      (node (ref "J1") (pin "73") (pinfunction "73_73") (pintype "passive"))
      (node (ref "J1") (pin "74") (pinfunction "74_74") (pintype "passive"))
      (node (ref "J1") (pin "79") (pinfunction "79_79") (pintype "passive"))
      (node (ref "J1") (pin "8") (pinfunction "8_8") (pintype "passive"))
      (node (ref "J1") (pin "80") (pinfunction "80_80") (pintype "passive"))
      (node (ref "J1") (pin "85") (pinfunction "85_85") (pintype "passive"))
      (node (ref "J1") (pin "86") (pinfunction "86_86") (pintype "passive"))
      (node (ref "J1") (pin "91") (pinfunction "91_91") (pintype "passive"))
      (node (ref "J1") (pin "92") (pinfunction "92_92") (pintype "passive"))
      (node (ref "J1") (pin "97") (pinfunction "97_97") (pintype "passive"))
      (node (ref "J1") (pin "98") (pinfunction "98_98") (pintype "passive"))
      (node (ref "J2") (pin "1") (pinfunction "1_1") (pintype "passive"))
      (node (ref "J2") (pin "13") (pinfunction "13_13") (pintype "passive"))
      (node (ref "J2") (pin "14") (pinfunction "14_14") (pintype "passive"))
      (node (ref "J2") (pin "2") (pinfunction "2_2") (pintype "passive"))
      (node (ref "J2") (pin "22") (pinfunction "22_22") (pintype "passive"))
      (node (ref "J2") (pin "23") (pinfunction "23_23") (pintype "passive"))
      (node (ref "J2") (pin "32") (pinfunction "32_32") (pintype "passive"))
      (node (ref "J2") (pin "33") (pinfunction "33_33") (pintype "passive"))
      (node (ref "J2") (pin "42") (pinfunction "42_42") (pintype "passive"))
      (node (ref "J2") (pin "43") (pinfunction "43_43") (pintype "passive"))
      (node (ref "J2") (pin "52") (pinfunction "52_52") (pintype "passive"))
      (node (ref "J2") (pin "53") (pinfunction "53_53") (pintype "passive"))
      (node (ref "J2") (pin "59") (pinfunction "59_59") (pintype "passive"))
      (node (ref "J2") (pin "60") (pinfunction "60_60") (pintype "passive"))
      (node (ref "J2") (pin "65") (pinfunction "65_65") (pintype "passive"))
      (node (ref "J2") (pin "66") (pinfunction "66_66") (pintype "passive"))
      (node (ref "J2") (pin "7") (pinfunction "7_7") (pintype "passive"))
      (node (ref "J2") (pin "71") (pinfunction "71_71") (pintype "passive"))
      (node (ref "J2") (pin "74") (pinfunction "74_74") (pintype "passive"))
      (node (ref "J2") (pin "8") (pinfunction "8_8") (pintype "passive"))
      (node (ref "J2") (pin "98") (pinfunction "98_98") (pintype "passive"))
      (node (ref "J3") (pin "1") (pinfunction "1_1") (pintype "passive"))
      (node (ref "J3") (pin "10") (pinfunction "10_10") (pintype "passive"))
      (node (ref "J3") (pin "13") (pinfunction "13_13") (pintype "passive"))
      (node (ref "J3") (pin "16") (pinfunction "16_16") (pintype "passive"))
      (node (ref "J3") (pin "19") (pinfunction "19_19") (pintype "passive"))
      (node (ref "J3") (pin "23") (pinfunction "MH1_23") (pintype "passive"))
      (node (ref "J3") (pin "24") (pinfunction "MH2_24") (pintype "passive"))
      (node (ref "J3") (pin "25") (pinfunction "MH1_25") (pintype "passive"))
      (node (ref "J3") (pin "26") (pinfunction "MH2_26") (pintype "passive"))
      (node (ref "J3") (pin "4") (pinfunction "4_4") (pintype "passive"))
      (node (ref "J3") (pin "7") (pinfunction "7_7") (pintype "passive"))
      (node (ref "J4") (pin "1") (pinfunction "1_1") (pintype "passive"))
      (node (ref "J4") (pin "10") (pinfunction "10_10") (pintype "passive"))
      (node (ref "J4") (pin "13") (pinfunction "13_13") (pintype "passive"))
      (node (ref "J4") (pin "16") (pinfunction "16_16") (pintype "passive"))
      (node (ref "J4") (pin "19") (pinfunction "19_19") (pintype "passive"))
      (node (ref "J4") (pin "23") (pinfunction "MH1_23") (pintype "passive"))
      (node (ref "J4") (pin "24") (pinfunction "MH2_24") (pintype "passive"))
      (node (ref "J4") (pin "4") (pinfunction "4_4") (pintype "passive"))
      (node (ref "J4") (pin "7") (pinfunction "7_7") (pintype "passive"))
      (node (ref "J7") (pin "1") (pinfunction "1_1") (pintype "passive"))
      (node (ref "J7") (pin "23") (pinfunction "23_23") (pintype "passive"))
      (node (ref "J7") (pin "28") (pinfunction "28_28") (pintype "passive"))
      (node (ref "J7") (pin "34") (pinfunction "34_34") (pintype "passive"))
      (node (ref "J7") (pin "35") (pinfunction "35_35") (pintype "passive"))
      (node (ref "J7") (pin "57") (pinfunction "57_57") (pintype "passive"))
      (node (ref "J7") (pin "62") (pinfunction "62_62") (pintype "passive"))
      (node (ref "J7") (pin "68") (pinfunction "68_68") (pintype "passive"))
      (node (ref "J7") (pin "MH1") (pinfunction "MH1_MH1") (pintype "power_in"))
      (node (ref "J7") (pin "MH2") (pinfunction "MH2_MH2") (pintype "power_in"))
      (node (ref "JP2") (pin "1") (pinfunction "1_1") (pintype "bidirectional"))
      (node (ref "JP2") (pin "11") (pinfunction "11_11") (pintype "bidirectional"))
      (node (ref "JP2") (pin "13") (pinfunction "13_13") (pintype "bidirectional"))
      (node (ref "JP2") (pin "3") (pinfunction "3_3") (pintype "bidirectional"))
      (node (ref "JP2") (pin "5") (pinfunction "5_5") (pintype "bidirectional"))
      (node (ref "JP2") (pin "7") (pinfunction "7_7") (pintype "bidirectional"))
      (node (ref "JP2") (pin "9") (pinfunction "9_9") (pintype "bidirectional"))
      (node (ref "JP3") (pin "2") (pinfunction "2_2") (pintype "bidirectional"))
      (node (ref "JP3") (pin "4") (pinfunction "4_4") (pintype "bidirectional"))
      (node (ref "L4") (pin "1") (pinfunction "1_1") (pintype "passive"))
      (node (ref "PCIE") (pin "1") (pinfunction "GND1_1") (pintype "bidirectional"))
      (node (ref "PCIE") (pin "15") (pinfunction "GND4_15") (pintype "bidirectional"))
      (node (ref "PCIE") (pin "21") (pinfunction "GND5_21") (pintype "bidirectional"))
      (node (ref "PCIE") (pin "27") (pinfunction "GND6_27") (pintype "bidirectional"))
      (node (ref "PCIE") (pin "3") (pinfunction "GND2_3") (pintype "bidirectional"))
      (node (ref "PCIE") (pin "33") (pinfunction "GND7_33") (pintype "bidirectional"))
      (node (ref "PCIE") (pin "39") (pinfunction "GND8_39") (pintype "bidirectional"))
      (node (ref "PCIE") (pin "45") (pinfunction "GND9_45") (pintype "bidirectional"))
      (node (ref "PCIE") (pin "51") (pinfunction "GND10_51") (pintype "bidirectional"))
      (node (ref "PCIE") (pin "57") (pinfunction "GND11_57") (pintype "bidirectional"))
      (node (ref "PCIE") (pin "71") (pinfunction "GND12_71") (pintype "bidirectional"))
      (node (ref "PCIE") (pin "73") (pinfunction "GND13_73") (pintype "bidirectional"))
      (node (ref "PCIE") (pin "75") (pinfunction "GND14_75") (pintype "bidirectional"))
      (node (ref "PCIE") (pin "9") (pinfunction "GND3_9") (pintype "bidirectional"))
      (node (ref "PCIE") (pin "S1") (pinfunction "S1_S1") (pintype "bidirectional"))
      (node (ref "PCIE") (pin "S2") (pinfunction "S2_S2") (pintype "bidirectional"))
      (node (ref "R1") (pin "2") (pinfunction "2_2") (pintype "passive"))
      (node (ref "R103") (pin "1") (pinfunction "1_1") (pintype "passive"))
      (node (ref "R107") (pin "1") (pinfunction "1_1") (pintype "passive"))
      (node (ref "R11") (pin "2") (pinfunction "2_2") (pintype "passive"))
      (node (ref "R111") (pin "1") (pinfunction "1_1") (pintype "passive"))
      (node (ref "R115") (pin "1") (pinfunction "1_1") (pintype "passive"))
      (node (ref "R13") (pin "2") (pinfunction "2_2") (pintype "passive"))
      (node (ref "R2") (pin "2") (pinfunction "2_2") (pintype "passive"))
      (node (ref "R57") (pin "2") (pinfunction "2_2") (pintype "passive"))
      (node (ref "R73") (pin "2") (pinfunction "2_2") (pintype "passive"))
      (node (ref "R87") (pin "1") (pinfunction "1_1") (pintype "passive"))
      (node (ref "R91") (pin "1") (pinfunction "1_1") (pintype "passive"))
      (node (ref "R95") (pin "1") (pinfunction "1_1") (pintype "passive"))
      (node (ref "R99") (pin "1") (pinfunction "1_1") (pintype "passive"))
      (node (ref "SD1") (pin "MT1") (pinfunction "MT1_MT1") (pintype "bidirectional"))
      (node (ref "SD1") (pin "MT2") (pinfunction "MT2_MT2") (pintype "bidirectional"))
      (node (ref "SD1") (pin "MT3") (pinfunction "MT3_MT3") (pintype "bidirectional"))
      (node (ref "SD1") (pin "MT4") (pinfunction "MT4_MT4") (pintype "bidirectional"))
      (node (ref "SD1") (pin "VSS") (pinfunction "VSS_VSS") (pintype "bidirectional"))
      (node (ref "SW1") (pin "1") (pinfunction "1_1") (pintype "passive"))
      (node (ref "SW1") (pin "3") (pinfunction "3_3") (pintype "passive"))
      (node (ref "SW1") (pin "4") (pinfunction "4_4") (pintype "passive"))
      (node (ref "TP_GND") (pin "TP") (pinfunction "P$1_TP") (pintype "bidirectional"))
      (node (ref "USB3") (pin "13") (pinfunction "GND_13") (pintype "passive"))
      (node (ref "USB3") (pin "16") (pinfunction "GND_DRAIN_16") (pintype "passive"))
      (node (ref "USB3") (pin "4") (pinfunction "GND_4") (pintype "passive"))
      (node (ref "USB3") (pin "7") (pinfunction "GND_DRAIN_7") (pintype "passive"))
      (node (ref "USB3") (pin "S1") (pinfunction "SHIELD_S1") (pintype "passive"))
      (node (ref "USB3") (pin "S2") (pinfunction "SHIELD_S2") (pintype "passive"))
      (node (ref "USB3") (pin "S3") (pinfunction "SHIELD_S3") (pintype "passive"))
      (node (ref "USB3") (pin "S4") (pinfunction "SHIELD_S4") (pintype "passive"))
      (node (ref "USBC") (pin "A1") (pinfunction "GND_A1") (pintype "passive"))
      (node (ref "USBC") (pin "A12") (pinfunction "GND1_A12") (pintype "passive"))
      (node (ref "USBC") (pin "B1") (pinfunction "GND3_B1") (pintype "passive"))
      (node (ref "USBC") (pin "B12") (pinfunction "GND2_B12") (pintype "passive"))
      (node (ref "USBC") (pin "S1") (pinfunction "SHIELD_S1") (pintype "passive"))
      (node (ref "USBC") (pin "S2") (pinfunction "SHIELD_S2") (pintype "passive"))
      (node (ref "USBC") (pin "S3") (pinfunction "SHIELD_S3") (pintype "passive"))
      (node (ref "USBC") (pin "S4") (pinfunction "SHIELD_S4") (pintype "passive"))
      (node (ref "X2") (pin "2") (pinfunction "VSS_2") (pintype "power_in"))
    )
    (net (code "109") (name "GPIO2") (class "Default")
      (node (ref "GPIO") (pin "3") (pinfunction "3_3") (pintype "bidirectional"))
      (node (ref "J2") (pin "58") (pinfunction "58_58") (pintype "passive"))
    )
    (net (code "110") (name "GPIO3") (class "Default")
      (node (ref "GPIO") (pin "5") (pinfunction "5_5") (pintype "bidirectional"))
      (node (ref "J2") (pin "56") (pinfunction "56_56") (pintype "passive"))
    )
    (net (code "111") (name "GPIO4") (class "Default")
      (node (ref "GPIO") (pin "7") (pinfunction "7_7") (pintype "bidirectional"))
      (node (ref "J2") (pin "54") (pinfunction "54_54") (pintype "passive"))
      (node (ref "R37") (pin "2") (pinfunction "2_2") (pintype "passive"))
    )
    (net (code "112") (name "GPIO5") (class "Default")
      (node (ref "GPIO") (pin "29") (pinfunction "29_29") (pintype "bidirectional"))
      (node (ref "J2") (pin "34") (pinfunction "34_34") (pintype "passive"))
      (node (ref "R41") (pin "2") (pinfunction "2_2") (pintype "passive"))
    )
    (net (code "113") (name "GPIO6") (class "Default")
      (node (ref "GPIO") (pin "31") (pinfunction "31_31") (pintype "bidirectional"))
      (node (ref "J2") (pin "30") (pinfunction "30_30") (pintype "passive"))
      (node (ref "R39") (pin "2") (pinfunction "2_2") (pintype "passive"))
    )
    (net (code "114") (name "GPIO7") (class "Default")
      (node (ref "GPIO") (pin "26") (pinfunction "26_26") (pintype "bidirectional"))
      (node (ref "J2") (pin "37") (pinfunction "37_37") (pintype "passive"))
      (node (ref "R30") (pin "2") (pinfunction "2_2") (pintype "passive"))
    )
    (net (code "115") (name "GPIO8") (class "Default")
      (node (ref "GPIO") (pin "24") (pinfunction "24_24") (pintype "bidirectional"))
      (node (ref "J2") (pin "39") (pinfunction "39_39") (pintype "passive"))
      (node (ref "R29") (pin "2") (pinfunction "2_2") (pintype "passive"))
    )
    (net (code "116") (name "GPIO9") (class "Default")
      (node (ref "GPIO") (pin "21") (pinfunction "21_21") (pintype "bidirectional"))
      (node (ref "J2") (pin "40") (pinfunction "40_40") (pintype "passive"))
      (node (ref "R27") (pin "2") (pinfunction "2_2") (pintype "passive"))
    )
    (net (code "117") (name "GPIO10") (class "Default")
      (node (ref "GPIO") (pin "19") (pinfunction "19_19") (pintype "bidirectional"))
      (node (ref "J2") (pin "44") (pinfunction "44_44") (pintype "passive"))
      (node (ref "R28") (pin "2") (pinfunction "2_2") (pintype "passive"))
    )
    (net (code "118") (name "GPIO11") (class "Default")
      (node (ref "GPIO") (pin "23") (pinfunction "23_23") (pintype "bidirectional"))
      (node (ref "J2") (pin "38") (pinfunction "38_38") (pintype "passive"))
      (node (ref "R26") (pin "2") (pinfunction "2_2") (pintype "passive"))
    )
    (net (code "119") (name "GPIO12") (class "Default")
      (node (ref "GPIO") (pin "32") (pinfunction "32_32") (pintype "bidirectional"))
      (node (ref "J2") (pin "31") (pinfunction "31_31") (pintype "passive"))
    )
    (net (code "120") (name "GPIO13") (class "Default")
      (node (ref "GPIO") (pin "33") (pinfunction "33_33") (pintype "bidirectional"))
      (node (ref "J2") (pin "28") (pinfunction "28_28") (pintype "passive"))
      (node (ref "R40") (pin "2") (pinfunction "2_2") (pintype "passive"))
    )
    (net (code "121") (name "GPIO14") (class "Default")
      (node (ref "GPIO") (pin "8") (pinfunction "8_8") (pintype "bidirectional"))
      (node (ref "J2") (pin "55") (pinfunction "55_55") (pintype "passive"))
    )
    (net (code "122") (name "GPIO15") (class "Default")
      (node (ref "GPIO") (pin "10") (pinfunction "10_10") (pintype "bidirectional"))
      (node (ref "J2") (pin "51") (pinfunction "51_51") (pintype "passive"))
    )
    (net (code "123") (name "GPIO16") (class "Default")
      (node (ref "GPIO") (pin "36") (pinfunction "36_36") (pintype "bidirectional"))
      (node (ref "J2") (pin "29") (pinfunction "29_29") (pintype "passive"))
      (node (ref "R34") (pin "2") (pinfunction "2_2") (pintype "passive"))
    )
    (net (code "124") (name "GPIO17") (class "Default")
      (node (ref "GPIO") (pin "11") (pinfunction "11_11") (pintype "bidirectional"))
      (node (ref "J2") (pin "50") (pinfunction "50_50") (pintype "passive"))
      (node (ref "R33") (pin "2") (pinfunction "2_2") (pintype "passive"))
    )
    (net (code "125") (name "GPIO18") (class "Default")
      (node (ref "GPIO") (pin "12") (pinfunction "12_12") (pintype "bidirectional"))
      (node (ref "J2") (pin "49") (pinfunction "49_49") (pintype "passive"))
      (node (ref "R32") (pin "2") (pinfunction "2_2") (pintype "passive"))
    )
    (net (code "126") (name "GPIO19") (class "Default")
      (node (ref "GPIO") (pin "35") (pinfunction "35_35") (pintype "bidirectional"))
      (node (ref "J2") (pin "26") (pinfunction "26_26") (pintype "passive"))
      (node (ref "R18") (pin "2") (pinfunction "2_2") (pintype "passive"))
    )
    (net (code "127") (name "GPIO20") (class "Default")
      (node (ref "GPIO") (pin "38") (pinfunction "38_38") (pintype "bidirectional"))
      (node (ref "J2") (pin "27") (pinfunction "27_27") (pintype "passive"))
      (node (ref "R17") (pin "2") (pinfunction "2_2") (pintype "passive"))
    )
    (net (code "128") (name "GPIO21") (class "Default")
      (node (ref "GPIO") (pin "40") (pinfunction "40_40") (pintype "bidirectional"))
      (node (ref "J2") (pin "25") (pinfunction "25_25") (pintype "passive"))
      (node (ref "R25") (pin "2") (pinfunction "2_2") (pintype "passive"))
    )
    (net (code "129") (name "GPIO22") (class "Default")
      (node (ref "GPIO") (pin "15") (pinfunction "15_15") (pintype "bidirectional"))
      (node (ref "J2") (pin "46") (pinfunction "46_46") (pintype "passive"))
    )
    (net (code "130") (name "GPIO23") (class "Default")
      (node (ref "GPIO") (pin "16") (pinfunction "16_16") (pintype "bidirectional"))
      (node (ref "J2") (pin "47") (pinfunction "47_47") (pintype "passive"))
      (node (ref "R31") (pin "2") (pinfunction "2_2") (pintype "passive"))
    )
    (net (code "131") (name "GPIO24") (class "Default")
      (node (ref "GPIO") (pin "18") (pinfunction "18_18") (pintype "bidirectional"))
      (node (ref "J2") (pin "45") (pinfunction "45_45") (pintype "passive"))
      (node (ref "R36") (pin "2") (pinfunction "2_2") (pintype "passive"))
    )
    (net (code "132") (name "GPIO25") (class "Default")
      (node (ref "GPIO") (pin "22") (pinfunction "22_22") (pintype "bidirectional"))
      (node (ref "J2") (pin "41") (pinfunction "41_41") (pintype "passive"))
      (node (ref "R38") (pin "2") (pinfunction "2_2") (pintype "passive"))
    )
    (net (code "133") (name "GPIO26") (class "Default")
      (node (ref "GPIO") (pin "37") (pinfunction "37_37") (pintype "bidirectional"))
      (node (ref "J2") (pin "24") (pinfunction "24_24") (pintype "passive"))
    )
    (net (code "134") (name "GPIO27") (class "Default")
      (node (ref "GPIO") (pin "13") (pinfunction "13_13") (pintype "bidirectional"))
      (node (ref "J2") (pin "48") (pinfunction "48_48") (pintype "passive"))
      (node (ref "R35") (pin "2") (pinfunction "2_2") (pintype "passive"))
    )
    (net (code "135") (name "GPIO_VREF") (class "Default")
      (node (ref "J2") (pin "78") (pinfunction "78_78") (pintype "passive"))
      (node (ref "R3") (pin "1") (pinfunction "1_1") (pintype "passive"))
      (node (ref "R4") (pin "1") (pinfunction "1_1") (pintype "passive"))
      (node (ref "R6") (pin "2") (pinfunction "2_2") (pintype "passive"))
      (node (ref "R7") (pin "2") (pinfunction "2_2") (pintype "passive"))
      (node (ref "TP-GREF") (pin "TP") (pinfunction "P$1_TP") (pintype "bidirectional"))
    )
    (net (code "136") (name "HDMI0_CEC") (class "Default")
      (node (ref "HDMI2") (pin "13") (pinfunction "GROUND_13") (pintype "passive"))
      (node (ref "J1") (pin "51") (pinfunction "51_51") (pintype "passive"))
    )
    (net (code "137") (name "HDMI0_CK_N") (class "Default")
      (node (ref "HDMI2") (pin "12") (pinfunction "TMDSCLOCK-_12") (pintype "passive"))
      (node (ref "J1") (pin "90") (pinfunction "90_90") (pintype "passive"))
    )
    (net (code "138") (name "HDMI0_CK_P") (class "Default")
      (node (ref "HDMI2") (pin "10") (pinfunction "TMDSCLOCKSHIELD_10") (pintype "passive"))
      (node (ref "J1") (pin "88") (pinfunction "88_88") (pintype "passive"))
    )
    (net (code "139") (name "HDMI0_D0_N") (class "Default")
      (node (ref "HDMI2") (pin "9") (pinfunction "TMDS0-_9") (pintype "passive"))
      (node (ref "J1") (pin "84") (pinfunction "84_84") (pintype "passive"))
    )
    (net (code "140") (name "HDMI0_D0_P") (class "Default")
      (node (ref "HDMI2") (pin "7") (pinfunction "TMDS0SHIELD_7") (pintype "passive"))
      (node (ref "J1") (pin "82") (pinfunction "82_82") (pintype "passive"))
    )
    (net (code "141") (name "HDMI0_D1_N") (class "Default")
      (node (ref "HDMI2") (pin "6") (pinfunction "TMDS1-_6") (pintype "passive"))
      (node (ref "J1") (pin "78") (pinfunction "78_78") (pintype "passive"))
    )
    (net (code "142") (name "HDMI0_D1_P") (class "Default")
      (node (ref "HDMI2") (pin "4") (pinfunction "TMDS1SHIELD_4") (pintype "passive"))
      (node (ref "J1") (pin "76") (pinfunction "76_76") (pintype "passive"))
    )
    (net (code "143") (name "HDMI0_D2_N") (class "Default")
      (node (ref "HDMI2") (pin "3") (pinfunction "TMDS2-_3") (pintype "passive"))
      (node (ref "J1") (pin "72") (pinfunction "72_72") (pintype "passive"))
    )
    (net (code "144") (name "HDMI0_D2_P") (class "Default")
      (node (ref "HDMI2") (pin "1") (pinfunction "TMDS2SHIELD_1") (pintype "passive"))
      (node (ref "J1") (pin "70") (pinfunction "70_70") (pintype "passive"))
    )
    (net (code "145") (name "HDMI0_HOTPLUG") (class "Default")
      (node (ref "HDMI2") (pin "19") (pinfunction "HOTPLUG/HEC+_19") (pintype "passive"))
      (node (ref "J1") (pin "53") (pinfunction "53_53") (pintype "passive"))
    )
    (net (code "146") (name "HDMI0_SCL") (class "Default")
      (node (ref "HDMI2") (pin "15") (pinfunction "SCL_15") (pintype "passive"))
      (node (ref "J1") (pin "100") (pinfunction "100_100") (pintype "passive"))
    )
    (net (code "147") (name "HDMI0_SDA") (class "Default")
      (node (ref "HDMI2") (pin "16") (pinfunction "SDA_16") (pintype "passive"))
      (node (ref "J1") (pin "99") (pinfunction "99_99") (pintype "passive"))
    )
    (net (code "148") (name "HDMI1_CEC") (class "Default")
      (node (ref "HDMI1") (pin "13") (pinfunction "GROUND_13") (pintype "passive"))
      (node (ref "J1") (pin "49") (pinfunction "49_49") (pintype "passive"))
    )
    (net (code "149") (name "HDMI1_CK_N") (class "Default")
      (node (ref "HDMI1") (pin "12") (pinfunction "TMDSCLOCK-_12") (pintype "passive"))
      (node (ref "J1") (pin "66") (pinfunction "66_66") (pintype "passive"))
    )
    (net (code "150") (name "HDMI1_CK_P") (class "Default")
      (node (ref "HDMI1") (pin "10") (pinfunction "TMDSCLOCKSHIELD_10") (pintype "passive"))
      (node (ref "J1") (pin "64") (pinfunction "64_64") (pintype "passive"))
    )
    (net (code "151") (name "HDMI1_D0_N") (class "Default")
      (node (ref "HDMI1") (pin "9") (pinfunction "TMDS0-_9") (pintype "passive"))
      (node (ref "J1") (pin "60") (pinfunction "60_60") (pintype "passive"))
    )
    (net (code "152") (name "HDMI1_D0_P") (class "Default")
      (node (ref "HDMI1") (pin "7") (pinfunction "TMDS0SHIELD_7") (pintype "passive"))
      (node (ref "J1") (pin "58") (pinfunction "58_58") (pintype "passive"))
    )
    (net (code "153") (name "HDMI1_D1_N") (class "Default")
      (node (ref "HDMI1") (pin "6") (pinfunction "TMDS1-_6") (pintype "passive"))
      (node (ref "J1") (pin "54") (pinfunction "54_54") (pintype "passive"))
    )
    (net (code "154") (name "HDMI1_D1_P") (class "Default")
      (node (ref "HDMI1") (pin "4") (pinfunction "TMDS1SHIELD_4") (pintype "passive"))
      (node (ref "J1") (pin "52") (pinfunction "52_52") (pintype "passive"))
    )
    (net (code "155") (name "HDMI1_D2_N") (class "Default")
      (node (ref "HDMI1") (pin "3") (pinfunction "TMDS2-_3") (pintype "passive"))
      (node (ref "J1") (pin "48") (pinfunction "48_48") (pintype "passive"))
    )
    (net (code "156") (name "HDMI1_D2_P") (class "Default")
      (node (ref "HDMI1") (pin "1") (pinfunction "TMDS2SHIELD_1") (pintype "passive"))
      (node (ref "J1") (pin "46") (pinfunction "46_46") (pintype "passive"))
    )
    (net (code "157") (name "HDMI1_HOTPLUG") (class "Default")
      (node (ref "HDMI1") (pin "19") (pinfunction "HOTPLUG/HEC+_19") (pintype "passive"))
      (node (ref "J1") (pin "43") (pinfunction "43_43") (pintype "passive"))
    )
    (net (code "158") (name "HDMI1_SCL") (class "Default")
      (node (ref "HDMI1") (pin "15") (pinfunction "SCL_15") (pintype "passive"))
      (node (ref "J1") (pin "47") (pinfunction "47_47") (pintype "passive"))
    )
    (net (code "159") (name "HDMI1_SDA") (class "Default")
      (node (ref "HDMI1") (pin "16") (pinfunction "SDA_16") (pintype "passive"))
      (node (ref "J1") (pin "45") (pinfunction "45_45") (pintype "passive"))
    )
    (net (code "160") (name "HDMI_5V") (class "Default")
      (node (ref "C4") (pin "1") (pinfunction "1_1") (pintype "passive"))
      (node (ref "HDMI1") (pin "18") (pinfunction "POWER_18") (pintype "power_in"))
      (node (ref "HDMI2") (pin "18") (pinfunction "POWER_18") (pintype "power_in"))
      (node (ref "IC4") (pin "2") (pinfunction "OUT_2") (pintype "power_in"))
      (node (ref "TP-5VHD") (pin "TP") (pinfunction "P$1_TP") (pintype "bidirectional"))
    )
    (net (code "161") (name "ID_SC") (class "Default")
      (node (ref "GPIO") (pin "28") (pinfunction "28_28") (pintype "bidirectional"))
      (node (ref "J2") (pin "35") (pinfunction "35_35") (pintype "passive"))
      (node (ref "JP1") (pin "1") (pinfunction "1_1") (pintype "bidirectional"))
    )
    (net (code "162") (name "ID_SD") (class "Default")
      (node (ref "GPIO") (pin "27") (pinfunction "27_27") (pintype "bidirectional"))
      (node (ref "J2") (pin "36") (pinfunction "36_36") (pintype "passive"))
      (node (ref "JP1") (pin "3") (pinfunction "3_3") (pintype "bidirectional"))
    )
    (net (code "163") (name "IN0+") (class "Default")
      (node (ref "IC6") (pin "4") (pinfunction "IN_A_0_4") (pintype "input"))
      (node (ref "J7") (pin "19") (pinfunction "19_19") (pintype "passive"))
    )
    (net (code "164") (name "IN1-") (class "Default")
      (node (ref "IC6") (pin "13") (pinfunction "IN_B_0_13") (pintype "input"))
      (node (ref "J7") (pin "53") (pinfunction "53_53") (pintype "passive"))
    )
    (net (code "165") (name "IN2+") (class "Default")
      (node (ref "IC6") (pin "5") (pinfunction "IN_A_1_5") (pintype "input"))
      (node (ref "J7") (pin "20") (pinfunction "20_20") (pintype "passive"))
    )
    (net (code "166") (name "IN3-") (class "Default")
      (node (ref "IC6") (pin "12") (pinfunction "IN_B_1_12") (pintype "input"))
      (node (ref "J7") (pin "54") (pinfunction "54_54") (pintype "passive"))
    )
    (net (code "167") (name "IN4+") (class "Default")
      (node (ref "IC6") (pin "6") (pinfunction "IN_A_2_6") (pintype "input"))
      (node (ref "J7") (pin "21") (pinfunction "21_21") (pintype "passive"))
    )
    (net (code "168") (name "IN5-") (class "Default")
      (node (ref "IC6") (pin "11") (pinfunction "IN_B_2_11") (pintype "input"))
      (node (ref "J7") (pin "55") (pinfunction "55_55") (pintype "passive"))
    )
    (net (code "169") (name "IN6+") (class "Default")
      (node (ref "IC6") (pin "7") (pinfunction "IN_A_3_7") (pintype "input"))
      (node (ref "J7") (pin "22") (pinfunction "22_22") (pintype "passive"))
    )
    (net (code "170") (name "IN7-") (class "Default")
      (node (ref "IC6") (pin "10") (pinfunction "IN_B_3_10") (pintype "input"))
      (node (ref "J7") (pin "56") (pinfunction "56_56") (pintype "passive"))
    )
    (net (code "171") (name "IN8+") (class "Default")
      (node (ref "IC8") (pin "4") (pinfunction "IN_A_0_4") (pintype "input"))
      (node (ref "J7") (pin "24") (pinfunction "24_24") (pintype "passive"))
    )
    (net (code "172") (name "IN9-") (class "Default")
      (node (ref "IC8") (pin "13") (pinfunction "IN_B_0_13") (pintype "input"))
      (node (ref "J7") (pin "58") (pinfunction "58_58") (pintype "passive"))
    )
    (net (code "173") (name "IN10+") (class "Default")
      (node (ref "IC8") (pin "5") (pinfunction "IN_A_1_5") (pintype "input"))
      (node (ref "J7") (pin "25") (pinfunction "25_25") (pintype "passive"))
    )
    (net (code "174") (name "IN11-") (class "Default")
      (node (ref "IC8") (pin "12") (pinfunction "IN_B_1_12") (pintype "input"))
      (node (ref "J7") (pin "59") (pinfunction "59_59") (pintype "passive"))
    )
    (net (code "175") (name "IN12+") (class "Default")
      (node (ref "IC8") (pin "6") (pinfunction "IN_A_2_6") (pintype "input"))
      (node (ref "J7") (pin "26") (pinfunction "26_26") (pintype "passive"))
    )
    (net (code "176") (name "IN13-") (class "Default")
      (node (ref "IC8") (pin "11") (pinfunction "IN_B_2_11") (pintype "input"))
      (node (ref "J7") (pin "60") (pinfunction "60_60") (pintype "passive"))
    )
    (net (code "177") (name "IN14+") (class "Default")
      (node (ref "IC8") (pin "7") (pinfunction "IN_A_3_7") (pintype "input"))
      (node (ref "J7") (pin "27") (pinfunction "27_27") (pintype "passive"))
    )
    (net (code "178") (name "IN15-") (class "Default")
      (node (ref "IC8") (pin "10") (pinfunction "IN_B_3_10") (pintype "input"))
      (node (ref "J7") (pin "61") (pinfunction "61_61") (pintype "passive"))
    )
    (net (code "179") (name "LED_NACT") (class "Default")
      (node (ref "J2") (pin "21") (pinfunction "21_21") (pintype "passive"))
    )
    (net (code "180") (name "M2_3V3") (class "Default")
      (node (ref "C12") (pin "1") (pinfunction "1_1") (pintype "passive"))
      (node (ref "C13") (pin "1") (pinfunction "1_1") (pintype "passive"))
      (node (ref "C14") (pin "1") (pinfunction "1_1") (pintype "passive"))
      (node (ref "C15") (pin "1") (pinfunction "1_1") (pintype "passive"))
      (node (ref "C16") (pin "1") (pinfunction "1_1") (pintype "passive"))
      (node (ref "C17") (pin "1") (pinfunction "1_1") (pintype "passive"))
      (node (ref "L1") (pin "2") (pinfunction "2_2") (pintype "passive"))
      (node (ref "PCIE") (pin "12") (pinfunction "VCC3_12") (pintype "bidirectional"))
      (node (ref "PCIE") (pin "14") (pinfunction "VCC4_14") (pintype "bidirectional"))
      (node (ref "PCIE") (pin "16") (pinfunction "VCC5_16") (pintype "bidirectional"))
      (node (ref "PCIE") (pin "18") (pinfunction "VCC6_18") (pintype "bidirectional"))
      (node (ref "PCIE") (pin "2") (pinfunction "VCC1_2") (pintype "bidirectional"))
      (node (ref "PCIE") (pin "4") (pinfunction "VCC2_4") (pintype "bidirectional"))
      (node (ref "PCIE") (pin "70") (pinfunction "VCC7_70") (pintype "bidirectional"))
      (node (ref "PCIE") (pin "72") (pinfunction "VCC8_72") (pintype "bidirectional"))
      (node (ref "PCIE") (pin "74") (pinfunction "VCC9_74") (pintype "bidirectional"))
      (node (ref "R12") (pin "1") (pinfunction "1_1") (pintype "passive"))
      (node (ref "TP-VM2") (pin "TP") (pinfunction "P$1_TP") (pintype "bidirectional"))
      (node (ref "X2") (pin "3") (pinfunction "OUT_3") (pintype "output"))
      (node (ref "X2") (pin "4") (pinfunction "VDD_4") (pintype "power_in"))
    )
    (net (code "181") (name "MISO_SEL") (class "Default")
      (node (ref "IC16") (pin "7") (pinfunction "1C_7") (pintype "input"))
      (node (ref "IC17") (pin "2") (pinfunction "IN_2") (pintype "bidirectional"))
    )
    (net (code "182") (name "MUX_A_OUTA") (class "Default")
      (node (ref "IC6") (pin "8") (pinfunction "OUT_A_8") (pintype "output"))
      (node (ref "R43") (pin "2") (pinfunction "2_2") (pintype "passive"))
    )
    (net (code "183") (name "MUX_A_OUTB") (class "Default")
      (node (ref "IC6") (pin "9") (pinfunction "OUT_B_9") (pintype "output"))
      (node (ref "R44") (pin "1") (pinfunction "1_1") (pintype "passive"))
    )
    (net (code "184") (name "MUX_B_OUTA") (class "Default")
      (node (ref "IC8") (pin "8") (pinfunction "OUT_A_8") (pintype "output"))
      (node (ref "R24") (pin "2") (pinfunction "2_2") (pintype "passive"))
    )
    (net (code "185") (name "MUX_B_OUTB") (class "Default")
      (node (ref "IC8") (pin "9") (pinfunction "OUT_B_9") (pintype "output"))
      (node (ref "R42") (pin "1") (pinfunction "1_1") (pintype "passive"))
    )
    (net (code "186") (name "NPWR_LED") (class "Default")
      (node (ref "IC3") (pin "2") (pinfunction "A_2") (pintype "input"))
      (node (ref "J2") (pin "95") (pinfunction "95_95") (pintype "passive"))
      (node (ref "TP-LED") (pin "TP") (pinfunction "P$1_TP") (pintype "bidirectional"))
    )
    (net (code "187") (name "NRPIBOOT") (class "Default")
      (node (ref "J2") (pin "93") (pinfunction "93_93") (pintype "passive"))
      (node (ref "JP2") (pin "2") (pinfunction "2_2") (pintype "bidirectional"))
    )
    (net (code "188") (name "Net-(C11-Pad1)") (class "Default")
      (node (ref "C11") (pin "1") (pinfunction "1_1") (pintype "passive"))
      (node (ref "ETH1") (pin "CT1") (pinfunction "CT1_CT1") (pintype "bidirectional"))
      (node (ref "ETH1") (pin "CT2") (pinfunction "CT2_CT2") (pintype "bidirectional"))
      (node (ref "ETH1") (pin "CT3") (pinfunction "CT3_CT3") (pintype "bidirectional"))
      (node (ref "ETH1") (pin "CT4") (pinfunction "CT4_CT4") (pintype "bidirectional"))
    )
    (net (code "189") (name "Net-(C72-Pad2)") (class "Default")
      (node (ref "C72") (pin "2") (pinfunction "2_2") (pintype "passive"))
      (node (ref "C73") (pin "2") (pinfunction "2_2") (pintype "passive"))
      (node (ref "R49") (pin "1") (pinfunction "1_1") (pintype "passive"))
    )
    (net (code "190") (name "Net-(C74-Pad1)") (class "Default")
      (node (ref "C74") (pin "1") (pinfunction "1_1") (pintype "passive"))
      (node (ref "R49") (pin "2") (pinfunction "2_2") (pintype "bidirectional"))
      (node (ref "R50") (pin "1") (pinfunction "1_1") (pintype "passive"))
    )
    (net (code "191") (name "Net-(D3-PadA)") (class "Default")
      (node (ref "D3") (pin "A") (pinfunction "A_A") (pintype "passive"))
      (node (ref "IC14") (pin "1") (pinfunction "INP_1") (pintype "power_in"))
      (node (ref "IC14") (pin "24") (pinfunction "INP_24") (pintype "power_in"))
      (node (ref "L3") (pin "2") (pinfunction "2_2") (pintype "passive"))
    )
    (net (code "192") (name "Net-(D4-PadC)") (class "Default")
      (node (ref "D4") (pin "C") (pinfunction "C_C") (pintype "passive"))
      (node (ref "IC14") (pin "13") (pinfunction "OUTN_13") (pintype "power_in"))
      (node (ref "IC14") (pin "14") (pinfunction "OUTN_14") (pintype "power_in"))
      (node (ref "L4") (pin "2") (pinfunction "2_2") (pintype "passive"))
    )
    (net (code "193") (name "Net-(ETH1-P17)") (class "Default")
      (node (ref "ETH1") (pin "17") (pinfunction "P17_17") (pintype "bidirectional"))
      (node (ref "R9") (pin "1") (pinfunction "1_1") (pintype "passive"))
    )
    (net (code "194") (name "Net-(ETH1-P19)") (class "Default")
      (node (ref "ETH1") (pin "19") (pinfunction "P19_19") (pintype "bidirectional"))
      (node (ref "R8") (pin "2") (pinfunction "2_2") (pintype "passive"))
    )
    (net (code "195") (name "Net-(IC2-ILIM)") (class "Default")
      (node (ref "IC2") (pin "5") (pinfunction "ILIM_5") (pintype "bidirectional"))
      (node (ref "R2") (pin "1") (pinfunction "1_1") (pintype "passive"))
    )
    (net (code "196") (name "Net-(IC3-Y)") (class "Default")
      (node (ref "IC3") (pin "4") (pinfunction "Y_4") (pintype "output"))
      (node (ref "R5") (pin "2") (pinfunction "2_2") (pintype "passive"))
    )
    (net (code "197") (name "Net-(IC5-FB)") (class "Default")
      (node (ref "C13") (pin "2") (pinfunction "2_2") (pintype "passive"))
      (node (ref "IC5") (pin "1") (pinfunction "FB_1") (pintype "bidirectional"))
      (node (ref "R12") (pin "2") (pinfunction "2_2") (pintype "passive"))
      (node (ref "R13") (pin "1") (pinfunction "1_1") (pintype "passive"))
      (node (ref "TP-M2FB") (pin "TP") (pinfunction "P$1_TP") (pintype "bidirectional"))
    )
    (net (code "198") (name "Net-(IC5-LX)") (class "Default")
      (node (ref "IC5") (pin "6") (pinfunction "LX_6") (pintype "power_in"))
      (node (ref "L1") (pin "1") (pinfunction "1_1") (pintype "passive"))
      (node (ref "TP-LX") (pin "TP") (pinfunction "P$1_TP") (pintype "bidirectional"))
    )
    (net (code "199") (name "Net-(IC7-OUT+)") (class "Default")
      (node (ref "IC7") (pin "19") (pinfunction "OUT+_19") (pintype "output"))
      (node (ref "R20") (pin "2") (pinfunction "2_2") (pintype "passive"))
    )
    (net (code "200") (name "Net-(IC7-OUT-)") (class "Default")
      (node (ref "IC7") (pin "20") (pinfunction "OUT-_20") (pintype "output"))
      (node (ref "R21") (pin "2") (pinfunction "2_2") (pintype "passive"))
    )
    (net (code "201") (name "Net-(IC9-OUT+)") (class "Default")
      (node (ref "IC9") (pin "19") (pinfunction "OUT+_19") (pintype "output"))
      (node (ref "R22") (pin "2") (pinfunction "2_2") (pintype "passive"))
    )
    (net (code "202") (name "Net-(IC9-OUT-)") (class "Default")
      (node (ref "IC9") (pin "20") (pinfunction "OUT-_20") (pintype "output"))
      (node (ref "R23") (pin "2") (pinfunction "2_2") (pintype "passive"))
    )
    (net (code "203") (name "Net-(IC10-CONVST)") (class "Default")
      (node (ref "IC10") (pin "13") (pinfunction "CONVST_13") (pintype "input"))
      (node (ref "R15") (pin "2") (pinfunction "2_2") (pintype "passive"))
    )
    (net (code "204") (name "Net-(IC11-+IN)") (class "Default")
      (node (ref "IC11") (pin "3") (pinfunction "+IN_3") (pintype "input"))
      (node (ref "R50") (pin "2") (pinfunction "2_2") (pintype "passive"))
    )
    (net (code "205") (name "Net-(IC14-CN)") (class "Default")
      (node (ref "C92") (pin "1") (pinfunction "1_1") (pintype "passive"))
      (node (ref "IC14") (pin "18") (pinfunction "CN_18") (pintype "input"))
    )
    (net (code "206") (name "Net-(IC14-CP)") (class "Default")
      (node (ref "C91") (pin "1") (pinfunction "1_1") (pintype "passive"))
      (node (ref "IC14") (pin "21") (pinfunction "CP_21") (pintype "input"))
    )
    (net (code "207") (name "Net-(IC14-ENN)") (class "Default")
      (node (ref "C86") (pin "1") (pinfunction "1_1") (pintype "passive"))
      (node (ref "IC14") (pin "10") (pinfunction "ENN_10") (pintype "input"))
      (node (ref "IC14") (pin "11") (pinfunction "PSN_11") (pintype "input"))
      (node (ref "IC14") (pin "4") (pinfunction "VIN_4") (pintype "power_in"))
      (node (ref "IC14") (pin "8") (pinfunction "ENP_8") (pintype "input"))
      (node (ref "IC14") (pin "9") (pinfunction "PSP_9") (pintype "input"))
      (node (ref "R14") (pin "1") (pinfunction "1_1") (pintype "passive"))
    )
    (net (code "208") (name "Net-(IC15-NR{slash}SS)") (class "Default")
      (node (ref "C103") (pin "1") (pinfunction "1_1") (pintype "passive"))
      (node (ref "IC15") (pin "3") (pinfunction "NR/SS_3") (pintype "input"))
    )
    (net (code "209") (name "Net-(IC16-2C)") (class "Default")
      (node (ref "IC16") (pin "3") (pinfunction "2C_3") (pintype "input"))
      (node (ref "IC17") (pin "4") (pinfunction "OUT_4") (pintype "bidirectional"))
    )
    (net (code "210") (name "Net-(IC24--IN)") (class "Default")
      (node (ref "C129") (pin "1") (pinfunction "1_1") (pintype "passive"))
      (node (ref "IC24") (pin "4") (pinfunction "-IN_4") (pintype "input"))
      (node (ref "R87") (pin "2") (pinfunction "2_2") (pintype "passive"))
      (node (ref "R88") (pin "2") (pinfunction "2_2") (pintype "passive"))
      (node (ref "R89") (pin "1") (pinfunction "1_1") (pintype "passive"))
    )
    (net (code "211") (name "Net-(IC24-OUT)") (class "Default")
      (node (ref "C129") (pin "2") (pinfunction "2_2") (pintype "passive"))
      (node (ref "IC24") (pin "1") (pinfunction "OUT_1") (pintype "output"))
      (node (ref "R90") (pin "1") (pinfunction "1_1") (pintype "passive"))
    )
    (net (code "212") (name "Net-(IC25--IN)") (class "Default")
      (node (ref "C132") (pin "1") (pinfunction "1_1") (pintype "passive"))
      (node (ref "IC25") (pin "4") (pinfunction "-IN_4") (pintype "input"))
      (node (ref "R91") (pin "2") (pinfunction "2_2") (pintype "passive"))
      (node (ref "R92") (pin "2") (pinfunction "2_2") (pintype "passive"))
      (node (ref "R93") (pin "1") (pinfunction "1_1") (pintype "passive"))
    )
    (net (code "213") (name "Net-(IC25-OUT)") (class "Default")
      (node (ref "C132") (pin "2") (pinfunction "2_2") (pintype "passive"))
      (node (ref "IC25") (pin "1") (pinfunction "OUT_1") (pintype "output"))
      (node (ref "R94") (pin "1") (pinfunction "1_1") (pintype "passive"))
    )
    (net (code "214") (name "Net-(IC26--IN)") (class "Default")
      (node (ref "C135") (pin "1") (pinfunction "1_1") (pintype "passive"))
      (node (ref "IC26") (pin "4") (pinfunction "-IN_4") (pintype "input"))
      (node (ref "R95") (pin "2") (pinfunction "2_2") (pintype "passive"))
      (node (ref "R96") (pin "2") (pinfunction "2_2") (pintype "passive"))
      (node (ref "R97") (pin "1") (pinfunction "1_1") (pintype "passive"))
    )
    (net (code "215") (name "Net-(IC26-OUT)") (class "Default")
      (node (ref "C135") (pin "2") (pinfunction "2_2") (pintype "passive"))
      (node (ref "IC26") (pin "1") (pinfunction "OUT_1") (pintype "output"))
      (node (ref "R98") (pin "1") (pinfunction "1_1") (pintype "passive"))
    )
    (net (code "216") (name "Net-(IC27--IN)") (class "Default")
      (node (ref "C138") (pin "1") (pinfunction "1_1") (pintype "passive"))
      (node (ref "IC27") (pin "4") (pinfunction "-IN_4") (pintype "input"))
      (node (ref "R100") (pin "2") (pinfunction "2_2") (pintype "passive"))
      (node (ref "R101") (pin "1") (pinfunction "1_1") (pintype "passive"))
      (node (ref "R99") (pin "2") (pinfunction "2_2") (pintype "passive"))
    )
    (net (code "217") (name "Net-(IC27-OUT)") (class "Default")
      (node (ref "C138") (pin "2") (pinfunction "2_2") (pintype "passive"))
      (node (ref "IC27") (pin "1") (pinfunction "OUT_1") (pintype "output"))
      (node (ref "R102") (pin "1") (pinfunction "1_1") (pintype "passive"))
    )
    (net (code "218") (name "Net-(IC28--IN)") (class "Default")
      (node (ref "C141") (pin "1") (pinfunction "1_1") (pintype "passive"))
      (node (ref "IC28") (pin "4") (pinfunction "-IN_4") (pintype "input"))
      (node (ref "R103") (pin "2") (pinfunction "2_2") (pintype "passive"))
      (node (ref "R104") (pin "2") (pinfunction "2_2") (pintype "passive"))
      (node (ref "R105") (pin "1") (pinfunction "1_1") (pintype "passive"))
    )
    (net (code "219") (name "Net-(IC28-OUT)") (class "Default")
      (node (ref "C141") (pin "2") (pinfunction "2_2") (pintype "passive"))
      (node (ref "IC28") (pin "1") (pinfunction "OUT_1") (pintype "output"))
      (node (ref "R106") (pin "1") (pinfunction "1_1") (pintype "passive"))
    )
    (net (code "220") (name "Net-(IC29--IN)") (class "Default")
      (node (ref "C144") (pin "1") (pinfunction "1_1") (pintype "passive"))
      (node (ref "IC29") (pin "4") (pinfunction "-IN_4") (pintype "input"))
      (node (ref "R107") (pin "2") (pinfunction "2_2") (pintype "passive"))
      (node (ref "R108") (pin "2") (pinfunction "2_2") (pintype "passive"))
      (node (ref "R109") (pin "1") (pinfunction "1_1") (pintype "passive"))
    )
    (net (code "221") (name "Net-(IC29-OUT)") (class "Default")
      (node (ref "C144") (pin "2") (pinfunction "2_2") (pintype "passive"))
      (node (ref "IC29") (pin "1") (pinfunction "OUT_1") (pintype "output"))
      (node (ref "R110") (pin "1") (pinfunction "1_1") (pintype "passive"))
    )
    (net (code "222") (name "Net-(IC30--IN)") (class "Default")
      (node (ref "C147") (pin "1") (pinfunction "1_1") (pintype "passive"))
      (node (ref "IC30") (pin "4") (pinfunction "-IN_4") (pintype "input"))
      (node (ref "R111") (pin "2") (pinfunction "2_2") (pintype "passive"))
      (node (ref "R112") (pin "2") (pinfunction "2_2") (pintype "passive"))
      (node (ref "R113") (pin "1") (pinfunction "1_1") (pintype "passive"))
    )
    (net (code "223") (name "Net-(IC30-OUT)") (class "Default")
      (node (ref "C147") (pin "2") (pinfunction "2_2") (pintype "passive"))
      (node (ref "IC30") (pin "1") (pinfunction "OUT_1") (pintype "output"))
      (node (ref "R114") (pin "1") (pinfunction "1_1") (pintype "passive"))
    )
    (net (code "224") (name "Net-(IC31--IN)") (class "Default")
      (node (ref "C150") (pin "1") (pinfunction "1_1") (pintype "passive"))
      (node (ref "IC31") (pin "4") (pinfunction "-IN_4") (pintype "input"))
      (node (ref "R115") (pin "2") (pinfunction "2_2") (pintype "passive"))
      (node (ref "R116") (pin "2") (pinfunction "2_2") (pintype "passive"))
      (node (ref "R117") (pin "1") (pinfunction "1_1") (pintype "passive"))
    )
    (net (code "225") (name "Net-(IC31-OUT)") (class "Default")
      (node (ref "C150") (pin "2") (pinfunction "2_2") (pintype "passive"))
      (node (ref "IC31") (pin "1") (pinfunction "OUT_1") (pintype "output"))
      (node (ref "R118") (pin "1") (pinfunction "1_1") (pintype "passive"))
    )
    (net (code "226") (name "Net-(IC32-A1)") (class "Default")
      (node (ref "IC32") (pin "3") (pinfunction "A1_3") (pintype "bidirectional"))
      (node (ref "IC36") (pin "22") (pinfunction "GPA7_22") (pintype "bidirectional"))
    )
    (net (code "227") (name "Net-(IC32-A2)") (class "Default")
      (node (ref "IC32") (pin "4") (pinfunction "A2_4") (pintype "bidirectional"))
      (node (ref "IC36") (pin "21") (pinfunction "GPA6_21") (pintype "bidirectional"))
    )
    (net (code "228") (name "Net-(IC32-A3)") (class "Default")
      (node (ref "IC32") (pin "5") (pinfunction "A3_5") (pintype "bidirectional"))
      (node (ref "IC36") (pin "20") (pinfunction "GPA5_20") (pintype "bidirectional"))
    )
    (net (code "229") (name "Net-(IC32-A4)") (class "Default")
      (node (ref "IC32") (pin "6") (pinfunction "A4_6") (pintype "bidirectional"))
      (node (ref "IC36") (pin "19") (pinfunction "GPA4_19") (pintype "bidirectional"))
    )
    (net (code "230") (name "Net-(IC32-A5)") (class "Default")
      (node (ref "IC32") (pin "7") (pinfunction "A5_7") (pintype "bidirectional"))
      (node (ref "IC36") (pin "18") (pinfunction "GPA3_18") (pintype "bidirectional"))
    )
    (net (code "231") (name "Net-(IC32-A6)") (class "Default")
      (node (ref "IC32") (pin "8") (pinfunction "A6_8") (pintype "bidirectional"))
      (node (ref "IC36") (pin "17") (pinfunction "GPA2_17") (pintype "bidirectional"))
    )
    (net (code "232") (name "Net-(IC32-A7)") (class "Default")
      (node (ref "IC32") (pin "9") (pinfunction "A7_9") (pintype "bidirectional"))
      (node (ref "IC36") (pin "16") (pinfunction "GPA1_16") (pintype "bidirectional"))
    )
    (net (code "233") (name "Net-(IC32-A8)") (class "Default")
      (node (ref "IC32") (pin "10") (pinfunction "A8_10") (pintype "bidirectional"))
      (node (ref "IC36") (pin "15") (pinfunction "GPA0_15") (pintype "bidirectional"))
    )
    (net (code "234") (name "Net-(IC32-B1)") (class "Default")
      (node (ref "IC32") (pin "18") (pinfunction "B1_18") (pintype "bidirectional"))
      (node (ref "R119") (pin "1") (pinfunction "1_1") (pintype "passive"))
    )
    (net (code "235") (name "Net-(IC32-B2)") (class "Default")
      (node (ref "IC32") (pin "17") (pinfunction "B2_17") (pintype "bidirectional"))
      (node (ref "R119") (pin "2") (pinfunction "2_2") (pintype "passive"))
    )
    (net (code "236") (name "Net-(IC32-B3)") (class "Default")
      (node (ref "IC32") (pin "16") (pinfunction "B3_16") (pintype "bidirectional"))
      (node (ref "R119") (pin "3") (pinfunction "3_3") (pintype "passive"))
    )
    (net (code "237") (name "Net-(IC32-B4)") (class "Default")
      (node (ref "IC32") (pin "15") (pinfunction "B4_15") (pintype "bidirectional"))
      (node (ref "R119") (pin "4") (pinfunction "4_4") (pintype "passive"))
    )
    (net (code "238") (name "Net-(IC32-B5)") (class "Default")
      (node (ref "IC32") (pin "14") (pinfunction "B5_14") (pintype "bidirectional"))
      (node (ref "R120") (pin "1") (pinfunction "1_1") (pintype "passive"))
    )
    (net (code "239") (name "Net-(IC32-B6)") (class "Default")
      (node (ref "IC32") (pin "13") (pinfunction "B6_13") (pintype "bidirectional"))
      (node (ref "R120") (pin "2") (pinfunction "2_2") (pintype "passive"))
    )
    (net (code "240") (name "Net-(IC32-B7)") (class "Default")
      (node (ref "IC32") (pin "12") (pinfunction "B7_12") (pintype "bidirectional"))
      (node (ref "R120") (pin "3") (pinfunction "3_3") (pintype "passive"))
    )
    (net (code "241") (name "Net-(IC32-B8)") (class "Default")
      (node (ref "IC32") (pin "11") (pinfunction "B8_11") (pintype "bidirectional"))
      (node (ref "R120") (pin "4") (pinfunction "4_4") (pintype "passive"))
    )
    (net (code "242") (name "Net-(IC32-VREF_B)") (class "Default")
      (node (ref "IC32") (pin "19") (pinfunction "VREF_B_19") (pintype "power_in"))
      (node (ref "R127") (pin "1") (pinfunction "1_1") (pintype "passive"))
    )
    (net (code "243") (name "Net-(IC33-A1)") (class "Default")
      (node (ref "IC33") (pin "3") (pinfunction "A1_3") (pintype "bidirectional"))
      (node (ref "IC36") (pin "7") (pinfunction "GPB7_7") (pintype "bidirectional"))
    )
    (net (code "244") (name "Net-(IC33-A2)") (class "Default")
      (node (ref "IC33") (pin "4") (pinfunction "A2_4") (pintype "bidirectional"))
      (node (ref "IC36") (pin "6") (pinfunction "GPB6_6") (pintype "bidirectional"))
    )
    (net (code "245") (name "Net-(IC33-A3)") (class "Default")
      (node (ref "IC33") (pin "5") (pinfunction "A3_5") (pintype "bidirectional"))
      (node (ref "IC36") (pin "5") (pinfunction "GPB5_5") (pintype "bidirectional"))
    )
    (net (code "246") (name "Net-(IC33-A4)") (class "Default")
      (node (ref "IC33") (pin "6") (pinfunction "A4_6") (pintype "bidirectional"))
      (node (ref "IC36") (pin "4") (pinfunction "GPB4_4") (pintype "bidirectional"))
    )
    (net (code "247") (name "Net-(IC33-A5)") (class "Default")
      (node (ref "IC33") (pin "7") (pinfunction "A5_7") (pintype "bidirectional"))
      (node (ref "IC36") (pin "3") (pinfunction "GPB3_3") (pintype "bidirectional"))
    )
    (net (code "248") (name "Net-(IC33-A6)") (class "Default")
      (node (ref "IC33") (pin "8") (pinfunction "A6_8") (pintype "bidirectional"))
      (node (ref "IC36") (pin "2") (pinfunction "GPB2_2") (pintype "bidirectional"))
    )
    (net (code "249") (name "Net-(IC33-A7)") (class "Default")
      (node (ref "IC33") (pin "9") (pinfunction "A7_9") (pintype "bidirectional"))
      (node (ref "IC36") (pin "1") (pinfunction "GPB1_1") (pintype "bidirectional"))
    )
    (net (code "250") (name "Net-(IC33-A8)") (class "Default")
      (node (ref "IC33") (pin "10") (pinfunction "A8_10") (pintype "bidirectional"))
      (node (ref "IC36") (pin "24") (pinfunction "GPB0_24") (pintype "bidirectional"))
    )
    (net (code "251") (name "Net-(IC33-B1)") (class "Default")
      (node (ref "IC33") (pin "18") (pinfunction "B1_18") (pintype "bidirectional"))
      (node (ref "R121") (pin "1") (pinfunction "1_1") (pintype "passive"))
    )
    (net (code "252") (name "Net-(IC33-B2)") (class "Default")
      (node (ref "IC33") (pin "17") (pinfunction "B2_17") (pintype "bidirectional"))
      (node (ref "R121") (pin "2") (pinfunction "2_2") (pintype "passive"))
    )
    (net (code "253") (name "Net-(IC33-B3)") (class "Default")
      (node (ref "IC33") (pin "16") (pinfunction "B3_16") (pintype "bidirectional"))
      (node (ref "R121") (pin "3") (pinfunction "3_3") (pintype "passive"))
    )
    (net (code "254") (name "Net-(IC33-B4)") (class "Default")
      (node (ref "IC33") (pin "15") (pinfunction "B4_15") (pintype "bidirectional"))
      (node (ref "R121") (pin "4") (pinfunction "4_4") (pintype "passive"))
    )
    (net (code "255") (name "Net-(IC33-B5)") (class "Default")
      (node (ref "IC33") (pin "14") (pinfunction "B5_14") (pintype "bidirectional"))
      (node (ref "R122") (pin "1") (pinfunction "1_1") (pintype "passive"))
    )
    (net (code "256") (name "Net-(IC33-B6)") (class "Default")
      (node (ref "IC33") (pin "13") (pinfunction "B6_13") (pintype "bidirectional"))
      (node (ref "R122") (pin "2") (pinfunction "2_2") (pintype "passive"))
    )
    (net (code "257") (name "Net-(IC33-B7)") (class "Default")
      (node (ref "IC33") (pin "12") (pinfunction "B7_12") (pintype "bidirectional"))
      (node (ref "R122") (pin "3") (pinfunction "3_3") (pintype "passive"))
    )
    (net (code "258") (name "Net-(IC33-B8)") (class "Default")
      (node (ref "IC33") (pin "11") (pinfunction "B8_11") (pintype "bidirectional"))
      (node (ref "R122") (pin "4") (pinfunction "4_4") (pintype "passive"))
    )
    (net (code "259") (name "Net-(IC33-VREF_B)") (class "Default")
      (node (ref "IC33") (pin "19") (pinfunction "VREF_B_19") (pintype "power_in"))
      (node (ref "R128") (pin "1") (pinfunction "1_1") (pintype "passive"))
    )
    (net (code "260") (name "Net-(IC34-A1)") (class "Default")
      (node (ref "IC34") (pin "3") (pinfunction "A1_3") (pintype "bidirectional"))
      (node (ref "IC37") (pin "22") (pinfunction "GPA7_22") (pintype "bidirectional"))
    )
    (net (code "261") (name "Net-(IC34-A2)") (class "Default")
      (node (ref "IC34") (pin "4") (pinfunction "A2_4") (pintype "bidirectional"))
      (node (ref "IC37") (pin "21") (pinfunction "GPA6_21") (pintype "bidirectional"))
    )
    (net (code "262") (name "Net-(IC34-A3)") (class "Default")
      (node (ref "IC34") (pin "5") (pinfunction "A3_5") (pintype "bidirectional"))
      (node (ref "IC37") (pin "20") (pinfunction "GPA5_20") (pintype "bidirectional"))
    )
    (net (code "263") (name "Net-(IC34-A4)") (class "Default")
      (node (ref "IC34") (pin "6") (pinfunction "A4_6") (pintype "bidirectional"))
      (node (ref "IC37") (pin "19") (pinfunction "GPA4_19") (pintype "bidirectional"))
    )
    (net (code "264") (name "Net-(IC34-A5)") (class "Default")
      (node (ref "IC34") (pin "7") (pinfunction "A5_7") (pintype "bidirectional"))
      (node (ref "IC37") (pin "18") (pinfunction "GPA3_18") (pintype "bidirectional"))
    )
    (net (code "265") (name "Net-(IC34-A6)") (class "Default")
      (node (ref "IC34") (pin "8") (pinfunction "A6_8") (pintype "bidirectional"))
      (node (ref "IC37") (pin "17") (pinfunction "GPA2_17") (pintype "bidirectional"))
    )
    (net (code "266") (name "Net-(IC34-A7)") (class "Default")
      (node (ref "IC34") (pin "9") (pinfunction "A7_9") (pintype "bidirectional"))
      (node (ref "IC37") (pin "16") (pinfunction "GPA1_16") (pintype "bidirectional"))
    )
    (net (code "267") (name "Net-(IC34-A8)") (class "Default")
      (node (ref "IC34") (pin "10") (pinfunction "A8_10") (pintype "bidirectional"))
      (node (ref "IC37") (pin "15") (pinfunction "GPA0_15") (pintype "bidirectional"))
    )
    (net (code "268") (name "Net-(IC34-B1)") (class "Default")
      (node (ref "IC34") (pin "18") (pinfunction "B1_18") (pintype "bidirectional"))
      (node (ref "R123") (pin "1") (pinfunction "1_1") (pintype "passive"))
    )
    (net (code "269") (name "Net-(IC34-B2)") (class "Default")
      (node (ref "IC34") (pin "17") (pinfunction "B2_17") (pintype "bidirectional"))
      (node (ref "R123") (pin "2") (pinfunction "2_2") (pintype "passive"))
    )
    (net (code "270") (name "Net-(IC34-B3)") (class "Default")
      (node (ref "IC34") (pin "16") (pinfunction "B3_16") (pintype "bidirectional"))
      (node (ref "R123") (pin "3") (pinfunction "3_3") (pintype "passive"))
    )
    (net (code "271") (name "Net-(IC34-B4)") (class "Default")
      (node (ref "IC34") (pin "15") (pinfunction "B4_15") (pintype "bidirectional"))
      (node (ref "R123") (pin "4") (pinfunction "4_4") (pintype "passive"))
    )
    (net (code "272") (name "Net-(IC34-B5)") (class "Default")
      (node (ref "IC34") (pin "14") (pinfunction "B5_14") (pintype "bidirectional"))
      (node (ref "R124") (pin "1") (pinfunction "1_1") (pintype "passive"))
    )
    (net (code "273") (name "Net-(IC34-B6)") (class "Default")
      (node (ref "IC34") (pin "13") (pinfunction "B6_13") (pintype "bidirectional"))
      (node (ref "R124") (pin "2") (pinfunction "2_2") (pintype "passive"))
    )
    (net (code "274") (name "Net-(IC34-B7)") (class "Default")
      (node (ref "IC34") (pin "12") (pinfunction "B7_12") (pintype "bidirectional"))
      (node (ref "R124") (pin "3") (pinfunction "3_3") (pintype "passive"))
    )
    (net (code "275") (name "Net-(IC34-B8)") (class "Default")
      (node (ref "IC34") (pin "11") (pinfunction "B8_11") (pintype "bidirectional"))
      (node (ref "R124") (pin "4") (pinfunction "4_4") (pintype "passive"))
    )
    (net (code "276") (name "Net-(IC34-VREF_B)") (class "Default")
      (node (ref "IC34") (pin "19") (pinfunction "VREF_B_19") (pintype "power_in"))
      (node (ref "R130") (pin "1") (pinfunction "1_1") (pintype "passive"))
    )
    (net (code "277") (name "Net-(IC35-A1)") (class "Default")
      (node (ref "IC35") (pin "3") (pinfunction "A1_3") (pintype "bidirectional"))
      (node (ref "IC37") (pin "7") (pinfunction "GPB7_7") (pintype "bidirectional"))
    )
    (net (code "278") (name "Net-(IC35-A2)") (class "Default")
      (node (ref "IC35") (pin "4") (pinfunction "A2_4") (pintype "bidirectional"))
      (node (ref "IC37") (pin "6") (pinfunction "GPB6_6") (pintype "bidirectional"))
    )
    (net (code "279") (name "Net-(IC35-A3)") (class "Default")
      (node (ref "IC35") (pin "5") (pinfunction "A3_5") (pintype "bidirectional"))
      (node (ref "IC37") (pin "5") (pinfunction "GPB5_5") (pintype "bidirectional"))
    )
    (net (code "280") (name "Net-(IC35-A4)") (class "Default")
      (node (ref "IC35") (pin "6") (pinfunction "A4_6") (pintype "bidirectional"))
      (node (ref "IC37") (pin "4") (pinfunction "GPB4_4") (pintype "bidirectional"))
    )
    (net (code "281") (name "Net-(IC35-A5)") (class "Default")
      (node (ref "IC35") (pin "7") (pinfunction "A5_7") (pintype "bidirectional"))
      (node (ref "IC37") (pin "3") (pinfunction "GPB3_3") (pintype "bidirectional"))
    )
    (net (code "282") (name "Net-(IC35-A6)") (class "Default")
      (node (ref "IC35") (pin "8") (pinfunction "A6_8") (pintype "bidirectional"))
      (node (ref "IC37") (pin "2") (pinfunction "GPB2_2") (pintype "bidirectional"))
    )
    (net (code "283") (name "Net-(IC35-A7)") (class "Default")
      (node (ref "IC35") (pin "9") (pinfunction "A7_9") (pintype "bidirectional"))
      (node (ref "IC37") (pin "1") (pinfunction "GPB1_1") (pintype "bidirectional"))
    )
    (net (code "284") (name "Net-(IC35-A8)") (class "Default")
      (node (ref "IC35") (pin "10") (pinfunction "A8_10") (pintype "bidirectional"))
      (node (ref "IC37") (pin "24") (pinfunction "GPB0_24") (pintype "bidirectional"))
    )
    (net (code "285") (name "Net-(IC35-B1)") (class "Default")
      (node (ref "IC35") (pin "18") (pinfunction "B1_18") (pintype "bidirectional"))
      (node (ref "R125") (pin "1") (pinfunction "1_1") (pintype "passive"))
    )
    (net (code "286") (name "Net-(IC35-B2)") (class "Default")
      (node (ref "IC35") (pin "17") (pinfunction "B2_17") (pintype "bidirectional"))
      (node (ref "R125") (pin "2") (pinfunction "2_2") (pintype "passive"))
    )
    (net (code "287") (name "Net-(IC35-B3)") (class "Default")
      (node (ref "IC35") (pin "16") (pinfunction "B3_16") (pintype "bidirectional"))
      (node (ref "R125") (pin "3") (pinfunction "3_3") (pintype "passive"))
    )
    (net (code "288") (name "Net-(IC35-B4)") (class "Default")
      (node (ref "IC35") (pin "15") (pinfunction "B4_15") (pintype "bidirectional"))
      (node (ref "R125") (pin "4") (pinfunction "4_4") (pintype "passive"))
    )
    (net (code "289") (name "Net-(IC35-B5)") (class "Default")
      (node (ref "IC35") (pin "14") (pinfunction "B5_14") (pintype "bidirectional"))
      (node (ref "R126") (pin "1") (pinfunction "1_1") (pintype "passive"))
    )
    (net (code "290") (name "Net-(IC35-B6)") (class "Default")
      (node (ref "IC35") (pin "13") (pinfunction "B6_13") (pintype "bidirectional"))
      (node (ref "R126") (pin "2") (pinfunction "2_2") (pintype "passive"))
    )
    (net (code "291") (name "Net-(IC35-B7)") (class "Default")
      (node (ref "IC35") (pin "12") (pinfunction "B7_12") (pintype "bidirectional"))
      (node (ref "R126") (pin "3") (pinfunction "3_3") (pintype "passive"))
    )
    (net (code "292") (name "Net-(IC35-B8)") (class "Default")
      (node (ref "IC35") (pin "11") (pinfunction "B8_11") (pintype "bidirectional"))
      (node (ref "R126") (pin "4") (pinfunction "4_4") (pintype "passive"))
    )
    (net (code "293") (name "Net-(IC35-VREF_B)") (class "Default")
      (node (ref "IC35") (pin "19") (pinfunction "VREF_B_19") (pintype "power_in"))
      (node (ref "R129") (pin "1") (pinfunction "1_1") (pintype "passive"))
    )
    (net (code "294") (name "Net-(J4-Pad17)") (class "Default")
      (node (ref "J4") (pin "17") (pinfunction "17_17") (pintype "passive"))
      (node (ref "R61") (pin "1") (pinfunction "1_1") (pintype "passive"))
    )
    (net (code "295") (name "Net-(LED1-PadC)") (class "Default")
      (node (ref "LED1") (pin "C") (pinfunction "C_C") (pintype "passive"))
      (node (ref "R5") (pin "1") (pinfunction "1_1") (pintype "passive"))
    )
    (net (code "296") (name "Net-(LED2-PadC)") (class "Default")
      (node (ref "LED2") (pin "C") (pinfunction "C_C") (pintype "passive"))
      (node (ref "R10") (pin "1") (pinfunction "1_1") (pintype "passive"))
    )
    (net (code "297") (name "Net-(PCIE-DA5{slash}~{DSS}{slash}~{LED1})") (class "Default")
      (node (ref "PCIE") (pin "10") (pinfunction "DA5/~{DSS}/~{LED1}_10") (pintype "bidirectional"))
      (node (ref "R10") (pin "2") (pinfunction "2_2") (pintype "passive"))
    )
    (net (code "298") (name "Net-(PCIE-SUSCLK)") (class "Default")
      (node (ref "PCIE") (pin "68") (pinfunction "SUSCLK_68") (pintype "bidirectional"))
      (node (ref "TP-M2CLK") (pin "TP") (pinfunction "P$1_TP") (pintype "bidirectional"))
      (node (ref "X2") (pin "1") (pinfunction "CON_1") (pintype "input"))
    )
    (net (code "299") (name "Net-(R19-Pad2)") (class "Default")
      (node (ref "R19") (pin "2") (pinfunction "2_2") (pintype "passive"))
      (node (ref "R53") (pin "2") (pinfunction "2_2") (pintype "bidirectional"))
      (node (ref "R53") (pin "3") (pinfunction "3_3") (pintype "passive"))
    )
    (net (code "300") (name "Net-(R54-Pad2)") (class "Default")
      (node (ref "R54") (pin "2") (pinfunction "2_2") (pintype "bidirectional"))
      (node (ref "R54") (pin "3") (pinfunction "3_3") (pintype "passive"))
      (node (ref "R58") (pin "2") (pinfunction "2_2") (pintype "passive"))
    )
    (net (code "301") (name "Net-(R55-Pad2)") (class "Default")
      (node (ref "R55") (pin "2") (pinfunction "2_2") (pintype "bidirectional"))
      (node (ref "R55") (pin "3") (pinfunction "3_3") (pintype "passive"))
      (node (ref "R60") (pin "2") (pinfunction "2_2") (pintype "passive"))
    )
    (net (code "302") (name "Net-(R56-Pad2)") (class "Default")
      (node (ref "R56") (pin "2") (pinfunction "2_2") (pintype "bidirectional"))
      (node (ref "R56") (pin "3") (pinfunction "3_3") (pintype "passive"))
      (node (ref "R74") (pin "2") (pinfunction "2_2") (pintype "passive"))
    )
    (net (code "303") (name "Net-(T2-D)") (class "Default")
      (node (ref "C90") (pin "1") (pinfunction "1_1") (pintype "passive"))
      (node (ref "L3") (pin "1") (pinfunction "1_1") (pintype "passive"))
      (node (ref "T2") (pin "3") (pinfunction "D_3") (pintype "passive"))
    )
    (net (code "304") (name "PCIE_CLK_N") (class "Default")
      (node (ref "J1") (pin "12") (pinfunction "12_12") (pintype "passive"))
      (node (ref "PCIE") (pin "53") (pinfunction "REFCLK_N_53") (pintype "bidirectional"))
    )
    (net (code "305") (name "PCIE_CLK_P") (class "Default")
      (node (ref "J1") (pin "10") (pinfunction "10_10") (pintype "passive"))
      (node (ref "PCIE") (pin "55") (pinfunction "REFCLK_P_55") (pintype "bidirectional"))
    )
    (net (code "306") (name "PCIE_NCLKREQ") (class "Default")
      (node (ref "J1") (pin "2") (pinfunction "2_2") (pintype "passive"))
      (node (ref "PCIE") (pin "52") (pinfunction "~{CLKREQ}_52") (pintype "bidirectional"))
    )
    (net (code "307") (name "PCIE_NRST") (class "Default")
      (node (ref "J1") (pin "9") (pinfunction "9_9") (pintype "passive"))
      (node (ref "PCIE") (pin "50") (pinfunction "~{PERST}_50") (pintype "bidirectional"))
    )
    (net (code "308") (name "PCIE_NWAKE") (class "Default")
      (node (ref "J1") (pin "4") (pinfunction "4_4") (pintype "passive"))
      (node (ref "PCIE") (pin "54") (pinfunction "~{PEWAKE}_54") (pintype "bidirectional"))
    )
    (net (code "309") (name "PCIE_PWR_EN") (class "Default")
      (node (ref "IC5") (pin "7") (pinfunction "EN_7") (pintype "bidirectional"))
      (node (ref "J1") (pin "6") (pinfunction "6_6") (pintype "passive"))
      (node (ref "R11") (pin "1") (pinfunction "1_1") (pintype "passive"))
    )
    (net (code "310") (name "PCIE_RX_N") (class "Default")
      (node (ref "J1") (pin "18") (pinfunction "18_18") (pintype "passive"))
      (node (ref "PCIE") (pin "43") (pinfunction "PET_P0_43") (pintype "bidirectional"))
    )
    (net (code "311") (name "PCIE_RX_P") (class "Default")
      (node (ref "J1") (pin "16") (pinfunction "16_16") (pintype "passive"))
      (node (ref "PCIE") (pin "41") (pinfunction "PET_N0_41") (pintype "bidirectional"))
    )
    (net (code "312") (name "PCIE_TX_N") (class "Default")
      (node (ref "J1") (pin "24") (pinfunction "24_24") (pintype "passive"))
      (node (ref "PCIE") (pin "49") (pinfunction "PER_P0_49") (pintype "bidirectional"))
    )
    (net (code "313") (name "PCIE_TX_P") (class "Default")
      (node (ref "J1") (pin "22") (pinfunction "22_22") (pintype "passive"))
      (node (ref "PCIE") (pin "47") (pinfunction "PER_N0_47") (pintype "bidirectional"))
    )
    (net (code "314") (name "PGA_A_IN+") (class "Default")
      (node (ref "IC7") (pin "1") (pinfunction "IN1+_1") (pintype "input"))
      (node (ref "R43") (pin "1") (pinfunction "1_1") (pintype "passive"))
    )
    (net (code "315") (name "PGA_A_IN-") (class "Default")
      (node (ref "IC7") (pin "2") (pinfunction "IN1-_2") (pintype "input"))
      (node (ref "IC7") (pin "3") (pinfunction "IN2+_3") (pintype "input"))
      (node (ref "R44") (pin "2") (pinfunction "2_2") (pintype "passive"))
    )
    (net (code "316") (name "PGA_B_IN+") (class "Default")
      (node (ref "IC9") (pin "1") (pinfunction "IN1+_1") (pintype "input"))
      (node (ref "R24") (pin "1") (pinfunction "1_1") (pintype "passive"))
    )
    (net (code "317") (name "PGA_B_IN-") (class "Default")
      (node (ref "IC9") (pin "2") (pinfunction "IN1-_2") (pintype "input"))
      (node (ref "IC9") (pin "3") (pinfunction "IN2+_3") (pintype "input"))
      (node (ref "R42") (pin "2") (pinfunction "2_2") (pintype "passive"))
    )
    (net (code "318") (name "PMIC_ENABLE") (class "Default")
      (node (ref "J2") (pin "99") (pinfunction "99_99") (pintype "passive"))
      (node (ref "JP2") (pin "12") (pinfunction "12_12") (pintype "bidirectional"))
    )
    (net (code "319") (name "PWM") (class "Default")
      (node (ref "CON1") (pin "3") (pinfunction "P$3_3") (pintype "bidirectional"))
      (node (ref "J2") (pin "19") (pinfunction "19_19") (pintype "passive"))
    )
    (net (code "320") (name "PWR_BUT") (class "Default")
      (node (ref "J2") (pin "92") (pinfunction "92_92") (pintype "passive"))
      (node (ref "JP2") (pin "14") (pinfunction "14_14") (pintype "bidirectional"))
      (node (ref "SW1") (pin "2") (pinfunction "2_2") (pintype "passive"))
      (node (ref "TP-BTN") (pin "TP") (pinfunction "P$1_TP") (pintype "bidirectional"))
    )
    (net (code "321") (name "REFBY2") (class "Default")
      (node (ref "C71") (pin "1") (pinfunction "1_1") (pintype "passive"))
      (node (ref "IC10") (pin "3") (pinfunction "REFBY2_3") (pintype "output"))
      (node (ref "REFBY2") (pin "TP") (pinfunction "P$1_TP") (pintype "bidirectional"))
    )
    (net (code "322") (name "REFM_A") (class "Default")
      (node (ref "C70") (pin "2") (pinfunction "2_2") (pintype "passive"))
      (node (ref "IC10") (pin "32") (pinfunction "REFM_A_32") (pintype "output"))
    )
    (net (code "323") (name "REFM_B") (class "Default")
      (node (ref "C110") (pin "2") (pinfunction "2_2") (pintype "passive"))
      (node (ref "IC10") (pin "9") (pinfunction "REFM_B_9") (pintype "output"))
    )
    (net (code "324") (name "REFOUT") (class "Default")
      (node (ref "C111") (pin "1") (pinfunction "1_1") (pintype "passive"))
      (node (ref "IC10") (pin "5") (pinfunction "REFOUT_5") (pintype "output"))
      (node (ref "REFOUT") (pin "TP") (pinfunction "P$1_TP") (pintype "bidirectional"))
    )
    (net (code "325") (name "REFP_A") (class "Default")
      (node (ref "C70") (pin "1") (pinfunction "1_1") (pintype "passive"))
      (node (ref "IC10") (pin "31") (pinfunction "REFP_A_31") (pintype "output"))
    )
    (net (code "326") (name "REFP_B") (class "Default")
      (node (ref "C110") (pin "1") (pinfunction "1_1") (pintype "passive"))
      (node (ref "IC10") (pin "10") (pinfunction "REFP_B_10") (pintype "output"))
    )
    (net (code "327") (name "SCL0") (class "Default")
      (node (ref "J2") (pin "80") (pinfunction "80_80") (pintype "passive"))
      (node (ref "J3") (pin "20") (pinfunction "20_20") (pintype "passive"))
    )
    (net (code "328") (name "SCL1") (class "Default")
      (node (ref "J4") (pin "20") (pinfunction "20_20") (pintype "passive"))
      (node (ref "JP1") (pin "2") (pinfunction "2_2") (pintype "bidirectional"))
      (node (ref "R4") (pin "2") (pinfunction "2_2") (pintype "passive"))
    )
    (net (code "329") (name "SDA0") (class "Default")
      (node (ref "J2") (pin "82") (pinfunction "82_82") (pintype "passive"))
      (node (ref "J3") (pin "21") (pinfunction "21_21") (pintype "passive"))
    )
    (net (code "330") (name "SDA1") (class "Default")
      (node (ref "J4") (pin "21") (pinfunction "21_21") (pintype "passive"))
      (node (ref "JP1") (pin "4") (pinfunction "4_4") (pintype "bidirectional"))
      (node (ref "R3") (pin "2") (pinfunction "2_2") (pintype "passive"))
    )
    (net (code "331") (name "SDO_A_0") (class "Default")
      (node (ref "IC10") (pin "24") (pinfunction "SDO-0/0A_24") (pintype "output"))
      (node (ref "IC16") (pin "1") (pinfunction "1A_1") (pintype "bidirectional"))
    )
    (net (code "332") (name "SDO_B_0") (class "Default")
      (node (ref "IC10") (pin "20") (pinfunction "SDO-4/0B_20") (pintype "output"))
      (node (ref "IC16") (pin "5") (pinfunction "2A_5") (pintype "bidirectional"))
    )
    (net (code "333") (name "SD_CLK") (class "Default")
      (node (ref "J2") (pin "57") (pinfunction "57_57") (pintype "passive"))
      (node (ref "SD1") (pin "CLK") (pinfunction "CLK_CLK") (pintype "bidirectional"))
    )
    (net (code "334") (name "SD_CMD") (class "Default")
      (node (ref "J2") (pin "62") (pinfunction "62_62") (pintype "passive"))
      (node (ref "SD1") (pin "CMD") (pinfunction "CMD_CMD") (pintype "bidirectional"))
    )
    (net (code "335") (name "SD_DAT0") (class "Default")
      (node (ref "J2") (pin "63") (pinfunction "63_63") (pintype "passive"))
      (node (ref "SD1") (pin "DAT0") (pinfunction "DAT0_DAT0") (pintype "bidirectional"))
    )
    (net (code "336") (name "SD_DAT1") (class "Default")
      (node (ref "J2") (pin "67") (pinfunction "67_67") (pintype "passive"))
      (node (ref "SD1") (pin "DAT1") (pinfunction "DAT1_DAT1") (pintype "bidirectional"))
    )
    (net (code "337") (name "SD_DAT2") (class "Default")
      (node (ref "J2") (pin "69") (pinfunction "69_69") (pintype "passive"))
      (node (ref "SD1") (pin "DAT2") (pinfunction "DAT2_DAT2") (pintype "bidirectional"))
    )
    (net (code "338") (name "SD_DAT3") (class "Default")
      (node (ref "J2") (pin "61") (pinfunction "61_61") (pintype "passive"))
      (node (ref "SD1") (pin "DAT3/CD") (pinfunction "CD/DAT3_DAT3/CD") (pintype "bidirectional"))
    )
    (net (code "339") (name "SD_PWR") (class "Default")
      (node (ref "C10") (pin "1") (pinfunction "1_1") (pintype "passive"))
      (node (ref "IC1") (pin "1") (pinfunction "OUT_1") (pintype "power_in"))
      (node (ref "SD1") (pin "VDD") (pinfunction "VDD_VDD") (pintype "bidirectional"))
      (node (ref "TP-VSD") (pin "TP") (pinfunction "P$1_TP") (pintype "bidirectional"))
    )
    (net (code "340") (name "SD_PWR_ON") (class "Default")
      (node (ref "IC1") (pin "4") (pinfunction "EN_4") (pintype "bidirectional"))
      (node (ref "J2") (pin "75") (pinfunction "75_75") (pintype "passive"))
    )
    (net (code "341") (name "SPI0_CS0") (class "Default")
      (node (ref "DIO_CS") (pin "TP") (pinfunction "P$1_TP") (pintype "bidirectional"))
      (node (ref "IC36") (pin "9") (pinfunction "~{CS}_9") (pintype "input"))
      (node (ref "R29") (pin "1") (pinfunction "1_1") (pintype "passive"))
    )
    (net (code "342") (name "SPI0_CS1") (class "Default")
      (node (ref "IC37") (pin "9") (pinfunction "~{CS}_9") (pintype "input"))
      (node (ref "R30") (pin "1") (pinfunction "1_1") (pintype "passive"))
    )
    (net (code "343") (name "SPI0_MISO") (class "Default")
      (node (ref "IC36") (pin "12") (pinfunction "SO_12") (pintype "output"))
      (node (ref "IC37") (pin "12") (pinfunction "SO_12") (pintype "output"))
      (node (ref "R27") (pin "1") (pinfunction "1_1") (pintype "passive"))
    )
    (net (code "344") (name "SPI0_MOSI") (class "Default")
      (node (ref "IC22") (pin "15") (pinfunction "DIN_15") (pintype "bidirectional"))
      (node (ref "IC36") (pin "11") (pinfunction "SI_11") (pintype "input"))
      (node (ref "IC37") (pin "11") (pinfunction "SI_11") (pintype "input"))
      (node (ref "R28") (pin "1") (pinfunction "1_1") (pintype "passive"))
    )
    (net (code "345") (name "SPI0_SCK") (class "Default")
      (node (ref "IC22") (pin "16") (pinfunction "SCLK_16") (pintype "bidirectional"))
      (node (ref "IC36") (pin "10") (pinfunction "SCK_10") (pintype "input"))
      (node (ref "IC37") (pin "10") (pinfunction "SCK_10") (pintype "input"))
      (node (ref "R26") (pin "1") (pinfunction "1_1") (pintype "passive"))
    )
    (net (code "346") (name "SPI1_CS0") (class "Default")
      (node (ref "IC10") (pin "14") (pinfunction "~{CS}_14") (pintype "input"))
      (node (ref "R15") (pin "1") (pinfunction "1_1") (pintype "passive"))
      (node (ref "R32") (pin "1") (pinfunction "1_1") (pintype "passive"))
      (node (ref "SPI1_CS0") (pin "TP") (pinfunction "P$1_TP") (pintype "bidirectional"))
    )
    (net (code "347") (name "SPI1_CS1") (class "Default")
      (node (ref "IC7") (pin "11") (pinfunction "~{CS}_11") (pintype "bidirectional"))
      (node (ref "R33") (pin "1") (pinfunction "1_1") (pintype "passive"))
    )
    (net (code "348") (name "SPI1_CS2") (class "Default")
      (node (ref "IC9") (pin "11") (pinfunction "~{CS}_11") (pintype "bidirectional"))
      (node (ref "R34") (pin "1") (pinfunction "1_1") (pintype "passive"))
    )
    (net (code "349") (name "SPI1_MISO") (class "Default")
      (node (ref "IC16") (pin "2") (pinfunction "1B_2") (pintype "bidirectional"))
      (node (ref "IC16") (pin "6") (pinfunction "2B_6") (pintype "bidirectional"))
      (node (ref "IC7") (pin "8") (pinfunction "SDO_8") (pintype "bidirectional"))
      (node (ref "IC9") (pin "8") (pinfunction "SDO_8") (pintype "bidirectional"))
      (node (ref "R18") (pin "1") (pinfunction "1_1") (pintype "passive"))
    )
    (net (code "350") (name "SPI1_MOSI") (class "Default")
      (node (ref "IC10") (pin "15") (pinfunction "SDI_15") (pintype "input"))
      (node (ref "IC7") (pin "9") (pinfunction "SDI_9") (pintype "bidirectional"))
      (node (ref "IC9") (pin "9") (pinfunction "SDI_9") (pintype "bidirectional"))
      (node (ref "R17") (pin "1") (pinfunction "1_1") (pintype "passive"))
    )
    (net (code "351") (name "SPI1_SCK") (class "Default")
      (node (ref "IC10") (pin "16") (pinfunction "SCLK_16") (pintype "input"))
      (node (ref "IC7") (pin "10") (pinfunction "SCK_10") (pintype "bidirectional"))
      (node (ref "IC9") (pin "10") (pinfunction "SCK_10") (pintype "bidirectional"))
      (node (ref "R25") (pin "1") (pinfunction "1_1") (pintype "passive"))
    )
    (net (code "352") (name "SYNC_OUT") (class "Default")
      (node (ref "J2") (pin "18") (pinfunction "18_18") (pintype "passive"))
      (node (ref "JP2") (pin "6") (pinfunction "6_6") (pintype "bidirectional"))
    )
    (net (code "353") (name "TACHO") (class "Default")
      (node (ref "CON1") (pin "1") (pinfunction "P$1_1") (pintype "bidirectional"))
      (node (ref "J2") (pin "16") (pinfunction "16_16") (pintype "passive"))
    )
    (net (code "354") (name "TR0_TAP") (class "Default")
      (node (ref "ETH1") (pin "VC1") (pinfunction "VC1_VC1") (pintype "bidirectional"))
      (node (ref "JP4") (pin "3") (pinfunction "3_3") (pintype "bidirectional"))
    )
    (net (code "355") (name "TR1_TAP") (class "Default")
      (node (ref "ETH1") (pin "VC2") (pinfunction "VC2_VC2") (pintype "bidirectional"))
      (node (ref "JP4") (pin "1") (pinfunction "1_1") (pintype "bidirectional"))
    )
    (net (code "356") (name "TR2_TAP") (class "Default")
      (node (ref "ETH1") (pin "VC3") (pinfunction "VC3_VC3") (pintype "bidirectional"))
      (node (ref "JP4") (pin "2") (pinfunction "2_2") (pintype "bidirectional"))
    )
    (net (code "357") (name "TR3_TAP") (class "Default")
      (node (ref "ETH1") (pin "VC4") (pinfunction "VC4_VC4") (pintype "bidirectional"))
      (node (ref "JP4") (pin "4") (pinfunction "4_4") (pintype "bidirectional"))
    )
    (net (code "358") (name "TRD0_N") (class "Default")
      (node (ref "D2") (pin "2") (pinfunction "D1-_2") (pintype "bidirectional"))
      (node (ref "D2") (pin "9") (pinfunction "D1-_9") (pintype "bidirectional"))
      (node (ref "ETH1") (pin "TD1-") (pinfunction "TD1-_TD1-") (pintype "bidirectional"))
      (node (ref "J2") (pin "10") (pinfunction "10_10") (pintype "passive"))
    )
    (net (code "359") (name "TRD0_P") (class "Default")
      (node (ref "D2") (pin "1") (pinfunction "D1+_1") (pintype "bidirectional"))
      (node (ref "D2") (pin "10") (pinfunction "D1+_10") (pintype "bidirectional"))
      (node (ref "ETH1") (pin "TD1+") (pinfunction "TD1+_TD1+") (pintype "bidirectional"))
      (node (ref "J2") (pin "12") (pinfunction "12_12") (pintype "passive"))
    )
    (net (code "360") (name "TRD1_N") (class "Default")
      (node (ref "D2") (pin "4") (pinfunction "D2+_4") (pintype "bidirectional"))
      (node (ref "D2") (pin "7") (pinfunction "D2+_7") (pintype "bidirectional"))
      (node (ref "ETH1") (pin "TD2-") (pinfunction "TD2-_TD2-") (pintype "bidirectional"))
      (node (ref "J2") (pin "6") (pinfunction "6_6") (pintype "passive"))
    )
    (net (code "361") (name "TRD1_P") (class "Default")
      (node (ref "D2") (pin "5") (pinfunction "D2-_5") (pintype "bidirectional"))
      (node (ref "D2") (pin "6") (pinfunction "D2-_6") (pintype "bidirectional"))
      (node (ref "ETH1") (pin "TD2+") (pinfunction "TD2+_TD2+") (pintype "bidirectional"))
      (node (ref "J2") (pin "4") (pinfunction "4_4") (pintype "passive"))
    )
    (net (code "362") (name "TRD2_N") (class "Default")
      (node (ref "D1") (pin "4") (pinfunction "D2+_4") (pintype "bidirectional"))
      (node (ref "D1") (pin "7") (pinfunction "D2+_7") (pintype "bidirectional"))
      (node (ref "ETH1") (pin "TD3-") (pinfunction "TD3-_TD3-") (pintype "bidirectional"))
      (node (ref "J2") (pin "9") (pinfunction "9_9") (pintype "passive"))
    )
    (net (code "363") (name "TRD2_P") (class "Default")
      (node (ref "D1") (pin "5") (pinfunction "D2-_5") (pintype "bidirectional"))
      (node (ref "D1") (pin "6") (pinfunction "D2-_6") (pintype "bidirectional"))
      (node (ref "ETH1") (pin "TD3+") (pinfunction "TD3+_TD3+") (pintype "bidirectional"))
      (node (ref "J2") (pin "11") (pinfunction "11_11") (pintype "passive"))
    )
    (net (code "364") (name "TRD3_N") (class "Default")
      (node (ref "D1") (pin "2") (pinfunction "D1-_2") (pintype "bidirectional"))
      (node (ref "D1") (pin "9") (pinfunction "D1-_9") (pintype "bidirectional"))
      (node (ref "ETH1") (pin "TD4-") (pinfunction "TD4-_TD4-") (pintype "bidirectional"))
      (node (ref "J2") (pin "5") (pinfunction "5_5") (pintype "passive"))
    )
    (net (code "365") (name "TRD3_P") (class "Default")
      (node (ref "D1") (pin "1") (pinfunction "D1+_1") (pintype "bidirectional"))
      (node (ref "D1") (pin "10") (pinfunction "D1+_10") (pintype "bidirectional"))
      (node (ref "ETH1") (pin "TD4+") (pinfunction "TD4+_TD4+") (pintype "bidirectional"))
      (node (ref "J2") (pin "3") (pinfunction "3_3") (pintype "passive"))
    )
    (net (code "366") (name "USB2_N") (class "Default")
      (node (ref "J1") (pin "3") (pinfunction "3_3") (pintype "passive"))
      (node (ref "USBC") (pin "A7") (pinfunction "D-1_A7") (pintype "passive"))
      (node (ref "USBC") (pin "B7") (pinfunction "D-2_B7") (pintype "passive"))
    )
    (net (code "367") (name "USB2_P") (class "Default")
      (node (ref "J1") (pin "5") (pinfunction "5_5") (pintype "passive"))
      (node (ref "USBC") (pin "A6") (pinfunction "D+1_A6") (pintype "passive"))
      (node (ref "USBC") (pin "B6") (pinfunction "D+2_B6") (pintype "passive"))
    )
    (net (code "368") (name "USB3-0-D_N") (class "Default")
      (node (ref "J1") (pin "36") (pinfunction "36_36") (pintype "passive"))
      (node (ref "USB3") (pin "2") (pinfunction "D-_2") (pintype "passive"))
    )
    (net (code "369") (name "USB3-0-D_P") (class "Default")
      (node (ref "J1") (pin "34") (pinfunction "34_34") (pintype "passive"))
      (node (ref "USB3") (pin "3") (pinfunction "D+_3") (pintype "passive"))
    )
    (net (code "370") (name "USB3-0-RX_N") (class "Default")
      (node (ref "J1") (pin "28") (pinfunction "28_28") (pintype "passive"))
      (node (ref "USB3") (pin "5") (pinfunction "STDA_SSRX-_5") (pintype "passive"))
    )
    (net (code "371") (name "USB3-0-RX_P") (class "Default")
      (node (ref "J1") (pin "30") (pinfunction "30_30") (pintype "passive"))
      (node (ref "USB3") (pin "6") (pinfunction "STDA_SSRX+_6") (pintype "passive"))
    )
    (net (code "372") (name "USB3-0-TX_N") (class "Default")
      (node (ref "J1") (pin "40") (pinfunction "40_40") (pintype "passive"))
      (node (ref "USB3") (pin "8") (pinfunction "STDA_SSTX-_8") (pintype "passive"))
    )
    (net (code "373") (name "USB3-0-TX_P") (class "Default")
      (node (ref "J1") (pin "42") (pinfunction "42_42") (pintype "passive"))
      (node (ref "USB3") (pin "9") (pinfunction "STDA_SSTX+_9") (pintype "passive"))
    )
    (net (code "374") (name "USB3-1-D_N") (class "Default")
      (node (ref "J1") (pin "65") (pinfunction "65_65") (pintype "passive"))
      (node (ref "USB3") (pin "11") (pinfunction "D-_11") (pintype "passive"))
    )
    (net (code "375") (name "USB3-1-D_P") (class "Default")
      (node (ref "J1") (pin "63") (pinfunction "63_63") (pintype "passive"))
      (node (ref "USB3") (pin "12") (pinfunction "D+_12") (pintype "passive"))
    )
    (net (code "376") (name "USB3-1-RX_N") (class "Default")
      (node (ref "J1") (pin "57") (pinfunction "57_57") (pintype "passive"))
      (node (ref "USB3") (pin "14") (pinfunction "STDA_SSRX-_14") (pintype "passive"))
    )
    (net (code "377") (name "USB3-1-RX_P") (class "Default")
      (node (ref "J1") (pin "59") (pinfunction "59_59") (pintype "passive"))
      (node (ref "USB3") (pin "15") (pinfunction "STDA_SSRX+_15") (pintype "passive"))
    )
    (net (code "378") (name "USB3-1-TX_N") (class "Default")
      (node (ref "J1") (pin "69") (pinfunction "69_69") (pintype "passive"))
      (node (ref "USB3") (pin "17") (pinfunction "STDA_SSTX-_17") (pintype "passive"))
    )
    (net (code "379") (name "USB3-1-TX_P") (class "Default")
      (node (ref "J1") (pin "71") (pinfunction "71_71") (pintype "passive"))
      (node (ref "USB3") (pin "18") (pinfunction "STDA_SSTX+_18") (pintype "passive"))
    )
    (net (code "380") (name "USBOTG_ID") (class "Default")
      (node (ref "J1") (pin "1") (pinfunction "1_1") (pintype "passive"))
      (node (ref "JP2") (pin "10") (pinfunction "10_10") (pintype "bidirectional"))
    )
    (net (code "381") (name "VBAT") (class "Default")
      (node (ref "BT1") (pin "P1") (pinfunction "+_P1") (pintype "passive"))
      (node (ref "BT1") (pin "P2") (pinfunction "+_P2") (pintype "passive"))
      (node (ref "J2") (pin "76") (pinfunction "76_76") (pintype "passive"))
      (node (ref "TP-VBAT") (pin "TP") (pinfunction "P$1_TP") (pintype "bidirectional"))
    )
    (net (code "382") (name "VBUS") (class "Default")
      (node (ref "C6") (pin "1") (pinfunction "1_1") (pintype "passive"))
      (node (ref "C7") (pin "1") (pinfunction "1_1") (pintype "passive"))
      (node (ref "C8") (pin "1") (pinfunction "1_1") (pintype "passive"))
      (node (ref "IC2") (pin "6") (pinfunction "OUT_6") (pintype "bidirectional"))
      (node (ref "TP-VBUS") (pin "TP") (pinfunction "P$1_TP") (pintype "bidirectional"))
      (node (ref "USB3") (pin "1") (pinfunction "VBUS_1") (pintype "passive"))
      (node (ref "USB3") (pin "10") (pinfunction "VBUS_10") (pintype "passive"))
    )
    (net (code "383") (name "VBUS_EN") (class "Default")
      (node (ref "IC2") (pin "3") (pinfunction "EN_3") (pintype "bidirectional"))
      (node (ref "J1") (pin "11") (pinfunction "11_11") (pintype "passive"))
    )
    (net (code "384") (name "VFB_12VN") (class "Default")
      (node (ref "C106") (pin "2") (pinfunction "2_2") (pintype "passive"))
      (node (ref "IC15") (pin "7") (pinfunction "FBN_7") (pintype "input"))
      (node (ref "R56") (pin "1") (pinfunction "1_1") (pintype "passive"))
      (node (ref "R76") (pin "1") (pinfunction "1_1") (pintype "passive"))
      (node (ref "VFB12VN") (pin "TP") (pinfunction "P$1_TP") (pintype "bidirectional"))
    )
    (net (code "385") (name "VFB_12VP") (class "Default")
      (node (ref "C107") (pin "1") (pinfunction "1_1") (pintype "passive"))
      (node (ref "IC15") (pin "9") (pinfunction "FBP_9") (pintype "input"))
      (node (ref "R55") (pin "1") (pinfunction "1_1") (pintype "passive"))
      (node (ref "R73") (pin "1") (pinfunction "1_1") (pintype "passive"))
      (node (ref "VFB12VP") (pin "TP") (pinfunction "P$1_TP") (pintype "bidirectional"))
    )
    (net (code "386") (name "VFB_14VN") (class "Default")
      (node (ref "C101") (pin "2") (pinfunction "2_2") (pintype "passive"))
      (node (ref "IC14") (pin "16") (pinfunction "FBN_16") (pintype "input"))
      (node (ref "R54") (pin "1") (pinfunction "1_1") (pintype "passive"))
      (node (ref "R59") (pin "1") (pinfunction "1_1") (pintype "passive"))
      (node (ref "TP_VFB_14VN") (pin "TP") (pinfunction "P$1_TP") (pintype "bidirectional"))
    )
    (net (code "387") (name "VFB_14VP") (class "Default")
      (node (ref "C100") (pin "2") (pinfunction "2_2") (pintype "passive"))
      (node (ref "IC14") (pin "22") (pinfunction "FBP_22") (pintype "input"))
      (node (ref "R53") (pin "1") (pinfunction "1_1") (pintype "passive"))
      (node (ref "R57") (pin "1") (pinfunction "1_1") (pintype "passive"))
      (node (ref "TP_VFB_14VP") (pin "TP") (pinfunction "P$1_TP") (pintype "bidirectional"))
    )
    (net (code "388") (name "VOCM_A") (class "Default")
      (node (ref "IC7") (pin "21") (pinfunction "VOCM_21") (pintype "output"))
      (node (ref "R51") (pin "2") (pinfunction "2_2") (pintype "passive"))
      (node (ref "VOCMA") (pin "TP") (pinfunction "P$1_TP") (pintype "bidirectional"))
    )
    (net (code "389") (name "VOCM_B") (class "Default")
      (node (ref "IC9") (pin "21") (pinfunction "VOCM_21") (pintype "output"))
      (node (ref "R52") (pin "1") (pinfunction "1_1") (pintype "passive"))
      (node (ref "VCOMB") (pin "TP") (pinfunction "P$1_TP") (pintype "bidirectional"))
    )
    (net (code "390") (name "VREF_ADC") (class "Default")
      (node (ref "C46") (pin "1") (pinfunction "1_1") (pintype "passive"))
      (node (ref "C72") (pin "1") (pinfunction "1_1") (pintype "passive"))
      (node (ref "C73") (pin "1") (pinfunction "1_1") (pintype "passive"))
      (node (ref "IC13") (pin "1") (pinfunction "OUT_1") (pintype "output"))
      (node (ref "IC13") (pin "4") (pinfunction "-IN_4") (pintype "input"))
      (node (ref "IC7") (pin "23") (pinfunction "AVDD_23") (pintype "power_in"))
      (node (ref "IC9") (pin "23") (pinfunction "AVDD_23") (pintype "power_in"))
      (node (ref "R49") (pin "3") (pinfunction "3_3") (pintype "passive"))
      (node (ref "TP9") (pin "TP") (pinfunction "P$1_TP") (pintype "bidirectional"))
    )
    (net (code "391") (name "VREF_ADC_RAW") (class "Default")
      (node (ref "C48") (pin "1") (pinfunction "1_1") (pintype "passive"))
      (node (ref "IC12") (pin "2") (pinfunction "VREF_2") (pintype "bidirectional"))
      (node (ref "IC13") (pin "3") (pinfunction "+IN_3") (pintype "input"))
      (node (ref "VREFR") (pin "TP") (pinfunction "P$1_TP") (pintype "bidirectional"))
    )
    (net (code "392") (name "VREF_ADC{slash}2") (class "Default")
      (node (ref "C75") (pin "1") (pinfunction "1_1") (pintype "passive"))
      (node (ref "IC11") (pin "1") (pinfunction "OUT_1") (pintype "output"))
      (node (ref "IC11") (pin "4") (pinfunction "-IN_4") (pintype "input"))
      (node (ref "R51") (pin "1") (pinfunction "1_1") (pintype "passive"))
      (node (ref "R52") (pin "2") (pinfunction "2_2") (pintype "passive"))
      (node (ref "REF/2") (pin "TP") (pinfunction "P$1_TP") (pintype "bidirectional"))
    )
    (net (code "393") (name "VREF_DAC") (class "Default")
      (node (ref "C125") (pin "1") (pinfunction "1_1") (pintype "passive"))
      (node (ref "IC23") (pin "1") (pinfunction "OUT_1") (pintype "output"))
      (node (ref "IC23") (pin "4") (pinfunction "-IN_4") (pintype "input"))
      (node (ref "R100") (pin "1") (pinfunction "1_1") (pintype "passive"))
      (node (ref "R104") (pin "1") (pinfunction "1_1") (pintype "passive"))
      (node (ref "R108") (pin "1") (pinfunction "1_1") (pintype "passive"))
      (node (ref "R112") (pin "1") (pinfunction "1_1") (pintype "passive"))
      (node (ref "R116") (pin "1") (pinfunction "1_1") (pintype "passive"))
      (node (ref "R88") (pin "1") (pinfunction "1_1") (pintype "passive"))
      (node (ref "R92") (pin "1") (pinfunction "1_1") (pintype "passive"))
      (node (ref "R96") (pin "1") (pinfunction "1_1") (pintype "passive"))
    )
    (net (code "394") (name "VREF_DAC_OUT") (class "Default")
      (node (ref "C124") (pin "1") (pinfunction "1_1") (pintype "passive"))
      (node (ref "IC22") (pin "8") (pinfunction "VREF_IO_8") (pintype "power_in"))
      (node (ref "IC23") (pin "3") (pinfunction "+IN_3") (pintype "input"))
      (node (ref "VREF_DAC") (pin "TP") (pinfunction "P$1_TP") (pintype "bidirectional"))
    )
    (net (code "395") (name "VREF_TPS") (class "Default")
      (node (ref "C99") (pin "2") (pinfunction "2_2") (pintype "passive"))
      (node (ref "IC14") (pin "17") (pinfunction "VREF_17") (pintype "input"))
      (node (ref "R58") (pin "1") (pinfunction "1_1") (pintype "passive"))
      (node (ref "TP_VREF_TPS") (pin "TP") (pinfunction "P$1_TP") (pintype "bidirectional"))
    )
    (net (code "396") (name "V_OUT_REF") (class "Default")
      (node (ref "C153") (pin "1") (pinfunction "1_1") (pintype "passive"))
      (node (ref "C154") (pin "1") (pinfunction "1_1") (pintype "passive"))
      (node (ref "C157") (pin "1") (pinfunction "1_1") (pintype "passive"))
      (node (ref "C158") (pin "1") (pinfunction "1_1") (pintype "passive"))
      (node (ref "C161") (pin "1") (pinfunction "1_1") (pintype "passive"))
      (node (ref "C162") (pin "1") (pinfunction "1_1") (pintype "passive"))
      (node (ref "C165") (pin "1") (pinfunction "1_1") (pintype "passive"))
      (node (ref "C166") (pin "1") (pinfunction "1_1") (pintype "passive"))
      (node (ref "DIO_VREF") (pin "TP") (pinfunction "P$1_TP") (pintype "bidirectional"))
      (node (ref "IC38") (pin "2") (pinfunction "1B_2") (pintype "bidirectional"))
      (node (ref "IC38") (pin "6") (pinfunction "2B_6") (pintype "bidirectional"))
      (node (ref "R127") (pin "2") (pinfunction "2_2") (pintype "passive"))
      (node (ref "R128") (pin "2") (pinfunction "2_2") (pintype "passive"))
      (node (ref "R129") (pin "2") (pinfunction "2_2") (pintype "passive"))
      (node (ref "R130") (pin "2") (pinfunction "2_2") (pintype "passive"))
    )
    (net (code "397") (name "WL_NDIS") (class "Default")
      (node (ref "J2") (pin "89") (pinfunction "89_89") (pintype "passive"))
      (node (ref "JP3") (pin "1") (pinfunction "1_1") (pintype "bidirectional"))
    )
    (net (code "398") (name "unconnected-(HDMI1-CEC-Pad14)") (class "Default")
      (node (ref "HDMI1") (pin "14") (pinfunction "CEC_14") (pintype "passive"))
    )
    (net (code "399") (name "unconnected-(HDMI2-CEC-Pad14)") (class "Default")
      (node (ref "HDMI2") (pin "14") (pinfunction "CEC_14") (pintype "passive"))
    )
    (net (code "400") (name "unconnected-(IC1-NFLG-Pad3)") (class "Default")
      (node (ref "IC1") (pin "3") (pinfunction "NFLG_3") (pintype "bidirectional"))
    )
    (net (code "401") (name "unconnected-(IC2-~{FAULT}-Pad4)") (class "Default")
      (node (ref "IC2") (pin "4") (pinfunction "~{FAULT}_4") (pintype "bidirectional"))
    )
    (net (code "402") (name "unconnected-(IC5-NC-Pad5)") (class "Default")
      (node (ref "IC5") (pin "5") (pinfunction "NC_5") (pintype "no_connect"))
    )
    (net (code "403") (name "unconnected-(IC5-PG-Pad2)") (class "Default")
      (node (ref "IC5") (pin "2") (pinfunction "PG_2") (pintype "bidirectional"))
    )
    (net (code "404") (name "unconnected-(IC7-GPIO3-Pad15)") (class "Default")
      (node (ref "IC7") (pin "15") (pinfunction "GPIO3_15") (pintype "bidirectional"))
    )
    (net (code "405") (name "unconnected-(IC7-GPIO4-Pad14)") (class "Default")
      (node (ref "IC7") (pin "14") (pinfunction "GPIO4_14") (pintype "bidirectional"))
    )
    (net (code "406") (name "unconnected-(IC7-GPIO5-Pad13)") (class "Default")
      (node (ref "IC7") (pin "13") (pinfunction "GPIO5_13") (pintype "bidirectional"))
    )
    (net (code "407") (name "unconnected-(IC7-GPIO6-Pad12)") (class "Default")
      (node (ref "IC7") (pin "12") (pinfunction "GPIO6_12") (pintype "bidirectional"))
    )
    (net (code "408") (name "unconnected-(IC9-GPIO3-Pad15)") (class "Default")
      (node (ref "IC9") (pin "15") (pinfunction "GPIO3_15") (pintype "bidirectional"))
    )
    (net (code "409") (name "unconnected-(IC9-GPIO4-Pad14)") (class "Default")
      (node (ref "IC9") (pin "14") (pinfunction "GPIO4_14") (pintype "bidirectional"))
    )
    (net (code "410") (name "unconnected-(IC9-GPIO5-Pad13)") (class "Default")
      (node (ref "IC9") (pin "13") (pinfunction "GPIO5_13") (pintype "bidirectional"))
    )
    (net (code "411") (name "unconnected-(IC9-GPIO6-Pad12)") (class "Default")
      (node (ref "IC9") (pin "12") (pinfunction "GPIO6_12") (pintype "bidirectional"))
    )
    (net (code "412") (name "unconnected-(IC10-SDO-1{slash}1A-Pad23)") (class "Default")
      (node (ref "IC10") (pin "23") (pinfunction "SDO-1/1A_23") (pintype "output"))
    )
    (net (code "413") (name "unconnected-(IC10-SDO-2{slash}2A-Pad22)") (class "Default")
      (node (ref "IC10") (pin "22") (pinfunction "SDO-2/2A_22") (pintype "output"))
    )
    (net (code "414") (name "unconnected-(IC10-SDO-3{slash}3A-Pad21)") (class "Default")
      (node (ref "IC10") (pin "21") (pinfunction "SDO-3/3A_21") (pintype "output"))
    )
    (net (code "415") (name "unconnected-(IC10-SDO-5{slash}1B-Pad19)") (class "Default")
      (node (ref "IC10") (pin "19") (pinfunction "SDO-5/1B_19") (pintype "output"))
    )
    (net (code "416") (name "unconnected-(IC10-SDO-6{slash}2B-Pad18)") (class "Default")
      (node (ref "IC10") (pin "18") (pinfunction "SDO-6/2B_18") (pintype "output"))
    )
    (net (code "417") (name "unconnected-(IC10-SDO-7{slash}3B-Pad17)") (class "Default")
      (node (ref "IC10") (pin "17") (pinfunction "SDO-7/3B_17") (pintype "output"))
    )
    (net (code "418") (name "unconnected-(IC36-INTA-Pad14)") (class "Default")
      (node (ref "IC36") (pin "14") (pinfunction "INTA_14") (pintype "output"))
    )
    (net (code "419") (name "unconnected-(IC37-INTA-Pad14)") (class "Default")
      (node (ref "IC37") (pin "14") (pinfunction "INTA_14") (pintype "output"))
    )
    (net (code "420") (name "unconnected-(J2-Pad64)") (class "Default")
      (node (ref "J2") (pin "64") (pinfunction "64_64") (pintype "passive"))
    )
    (net (code "421") (name "unconnected-(J2-Pad68)") (class "Default")
      (node (ref "J2") (pin "68") (pinfunction "68_68") (pintype "passive"))
    )
    (net (code "422") (name "unconnected-(J2-Pad70)") (class "Default")
      (node (ref "J2") (pin "70") (pinfunction "70_70") (pintype "passive"))
    )
    (net (code "423") (name "unconnected-(J2-Pad72)") (class "Default")
      (node (ref "J2") (pin "72") (pinfunction "72_72") (pintype "passive"))
    )
    (net (code "424") (name "unconnected-(J2-Pad73)") (class "Default")
      (node (ref "J2") (pin "73") (pinfunction "73_73") (pintype "passive"))
    )
    (net (code "425") (name "unconnected-(J4-Pad18)") (class "Default")
      (node (ref "J4") (pin "18") (pinfunction "18_18") (pintype "passive"))
    )
    (net (code "426") (name "unconnected-(JP2-Pad8)") (class "Default")
      (node (ref "JP2") (pin "8") (pinfunction "8_8") (pintype "bidirectional"))
    )
    (net (code "427") (name "unconnected-(PCIE-DEVSLP-Pad38)") (class "Default")
      (node (ref "PCIE") (pin "38") (pinfunction "DEVSLP_38") (pintype "bidirectional"))
    )
    (net (code "428") (name "unconnected-(PCIE-NC1-Pad58)") (class "Default")
      (node (ref "PCIE") (pin "58") (pinfunction "NC1_58") (pintype "bidirectional"))
    )
    (net (code "429") (name "unconnected-(PCIE-NC2-Pad56)") (class "Default")
      (node (ref "PCIE") (pin "56") (pinfunction "NC2_56") (pintype "bidirectional"))
    )
    (net (code "430") (name "unconnected-(PCIE-NC3-Pad48)") (class "Default")
      (node (ref "PCIE") (pin "48") (pinfunction "NC3_48") (pintype "bidirectional"))
    )
    (net (code "431") (name "unconnected-(PCIE-NC4-Pad46)") (class "Default")
      (node (ref "PCIE") (pin "46") (pinfunction "NC4_46") (pintype "bidirectional"))
    )
    (net (code "432") (name "unconnected-(PCIE-NC5-Pad44)") (class "Default")
      (node (ref "PCIE") (pin "44") (pinfunction "NC5_44") (pintype "bidirectional"))
    )
    (net (code "433") (name "unconnected-(PCIE-NC6-Pad42)") (class "Default")
      (node (ref "PCIE") (pin "42") (pinfunction "NC6_42") (pintype "bidirectional"))
    )
    (net (code "434") (name "unconnected-(PCIE-NC7-Pad40)") (class "Default")
      (node (ref "PCIE") (pin "40") (pinfunction "NC7_40") (pintype "bidirectional"))
    )
    (net (code "435") (name "unconnected-(PCIE-NC8-Pad36)") (class "Default")
      (node (ref "PCIE") (pin "36") (pinfunction "NC8_36") (pintype "bidirectional"))
    )
    (net (code "436") (name "unconnected-(PCIE-NC9-Pad34)") (class "Default")
      (node (ref "PCIE") (pin "34") (pinfunction "NC9_34") (pintype "bidirectional"))
    )
    (net (code "437") (name "unconnected-(PCIE-NC10-Pad32)") (class "Default")
      (node (ref "PCIE") (pin "32") (pinfunction "NC10_32") (pintype "bidirectional"))
    )
    (net (code "438") (name "unconnected-(PCIE-NC11-Pad30)") (class "Default")
      (node (ref "PCIE") (pin "30") (pinfunction "NC11_30") (pintype "bidirectional"))
    )
    (net (code "439") (name "unconnected-(PCIE-NC12-Pad28)") (class "Default")
      (node (ref "PCIE") (pin "28") (pinfunction "NC12_28") (pintype "bidirectional"))
    )
    (net (code "440") (name "unconnected-(PCIE-NC13-Pad26)") (class "Default")
      (node (ref "PCIE") (pin "26") (pinfunction "NC13_26") (pintype "bidirectional"))
    )
    (net (code "441") (name "unconnected-(PCIE-NC14-Pad24)") (class "Default")
      (node (ref "PCIE") (pin "24") (pinfunction "NC14_24") (pintype "bidirectional"))
    )
    (net (code "442") (name "unconnected-(PCIE-NC15-Pad22)") (class "Default")
      (node (ref "PCIE") (pin "22") (pinfunction "NC15_22") (pintype "bidirectional"))
    )
    (net (code "443") (name "unconnected-(PCIE-NC16-Pad20)") (class "Default")
      (node (ref "PCIE") (pin "20") (pinfunction "NC16_20") (pintype "bidirectional"))
    )
    (net (code "444") (name "unconnected-(PCIE-NC17-Pad8)") (class "Default")
      (node (ref "PCIE") (pin "8") (pinfunction "NC17_8") (pintype "bidirectional"))
    )
    (net (code "445") (name "unconnected-(PCIE-NC18-Pad6)") (class "Default")
      (node (ref "PCIE") (pin "6") (pinfunction "NC18_6") (pintype "bidirectional"))
    )
    (net (code "446") (name "unconnected-(PCIE-NC19-Pad67)") (class "Default")
      (node (ref "PCIE") (pin "67") (pinfunction "NC19_67") (pintype "bidirectional"))
    )
    (net (code "447") (name "unconnected-(PCIE-PEDET-Pad69)") (class "Default")
      (node (ref "PCIE") (pin "69") (pinfunction "PEDET_69") (pintype "bidirectional"))
    )
    (net (code "448") (name "unconnected-(PCIE-PER_N1-Pad35)") (class "Default")
      (node (ref "PCIE") (pin "35") (pinfunction "PER_N1_35") (pintype "bidirectional"))
    )
    (net (code "449") (name "unconnected-(PCIE-PER_N2-Pad23)") (class "Default")
      (node (ref "PCIE") (pin "23") (pinfunction "PER_N2_23") (pintype "bidirectional"))
    )
    (net (code "450") (name "unconnected-(PCIE-PER_N3-Pad11)") (class "Default")
      (node (ref "PCIE") (pin "11") (pinfunction "PER_N3_11") (pintype "bidirectional"))
    )
    (net (code "451") (name "unconnected-(PCIE-PER_P1-Pad37)") (class "Default")
      (node (ref "PCIE") (pin "37") (pinfunction "PER_P1_37") (pintype "bidirectional"))
    )
    (net (code "452") (name "unconnected-(PCIE-PER_P2-Pad25)") (class "Default")
      (node (ref "PCIE") (pin "25") (pinfunction "PER_P2_25") (pintype "bidirectional"))
    )
    (net (code "453") (name "unconnected-(PCIE-PER_P3-Pad13)") (class "Default")
      (node (ref "PCIE") (pin "13") (pinfunction "PER_P3_13") (pintype "bidirectional"))
    )
    (net (code "454") (name "unconnected-(PCIE-PET_N1-Pad29)") (class "Default")
      (node (ref "PCIE") (pin "29") (pinfunction "PET_N1_29") (pintype "bidirectional"))
    )
    (net (code "455") (name "unconnected-(PCIE-PET_N2-Pad17)") (class "Default")
      (node (ref "PCIE") (pin "17") (pinfunction "PET_N2_17") (pintype "bidirectional"))
    )
    (net (code "456") (name "unconnected-(PCIE-PET_N3-Pad5)") (class "Default")
      (node (ref "PCIE") (pin "5") (pinfunction "PET_N3_5") (pintype "bidirectional"))
    )
    (net (code "457") (name "unconnected-(PCIE-PET_P1-Pad31)") (class "Default")
      (node (ref "PCIE") (pin "31") (pinfunction "PET_P1_31") (pintype "bidirectional"))
    )
    (net (code "458") (name "unconnected-(PCIE-PET_P2-Pad19)") (class "Default")
      (node (ref "PCIE") (pin "19") (pinfunction "PET_P2_19") (pintype "bidirectional"))
    )
    (net (code "459") (name "unconnected-(PCIE-PET_P3-Pad7)") (class "Default")
      (node (ref "PCIE") (pin "7") (pinfunction "PET_P3_7") (pintype "bidirectional"))
    )
    (net (code "460") (name "unconnected-(R86-Pad1)") (class "Default")
      (node (ref "R86") (pin "1") (pinfunction "1_1") (pintype "passive"))
    )
    (net (code "461") (name "unconnected-(SD1-DET_A-PadDET1)") (class "Default")
      (node (ref "SD1") (pin "DET1") (pinfunction "DET_A_DET1") (pintype "bidirectional"))
    )
    (net (code "462") (name "unconnected-(SD1-DET_B-PadDET2)") (class "Default")
      (node (ref "SD1") (pin "DET2") (pinfunction "DET_B_DET2") (pintype "bidirectional"))
    )
    (net (code "463") (name "unconnected-(USBC-SBU1-PadA8)") (class "Default")
      (node (ref "USBC") (pin "A8") (pinfunction "SBU1_A8") (pintype "passive"))
    )
    (net (code "464") (name "unconnected-(USBC-SBU2-PadB8)") (class "Default")
      (node (ref "USBC") (pin "B8") (pinfunction "SBU2_B8") (pintype "passive"))
    )
    (net (code "465") (name "~{ADC_RST}") (class "Default")
      (node (ref "IC10") (pin "26") (pinfunction "~{PD}/~{RST}_26") (pintype "input"))
      (node (ref "R16") (pin "2") (pinfunction "2_2") (pintype "passive"))
      (node (ref "R38") (pin "1") (pinfunction "1_1") (pintype "passive"))
    )
    (net (code "466") (name "~{DIO_LEVEL_SELECT}") (class "Default")
      (node (ref "IC38") (pin "3") (pinfunction "2C_3") (pintype "input"))
      (node (ref "IC39") (pin "4") (pinfunction "OUT_4") (pintype "bidirectional"))
    )
  )
)
